# SyncBoard1.net
KiCad netlist of a schematic drawn in Altium Designer
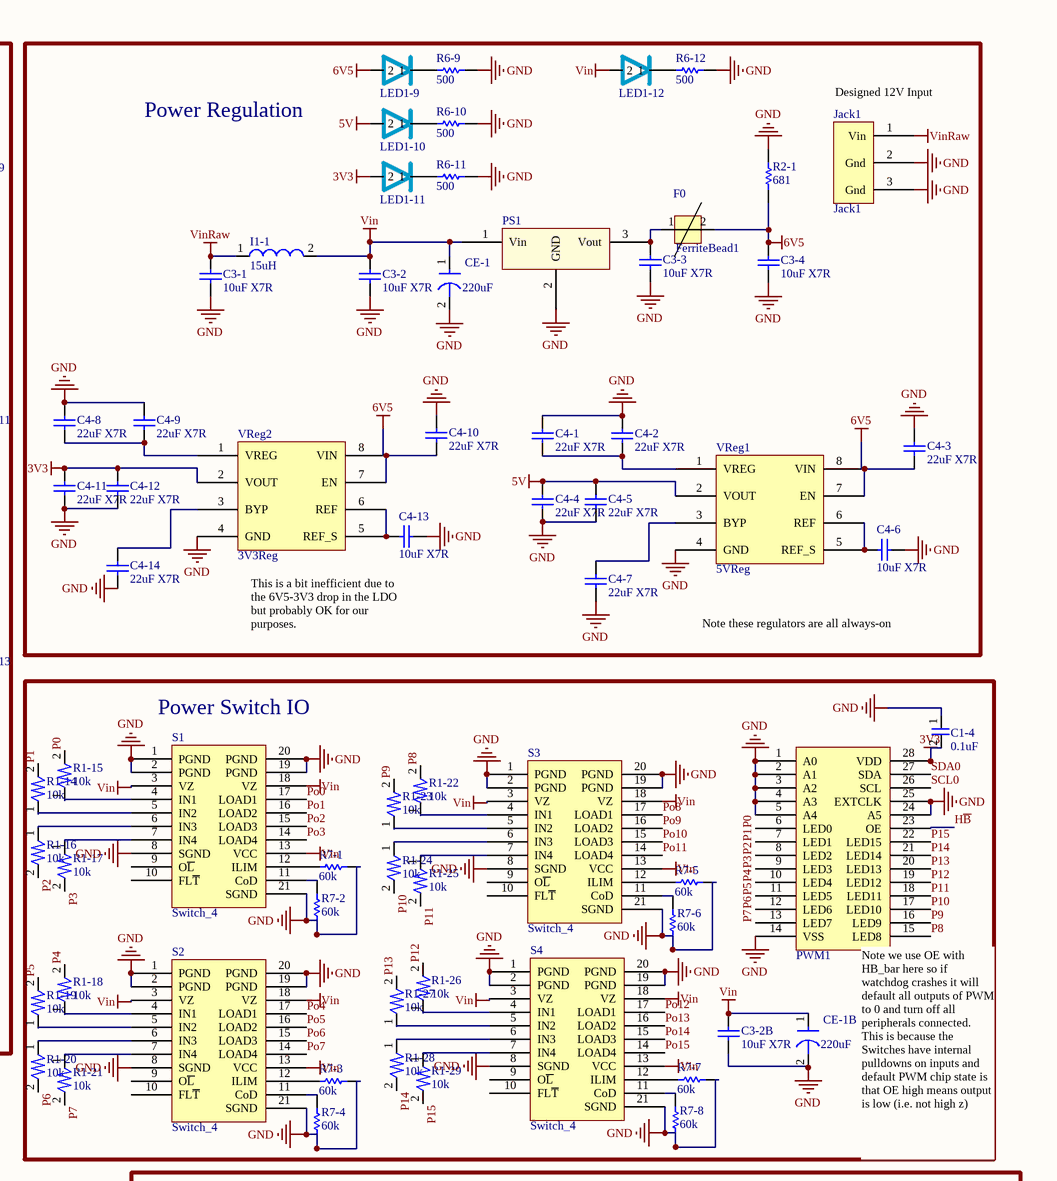
[diagram p0: SyncBoard1.SchDoc, top right]
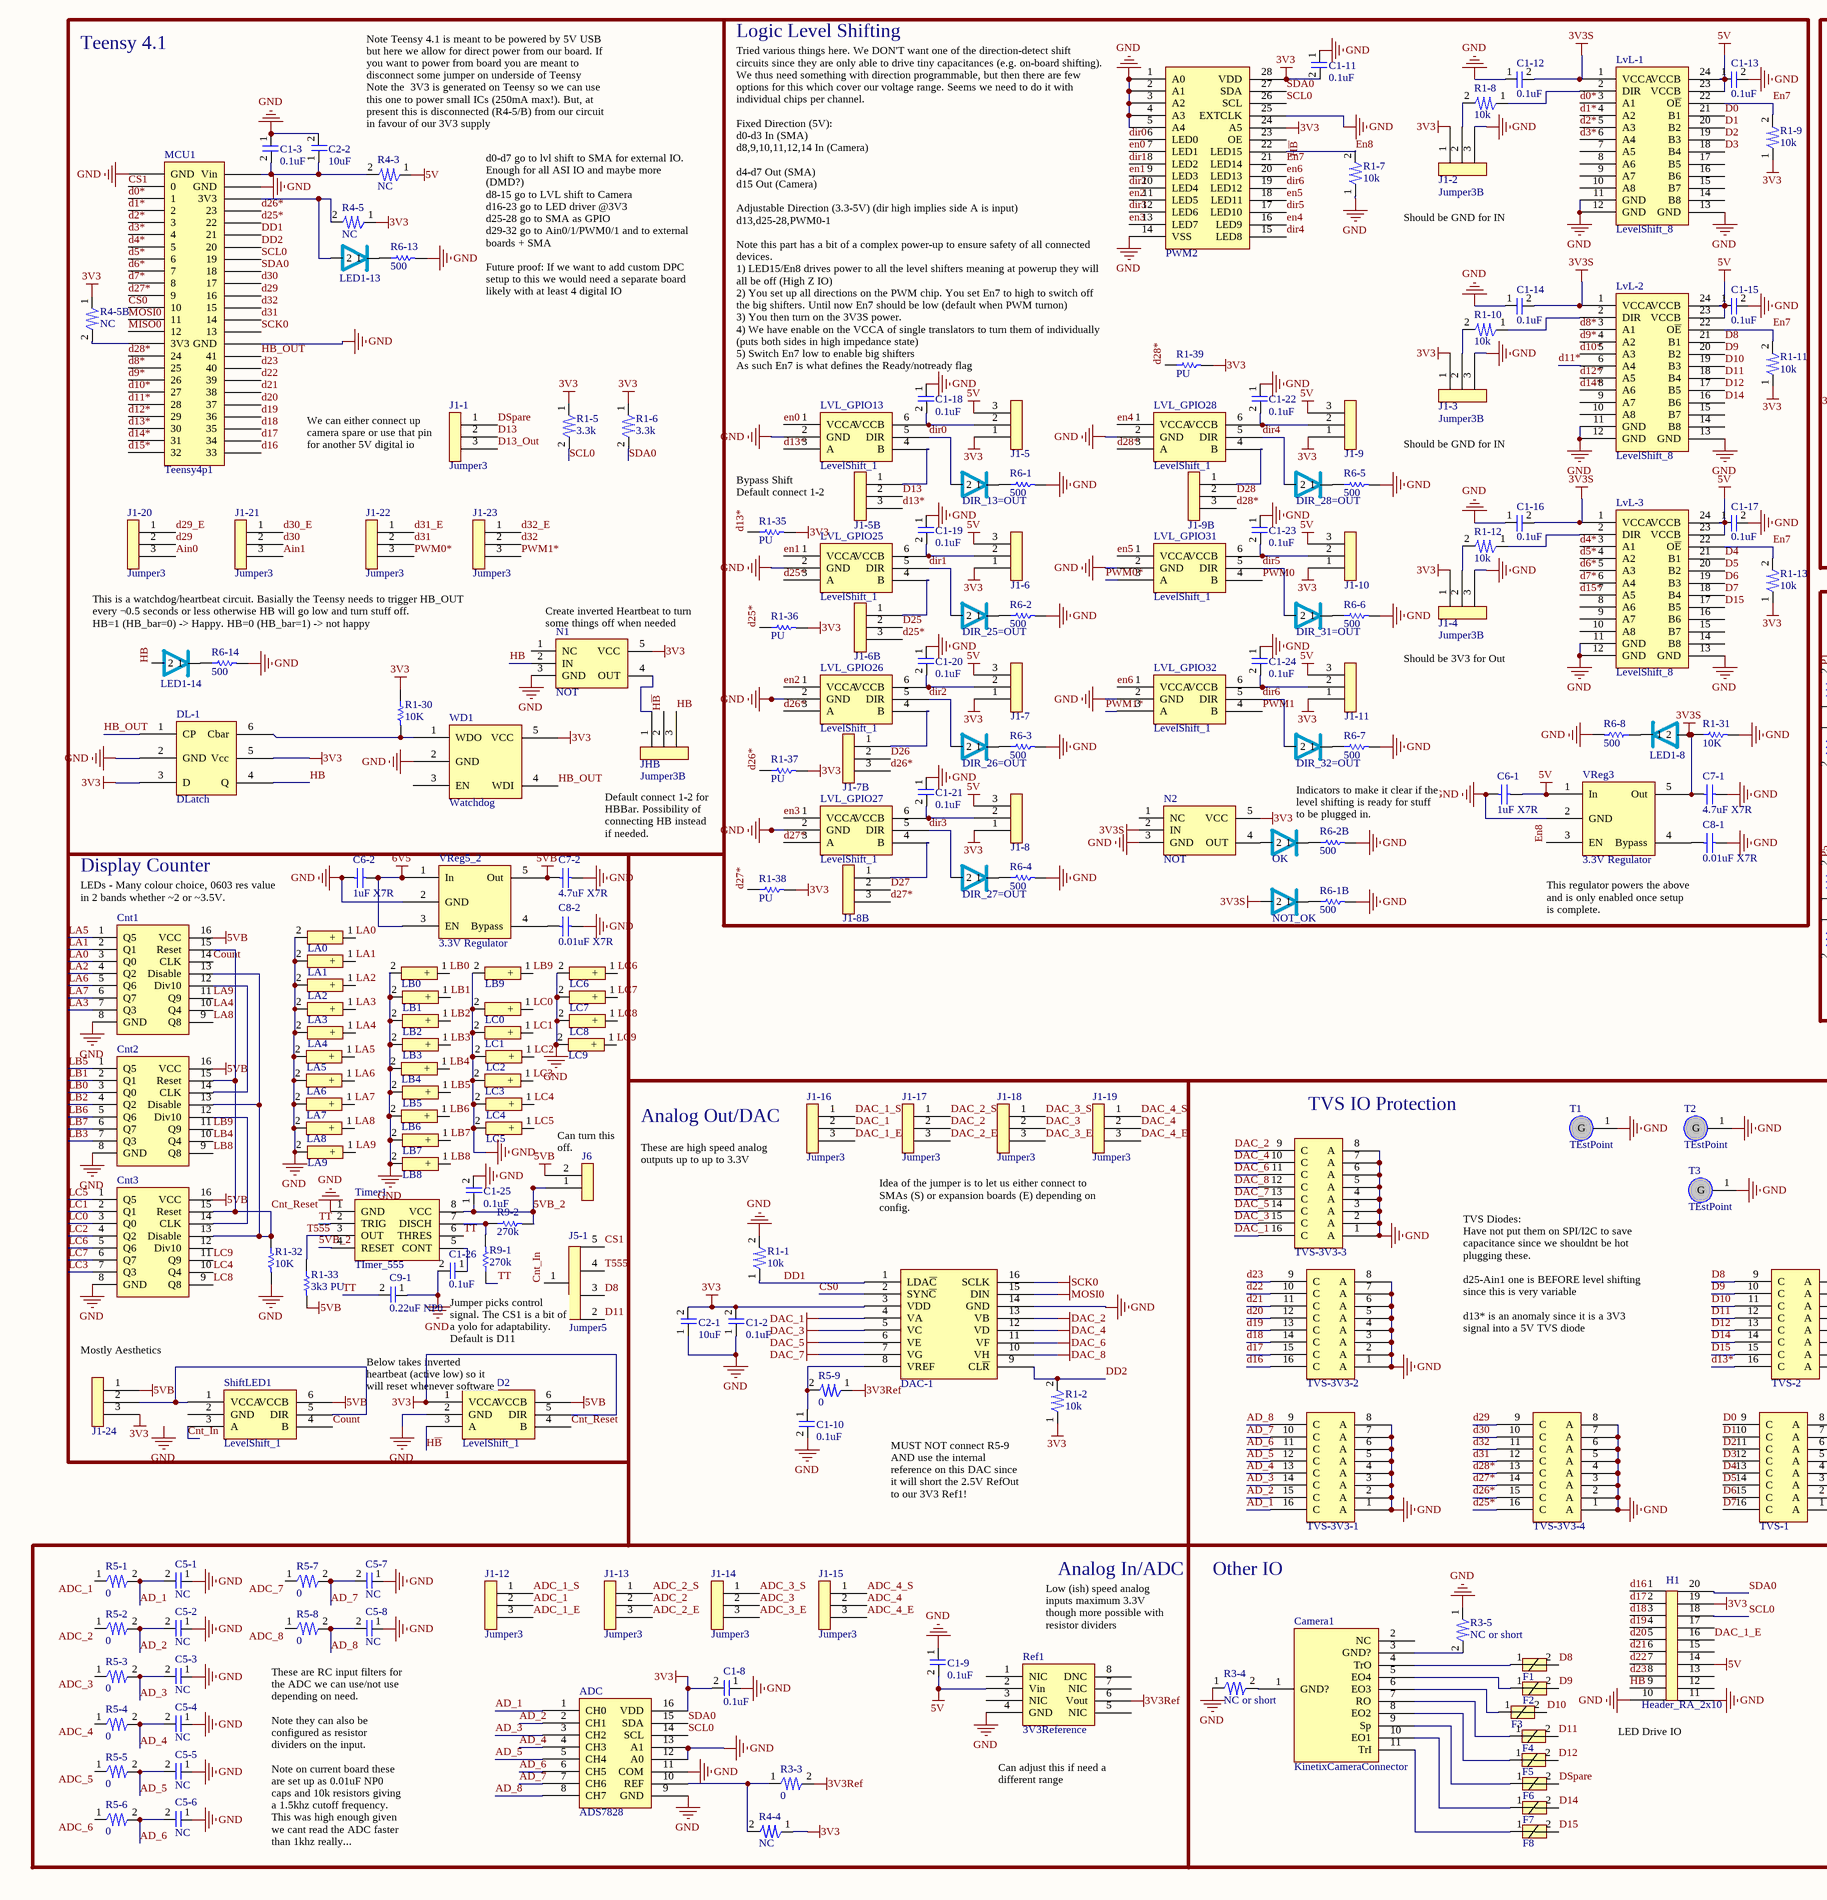
[diagram p1: SyncBoard1.SchDoc, bottom left]
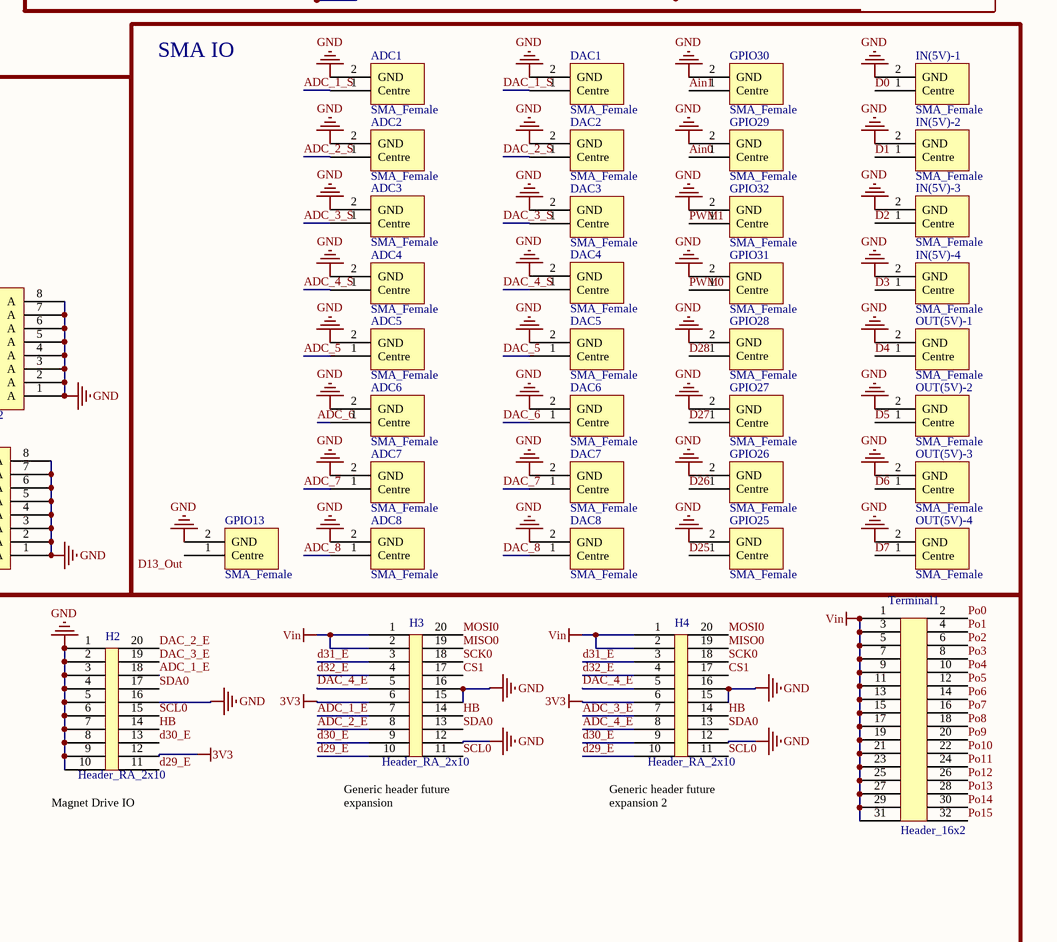
[diagram p2: SyncBoard1.SchDoc, bottom right]

(export (version "E")
  (design (tool "Eeschema 10.0.6"))
  (components
    (comp (ref "ADC")
      (value "ADS7828")
      (footprint "16-TSSOP")
      (libsource (lib "PCBSchematics") (part "ADS7828"))
    )
    (comp (ref "ADC1")
      (value "SMA_Female")
      (footprint "SMA_Ferrite")
      (libsource (lib "PCBSchematics") (part "SMA_Female"))
    )
    (comp (ref "ADC2")
      (value "SMA_Female")
      (footprint "SMA_Ferrite")
      (libsource (lib "PCBSchematics") (part "SMA_Female"))
    )
    (comp (ref "ADC3")
      (value "SMA_Female")
      (footprint "SMA_Ferrite")
      (libsource (lib "PCBSchematics") (part "SMA_Female"))
    )
    (comp (ref "ADC4")
      (value "SMA_Female")
      (footprint "SMA_Ferrite")
      (libsource (lib "PCBSchematics") (part "SMA_Female"))
    )
    (comp (ref "ADC5")
      (value "SMA_Female")
      (footprint "SMA_Ferrite")
      (libsource (lib "PCBSchematics") (part "SMA_Female"))
    )
    (comp (ref "ADC6")
      (value "SMA_Female")
      (footprint "SMA_Ferrite")
      (libsource (lib "PCBSchematics") (part "SMA_Female"))
    )
    (comp (ref "ADC7")
      (value "SMA_Female")
      (footprint "SMA_Ferrite")
      (libsource (lib "PCBSchematics") (part "SMA_Female"))
    )
    (comp (ref "ADC8")
      (value "SMA_Female")
      (footprint "SMA_Ferrite")
      (libsource (lib "PCBSchematics") (part "SMA_Female"))
    )
    (comp (ref "C1-2")
      (value "0.1uF")
      (footprint "0805")
      (libsource (lib "PCBSchematics") (part "Capacitor1"))
    )
    (comp (ref "C1-3")
      (value "0.1uF")
      (footprint "0805")
      (libsource (lib "PCBSchematics") (part "Capacitor1"))
    )
    (comp (ref "C1-4")
      (value "0.1uF")
      (footprint "0805")
      (libsource (lib "PCBSchematics") (part "Capacitor1"))
    )
    (comp (ref "C1-8")
      (value "0.1uF")
      (footprint "0805")
      (libsource (lib "PCBSchematics") (part "Capacitor1"))
    )
    (comp (ref "C1-9")
      (value "0.1uF")
      (footprint "0805")
      (libsource (lib "PCBSchematics") (part "Capacitor1"))
    )
    (comp (ref "C1-10")
      (value "0.1uF")
      (footprint "0805")
      (libsource (lib "PCBSchematics") (part "Capacitor1"))
    )
    (comp (ref "C1-11")
      (value "0.1uF")
      (footprint "0805")
      (libsource (lib "PCBSchematics") (part "Capacitor1"))
    )
    (comp (ref "C1-12")
      (value "0.1uF")
      (footprint "0805")
      (libsource (lib "PCBSchematics") (part "Capacitor1"))
    )
    (comp (ref "C1-13")
      (value "0.1uF")
      (footprint "0805")
      (libsource (lib "PCBSchematics") (part "Capacitor1"))
    )
    (comp (ref "C1-14")
      (value "0.1uF")
      (footprint "0805")
      (libsource (lib "PCBSchematics") (part "Capacitor1"))
    )
    (comp (ref "C1-15")
      (value "0.1uF")
      (footprint "0805")
      (libsource (lib "PCBSchematics") (part "Capacitor1"))
    )
    (comp (ref "C1-16")
      (value "0.1uF")
      (footprint "0805")
      (libsource (lib "PCBSchematics") (part "Capacitor1"))
    )
    (comp (ref "C1-17")
      (value "0.1uF")
      (footprint "0805")
      (libsource (lib "PCBSchematics") (part "Capacitor1"))
    )
    (comp (ref "C1-18")
      (value "0.1uF")
      (footprint "0805")
      (libsource (lib "PCBSchematics") (part "Capacitor1"))
    )
    (comp (ref "C1-19")
      (value "0.1uF")
      (footprint "0805")
      (libsource (lib "PCBSchematics") (part "Capacitor1"))
    )
    (comp (ref "C1-20")
      (value "0.1uF")
      (footprint "0805")
      (libsource (lib "PCBSchematics") (part "Capacitor1"))
    )
    (comp (ref "C1-21")
      (value "0.1uF")
      (footprint "0805")
      (libsource (lib "PCBSchematics") (part "Capacitor1"))
    )
    (comp (ref "C1-22")
      (value "0.1uF")
      (footprint "0805")
      (libsource (lib "PCBSchematics") (part "Capacitor1"))
    )
    (comp (ref "C1-23")
      (value "0.1uF")
      (footprint "0805")
      (libsource (lib "PCBSchematics") (part "Capacitor1"))
    )
    (comp (ref "C1-24")
      (value "0.1uF")
      (footprint "0805")
      (libsource (lib "PCBSchematics") (part "Capacitor1"))
    )
    (comp (ref "C1-25")
      (value "0.1uF")
      (footprint "0805")
      (libsource (lib "PCBSchematics") (part "Capacitor1"))
    )
    (comp (ref "C1-26")
      (value "0.1uF")
      (footprint "0805")
      (libsource (lib "PCBSchematics") (part "Capacitor1"))
    )
    (comp (ref "C2-1")
      (value "10uF")
      (footprint "1206")
      (libsource (lib "PCBSchematics") (part "Capacitor1205"))
    )
    (comp (ref "C2-2")
      (value "10uF")
      (footprint "1206")
      (libsource (lib "PCBSchematics") (part "Capacitor1205"))
    )
    (comp (ref "C3-1")
      (value "10uF X7R")
      (footprint "1206")
      (description "Capacitor")
      (libsource (lib "Schlib1") (part "Cap 0805"))
    )
    (comp (ref "C3-2")
      (value "10uF X7R")
      (footprint "1206")
      (description "Capacitor")
      (libsource (lib "Schlib1") (part "Cap 0805"))
    )
    (comp (ref "C3-2B")
      (value "10uF X7R")
      (footprint "1206")
      (description "Capacitor")
      (libsource (lib "Schlib1") (part "Cap 0805"))
    )
    (comp (ref "C3-3")
      (value "10uF X7R")
      (footprint "1206")
      (description "Capacitor")
      (libsource (lib "Schlib1") (part "Cap 0805"))
    )
    (comp (ref "C3-4")
      (value "10uF X7R")
      (footprint "1206")
      (description "Capacitor")
      (libsource (lib "Schlib1") (part "Cap 0805"))
    )
    (comp (ref "C4-1")
      (value "22uF X7R")
      (footprint "1206")
      (description "Capacitor")
      (libsource (lib "Schlib1") (part "Cap 0805"))
    )
    (comp (ref "C4-2")
      (value "22uF X7R")
      (footprint "1206")
      (description "Capacitor")
      (libsource (lib "Schlib1") (part "Cap 0805"))
    )
    (comp (ref "C4-3")
      (value "22uF X7R")
      (footprint "1206")
      (description "Capacitor")
      (libsource (lib "Schlib1") (part "Cap 0805"))
    )
    (comp (ref "C4-4")
      (value "22uF X7R")
      (footprint "1206")
      (description "Capacitor")
      (libsource (lib "Schlib1") (part "Cap 0805"))
    )
    (comp (ref "C4-5")
      (value "22uF X7R")
      (footprint "1206")
      (description "Capacitor")
      (libsource (lib "Schlib1") (part "Cap 0805"))
    )
    (comp (ref "C4-6")
      (value "10uF X7R")
      (footprint "1206")
      (description "Capacitor")
      (libsource (lib "Schlib1") (part "Cap 0805"))
    )
    (comp (ref "C4-7")
      (value "22uF X7R")
      (footprint "1206")
      (description "Capacitor")
      (libsource (lib "Schlib1") (part "Cap 0805"))
    )
    (comp (ref "C4-8")
      (value "22uF X7R")
      (footprint "1206")
      (description "Capacitor")
      (libsource (lib "Schlib1") (part "Cap 0805"))
    )
    (comp (ref "C4-9")
      (value "22uF X7R")
      (footprint "1206")
      (description "Capacitor")
      (libsource (lib "Schlib1") (part "Cap 0805"))
    )
    (comp (ref "C4-10")
      (value "22uF X7R")
      (footprint "1206")
      (description "Capacitor")
      (libsource (lib "Schlib1") (part "Cap 0805"))
    )
    (comp (ref "C4-11")
      (value "22uF X7R")
      (footprint "1206")
      (description "Capacitor")
      (libsource (lib "Schlib1") (part "Cap 0805"))
    )
    (comp (ref "C4-12")
      (value "22uF X7R")
      (footprint "1206")
      (description "Capacitor")
      (libsource (lib "Schlib1") (part "Cap 0805"))
    )
    (comp (ref "C4-13")
      (value "10uF X7R")
      (footprint "1206")
      (description "Capacitor")
      (libsource (lib "Schlib1") (part "Cap 0805"))
    )
    (comp (ref "C4-14")
      (value "22uF X7R")
      (footprint "1206")
      (description "Capacitor")
      (libsource (lib "Schlib1") (part "Cap 0805"))
    )
    (comp (ref "C5-1") (value "NC") (footprint "0805") (libsource (lib "PCBSchematics") (part "Capacitor1")))
    (comp (ref "C5-2") (value "NC") (footprint "0805") (libsource (lib "PCBSchematics") (part "Capacitor1")))
    (comp (ref "C5-3") (value "NC") (footprint "0805") (libsource (lib "PCBSchematics") (part "Capacitor1")))
    (comp (ref "C5-4") (value "NC") (footprint "0805") (libsource (lib "PCBSchematics") (part "Capacitor1")))
    (comp (ref "C5-5") (value "NC") (footprint "0805") (libsource (lib "PCBSchematics") (part "Capacitor1")))
    (comp (ref "C5-6") (value "NC") (footprint "0805") (libsource (lib "PCBSchematics") (part "Capacitor1")))
    (comp (ref "C5-7") (value "NC") (footprint "0805") (libsource (lib "PCBSchematics") (part "Capacitor1")))
    (comp (ref "C5-8") (value "NC") (footprint "0805") (libsource (lib "PCBSchematics") (part "Capacitor1")))
    (comp (ref "C6-1")
      (value "1uF X7R")
      (footprint "0805")
      (description "Capacitor")
      (libsource (lib "Schlib1") (part "Cap"))
    )
    (comp (ref "C6-2")
      (value "1uF X7R")
      (footprint "0805")
      (description "Capacitor")
      (libsource (lib "Schlib1") (part "Cap"))
    )
    (comp (ref "C7-1")
      (value "4.7uF X7R")
      (footprint "0805")
      (description "Capacitor")
      (libsource (lib "Schlib1") (part "Cap"))
    )
    (comp (ref "C7-2")
      (value "4.7uF X7R")
      (footprint "0805")
      (description "Capacitor")
      (libsource (lib "Schlib1") (part "Cap"))
    )
    (comp (ref "C8-1")
      (value "0.01uF X7R")
      (footprint "0603")
      (description "Capacitor")
      (libsource (lib "Schlib1") (part "Cap"))
    )
    (comp (ref "C8-2")
      (value "0.01uF X7R")
      (footprint "0603")
      (description "Capacitor")
      (libsource (lib "Schlib1") (part "Cap"))
    )
    (comp (ref "C9-1")
      (value "0.22uF NP0")
      (footprint "1206")
      (libsource (lib "PCBSchematics") (part "Capacitor1"))
    )
    (comp (ref "Camera1")
      (value "KinetixCameraConnector")
      (footprint "Connector_HR212")
      (libsource (lib "PCBSchematics") (part "KinetixCameraConnector"))
    )
    (comp (ref "CE-1")
      (value "220uF")
      (footprint "ElectrolyticCapacitor")
      (description "ElectrolyticCap")
      (libsource (lib "Schlib1") (part "CapElectrolytic2"))
    )
    (comp (ref "CE-1B")
      (value "220uF")
      (footprint "ElectrolyticCapacitor")
      (description "ElectrolyticCap")
      (libsource (lib "Schlib1") (part "CapElectrolytic2"))
    )
    (comp (ref "Cnt1")
      (value "Counter_$017")
      (footprint "16-TSSOP")
      (libsource (lib "PCBSchematics") (part "Counter_$017"))
    )
    (comp (ref "Cnt2")
      (value "Counter_$017")
      (footprint "16-TSSOP")
      (libsource (lib "PCBSchematics") (part "Counter_$017"))
    )
    (comp (ref "Cnt3")
      (value "Counter_$017")
      (footprint "16-TSSOP")
      (libsource (lib "PCBSchematics") (part "Counter_$017"))
    )
    (comp (ref "DAC-1")
      (value "AD5668-2")
      (footprint "16-TSSOP")
      (libsource (lib "PCBSchematics") (part "AD5668-2"))
    )
    (comp (ref "DAC1")
      (value "SMA_Female")
      (footprint "SMA_Ferrite")
      (libsource (lib "PCBSchematics") (part "SMA_Female"))
    )
    (comp (ref "DAC2")
      (value "SMA_Female")
      (footprint "SMA_Ferrite")
      (libsource (lib "PCBSchematics") (part "SMA_Female"))
    )
    (comp (ref "DAC3")
      (value "SMA_Female")
      (footprint "SMA_Ferrite")
      (libsource (lib "PCBSchematics") (part "SMA_Female"))
    )
    (comp (ref "DAC4")
      (value "SMA_Female")
      (footprint "SMA_Ferrite")
      (libsource (lib "PCBSchematics") (part "SMA_Female"))
    )
    (comp (ref "DAC5")
      (value "SMA_Female")
      (footprint "SMA_Ferrite")
      (libsource (lib "PCBSchematics") (part "SMA_Female"))
    )
    (comp (ref "DAC6")
      (value "SMA_Female")
      (footprint "SMA_Ferrite")
      (libsource (lib "PCBSchematics") (part "SMA_Female"))
    )
    (comp (ref "DAC7")
      (value "SMA_Female")
      (footprint "SMA_Ferrite")
      (libsource (lib "PCBSchematics") (part "SMA_Female"))
    )
    (comp (ref "DAC8")
      (value "SMA_Female")
      (footprint "SMA_Ferrite")
      (libsource (lib "PCBSchematics") (part "SMA_Female"))
    )
    (comp (ref "DIR_13=OUT")
      (value "LEDindicator")
      (footprint "LEDindicator")
      (libsource (lib "Schlib1") (part "LEDindicator"))
    )
    (comp (ref "DIR_25=OUT")
      (value "LEDindicator")
      (footprint "LEDindicator")
      (libsource (lib "Schlib1") (part "LEDindicator"))
    )
    (comp (ref "DIR_26=OUT")
      (value "LEDindicator")
      (footprint "LEDindicator")
      (libsource (lib "Schlib1") (part "LEDindicator"))
    )
    (comp (ref "DIR_27=OUT")
      (value "LEDindicator")
      (footprint "LEDindicator")
      (libsource (lib "Schlib1") (part "LEDindicator"))
    )
    (comp (ref "DIR_28=OUT")
      (value "LEDindicator")
      (footprint "LEDindicator")
      (libsource (lib "Schlib1") (part "LEDindicator"))
    )
    (comp (ref "DIR_31=OUT")
      (value "LEDindicator")
      (footprint "LEDindicator")
      (libsource (lib "Schlib1") (part "LEDindicator"))
    )
    (comp (ref "DIR_32=OUT")
      (value "LEDindicator")
      (footprint "LEDindicator")
      (libsource (lib "Schlib1") (part "LEDindicator"))
    )
    (comp (ref "DL-1")
      (value "DLatch")
      (footprint "6-TSSOP / SC-70-6")
      (description "D-Latch")
      (libsource (lib "Schlib1") (part "DLatch"))
    )
    (comp (ref "F0")
      (value "FerriteBead1")
      (footprint "FerriteBead1")
      (libsource (lib "PCBSchematics") (part "FerriteBead1"))
    )
    (comp (ref "F1")
      (value "FerriteBead2")
      (footprint "0603")
      (libsource (lib "PCBSchematics") (part "FerriteBead2"))
    )
    (comp (ref "F2")
      (value "FerriteBead2")
      (footprint "0603")
      (libsource (lib "PCBSchematics") (part "FerriteBead2"))
    )
    (comp (ref "F3")
      (value "FerriteBead2")
      (footprint "0603")
      (libsource (lib "PCBSchematics") (part "FerriteBead2"))
    )
    (comp (ref "F4")
      (value "FerriteBead2")
      (footprint "0603")
      (libsource (lib "PCBSchematics") (part "FerriteBead2"))
    )
    (comp (ref "F5")
      (value "FerriteBead2")
      (footprint "0603")
      (libsource (lib "PCBSchematics") (part "FerriteBead2"))
    )
    (comp (ref "F6")
      (value "FerriteBead2")
      (footprint "0603")
      (libsource (lib "PCBSchematics") (part "FerriteBead2"))
    )
    (comp (ref "F7")
      (value "FerriteBead2")
      (footprint "0603")
      (libsource (lib "PCBSchematics") (part "FerriteBead2"))
    )
    (comp (ref "F8")
      (value "FerriteBead2")
      (footprint "0603")
      (libsource (lib "PCBSchematics") (part "FerriteBead2"))
    )
    (comp (ref "GPIO13")
      (value "SMA_Female")
      (footprint "SMA_Ferrite")
      (libsource (lib "PCBSchematics") (part "SMA_Female"))
    )
    (comp (ref "GPIO25")
      (value "SMA_Female")
      (footprint "SMA_Ferrite")
      (libsource (lib "PCBSchematics") (part "SMA_Female"))
    )
    (comp (ref "GPIO26")
      (value "SMA_Female")
      (footprint "SMA_Ferrite")
      (libsource (lib "PCBSchematics") (part "SMA_Female"))
    )
    (comp (ref "GPIO27")
      (value "SMA_Female")
      (footprint "SMA_Ferrite")
      (libsource (lib "PCBSchematics") (part "SMA_Female"))
    )
    (comp (ref "GPIO28")
      (value "SMA_Female")
      (footprint "SMA_Ferrite")
      (libsource (lib "PCBSchematics") (part "SMA_Female"))
    )
    (comp (ref "GPIO29")
      (value "SMA_Female")
      (footprint "SMA_Ferrite")
      (libsource (lib "PCBSchematics") (part "SMA_Female"))
    )
    (comp (ref "GPIO30")
      (value "SMA_Female")
      (footprint "SMA_Ferrite")
      (libsource (lib "PCBSchematics") (part "SMA_Female"))
    )
    (comp (ref "GPIO31")
      (value "SMA_Female")
      (footprint "SMA_Ferrite")
      (libsource (lib "PCBSchematics") (part "SMA_Female"))
    )
    (comp (ref "GPIO32")
      (value "SMA_Female")
      (footprint "SMA_Ferrite")
      (libsource (lib "PCBSchematics") (part "SMA_Female"))
    )
    (comp (ref "H1")
      (value "Header_RA_2x10")
      (footprint "HeaderRA 2x10")
      (libsource (lib "PCBSchematics") (part "Header_RA_2x10"))
    )
    (comp (ref "H2")
      (value "Header_RA_2x10")
      (footprint "HeaderRA 2x10")
      (libsource (lib "PCBSchematics") (part "Header_RA_2x10"))
    )
    (comp (ref "H3")
      (value "Header_RA_2x10")
      (footprint "HeaderRA 2x10")
      (libsource (lib "PCBSchematics") (part "Header_RA_2x10"))
    )
    (comp (ref "H4")
      (value "Header_RA_2x10")
      (footprint "HeaderRA 2x10")
      (libsource (lib "PCBSchematics") (part "Header_RA_2x10"))
    )
    (comp (ref "I1-1")
      (value "15uH")
      (footprint "Inductor1")
      (description "Inductor")
      (libsource (lib "Schlib1") (part "Inductor3"))
    )
    (comp (ref "IN(5V)-1")
      (value "SMA_Female")
      (footprint "SMA_Ferrite")
      (libsource (lib "PCBSchematics") (part "SMA_Female"))
    )
    (comp (ref "IN(5V)-2")
      (value "SMA_Female")
      (footprint "SMA_Ferrite")
      (libsource (lib "PCBSchematics") (part "SMA_Female"))
    )
    (comp (ref "IN(5V)-3")
      (value "SMA_Female")
      (footprint "SMA_Ferrite")
      (libsource (lib "PCBSchematics") (part "SMA_Female"))
    )
    (comp (ref "IN(5V)-4")
      (value "SMA_Female")
      (footprint "SMA_Ferrite")
      (libsource (lib "PCBSchematics") (part "SMA_Female"))
    )
    (comp (ref "J1-1")
      (value "Jumper3")
      (footprint "Jumper3B")
      (libsource (lib "PCBSchematics") (part "Jumper3"))
    )
    (comp (ref "J1-2") (value "Jumper3B") (footprint "Jumper3B") (libsource (lib "") (part "Jumper3B_1")))
    (comp (ref "J1-3") (value "Jumper3B") (footprint "Jumper3B") (libsource (lib "") (part "Jumper3B_1")))
    (comp (ref "J1-4") (value "Jumper3B") (footprint "Jumper3B") (libsource (lib "") (part "Jumper3B_1")))
    (comp (ref "J1-5") (value "Jumper3B") (footprint "Jumper3B") (libsource (lib "") (part "Jumper3B_2")))
    (comp (ref "J1-5B")
      (value "Jumper3B")
      (footprint "Jumper3B")
      (libsource (lib "PCBSchematics") (part "Jumper3B"))
    )
    (comp (ref "J1-6") (value "Jumper3B") (footprint "Jumper3B") (libsource (lib "") (part "Jumper3B_2")))
    (comp (ref "J1-6B")
      (value "Jumper3B")
      (footprint "Jumper3B")
      (libsource (lib "PCBSchematics") (part "Jumper3B"))
    )
    (comp (ref "J1-7") (value "Jumper3B") (footprint "Jumper3B") (libsource (lib "") (part "Jumper3B_2")))
    (comp (ref "J1-7B")
      (value "Jumper3B")
      (footprint "Jumper3B")
      (libsource (lib "PCBSchematics") (part "Jumper3B"))
    )
    (comp (ref "J1-8") (value "Jumper3B") (footprint "Jumper3B") (libsource (lib "") (part "Jumper3B_2")))
    (comp (ref "J1-8B")
      (value "Jumper3B")
      (footprint "Jumper3B")
      (libsource (lib "PCBSchematics") (part "Jumper3B"))
    )
    (comp (ref "J1-9") (value "Jumper3B") (footprint "Jumper3B") (libsource (lib "") (part "Jumper3B_2")))
    (comp (ref "J1-9B")
      (value "Jumper3B")
      (footprint "Jumper3B")
      (libsource (lib "PCBSchematics") (part "Jumper3B"))
    )
    (comp (ref "J1-10") (value "Jumper3B") (footprint "Jumper3B") (libsource (lib "") (part "Jumper3B_2")))
    (comp (ref "J1-11") (value "Jumper3B") (footprint "Jumper3B") (libsource (lib "") (part "Jumper3B_2")))
    (comp (ref "J1-12")
      (value "Jumper3")
      (footprint "Jumper")
      (libsource (lib "PCBSchematics") (part "Jumper3"))
    )
    (comp (ref "J1-13")
      (value "Jumper3")
      (footprint "Jumper")
      (libsource (lib "PCBSchematics") (part "Jumper3"))
    )
    (comp (ref "J1-14")
      (value "Jumper3")
      (footprint "Jumper")
      (libsource (lib "PCBSchematics") (part "Jumper3"))
    )
    (comp (ref "J1-15")
      (value "Jumper3")
      (footprint "Jumper")
      (libsource (lib "PCBSchematics") (part "Jumper3"))
    )
    (comp (ref "J1-16")
      (value "Jumper3")
      (footprint "Jumper")
      (libsource (lib "PCBSchematics") (part "Jumper3"))
    )
    (comp (ref "J1-17")
      (value "Jumper3")
      (footprint "Jumper")
      (libsource (lib "PCBSchematics") (part "Jumper3"))
    )
    (comp (ref "J1-18")
      (value "Jumper3")
      (footprint "Jumper")
      (libsource (lib "PCBSchematics") (part "Jumper3"))
    )
    (comp (ref "J1-19")
      (value "Jumper3")
      (footprint "Jumper")
      (libsource (lib "PCBSchematics") (part "Jumper3"))
    )
    (comp (ref "J1-20")
      (value "Jumper3")
      (footprint "Jumper")
      (libsource (lib "PCBSchematics") (part "Jumper3"))
    )
    (comp (ref "J1-21")
      (value "Jumper3")
      (footprint "Jumper")
      (libsource (lib "PCBSchematics") (part "Jumper3"))
    )
    (comp (ref "J1-22")
      (value "Jumper3")
      (footprint "Jumper")
      (libsource (lib "PCBSchematics") (part "Jumper3"))
    )
    (comp (ref "J1-23")
      (value "Jumper3")
      (footprint "Jumper")
      (libsource (lib "PCBSchematics") (part "Jumper3"))
    )
    (comp (ref "J1-24")
      (value "Jumper3B")
      (footprint "Jumper3B")
      (libsource (lib "PCBSchematics") (part "Jumper3B"))
    )
    (comp (ref "J5-1")
      (value "Jumper5")
      (footprint "Jumper5")
      (libsource (lib "PCBSchematics") (part "Jumper5"))
    )
    (comp (ref "J6")
      (value "Jumper2_Pins")
      (footprint "Jumper2_Pins")
      (libsource (lib "PCBSchematics") (part "Jumper2_Pins"))
    )
    (comp (ref "Jack1")
      (value "Jack1")
      (footprint "PowerJack")
      (libsource (lib "Schlib1") (part "PowerJack3"))
    )
    (comp (ref "JHB") (value "Jumper3B") (footprint "Jumper3B") (libsource (lib "") (part "Jumper3B_1")))
    (comp (ref "LA0")
      (value "LEDSINGLESIDE")
      (footprint "LedSingleSide")
      (libsource (lib "PCBSchematics") (part "LEDSINGLESIDE"))
    )
    (comp (ref "LA1")
      (value "LEDSINGLESIDE")
      (footprint "LedSingleSide")
      (libsource (lib "PCBSchematics") (part "LEDSINGLESIDE"))
    )
    (comp (ref "LA2")
      (value "LEDSINGLESIDE")
      (footprint "LedSingleSide")
      (libsource (lib "PCBSchematics") (part "LEDSINGLESIDE"))
    )
    (comp (ref "LA3")
      (value "LEDSINGLESIDE")
      (footprint "LedSingleSide")
      (libsource (lib "PCBSchematics") (part "LEDSINGLESIDE"))
    )
    (comp (ref "LA4")
      (value "LEDSINGLESIDE")
      (footprint "LedSingleSide")
      (libsource (lib "PCBSchematics") (part "LEDSINGLESIDE"))
    )
    (comp (ref "LA5")
      (value "LEDSINGLESIDE")
      (footprint "LedSingleSide")
      (libsource (lib "PCBSchematics") (part "LEDSINGLESIDE"))
    )
    (comp (ref "LA6")
      (value "LEDSINGLESIDE")
      (footprint "LedSingleSide")
      (libsource (lib "PCBSchematics") (part "LEDSINGLESIDE"))
    )
    (comp (ref "LA7")
      (value "LEDSINGLESIDE")
      (footprint "LedSingleSide")
      (libsource (lib "PCBSchematics") (part "LEDSINGLESIDE"))
    )
    (comp (ref "LA8")
      (value "LEDSINGLESIDE")
      (footprint "LedSingleSide")
      (libsource (lib "PCBSchematics") (part "LEDSINGLESIDE"))
    )
    (comp (ref "LA9")
      (value "LEDSINGLESIDE")
      (footprint "LedSingleSide")
      (libsource (lib "PCBSchematics") (part "LEDSINGLESIDE"))
    )
    (comp (ref "LB0")
      (value "LEDSINGLESIDE")
      (footprint "LedSingleSide")
      (libsource (lib "PCBSchematics") (part "LEDSINGLESIDE"))
    )
    (comp (ref "LB1")
      (value "LEDSINGLESIDE")
      (footprint "LedSingleSide")
      (libsource (lib "PCBSchematics") (part "LEDSINGLESIDE"))
    )
    (comp (ref "LB2")
      (value "LEDSINGLESIDE")
      (footprint "LedSingleSide")
      (libsource (lib "PCBSchematics") (part "LEDSINGLESIDE"))
    )
    (comp (ref "LB3")
      (value "LEDSINGLESIDE")
      (footprint "LedSingleSide")
      (libsource (lib "PCBSchematics") (part "LEDSINGLESIDE"))
    )
    (comp (ref "LB4")
      (value "LEDSINGLESIDE")
      (footprint "LedSingleSide")
      (libsource (lib "PCBSchematics") (part "LEDSINGLESIDE"))
    )
    (comp (ref "LB5")
      (value "LEDSINGLESIDE")
      (footprint "LedSingleSide")
      (libsource (lib "PCBSchematics") (part "LEDSINGLESIDE"))
    )
    (comp (ref "LB6")
      (value "LEDSINGLESIDE")
      (footprint "LedSingleSide")
      (libsource (lib "PCBSchematics") (part "LEDSINGLESIDE"))
    )
    (comp (ref "LB7")
      (value "LEDSINGLESIDE")
      (footprint "LedSingleSide")
      (libsource (lib "PCBSchematics") (part "LEDSINGLESIDE"))
    )
    (comp (ref "LB8")
      (value "LEDSINGLESIDE")
      (footprint "LedSingleSide")
      (libsource (lib "PCBSchematics") (part "LEDSINGLESIDE"))
    )
    (comp (ref "LB9")
      (value "LEDSINGLESIDE")
      (footprint "LedSingleSide")
      (libsource (lib "PCBSchematics") (part "LEDSINGLESIDE"))
    )
    (comp (ref "LC0")
      (value "LEDSINGLESIDE")
      (footprint "LedSingleSide")
      (libsource (lib "PCBSchematics") (part "LEDSINGLESIDE"))
    )
    (comp (ref "LC1")
      (value "LEDSINGLESIDE")
      (footprint "LedSingleSide")
      (libsource (lib "PCBSchematics") (part "LEDSINGLESIDE"))
    )
    (comp (ref "LC2")
      (value "LEDSINGLESIDE")
      (footprint "LedSingleSide")
      (libsource (lib "PCBSchematics") (part "LEDSINGLESIDE"))
    )
    (comp (ref "LC3")
      (value "LEDSINGLESIDE")
      (footprint "LedSingleSide")
      (libsource (lib "PCBSchematics") (part "LEDSINGLESIDE"))
    )
    (comp (ref "LC4")
      (value "LEDSINGLESIDE")
      (footprint "LedSingleSide")
      (libsource (lib "PCBSchematics") (part "LEDSINGLESIDE"))
    )
    (comp (ref "LC5")
      (value "LEDSINGLESIDE")
      (footprint "LedSingleSide")
      (libsource (lib "PCBSchematics") (part "LEDSINGLESIDE"))
    )
    (comp (ref "LC6")
      (value "LEDSINGLESIDE")
      (footprint "LedSingleSide")
      (libsource (lib "PCBSchematics") (part "LEDSINGLESIDE"))
    )
    (comp (ref "LC7")
      (value "LEDSINGLESIDE")
      (footprint "LedSingleSide")
      (libsource (lib "PCBSchematics") (part "LEDSINGLESIDE"))
    )
    (comp (ref "LC8")
      (value "LEDSINGLESIDE")
      (footprint "LedSingleSide")
      (libsource (lib "PCBSchematics") (part "LEDSINGLESIDE"))
    )
    (comp (ref "LC9")
      (value "LEDSINGLESIDE")
      (footprint "LedSingleSide")
      (libsource (lib "PCBSchematics") (part "LEDSINGLESIDE"))
    )
    (comp (ref "LED1-8")
      (value "LEDindicator")
      (footprint "LEDindicator")
      (libsource (lib "Schlib1") (part "LEDindicator"))
    )
    (comp (ref "LED1-9")
      (value "LEDindicator")
      (footprint "LEDindicator")
      (libsource (lib "Schlib1") (part "LEDindicator"))
    )
    (comp (ref "LED1-10")
      (value "LEDindicator")
      (footprint "LEDindicator")
      (libsource (lib "Schlib1") (part "LEDindicator"))
    )
    (comp (ref "LED1-11")
      (value "LEDindicator")
      (footprint "LEDIndicator")
      (libsource (lib "Schlib1") (part "LEDindicator"))
    )
    (comp (ref "LED1-12")
      (value "LEDindicator")
      (footprint "LEDindicator")
      (libsource (lib "Schlib1") (part "LEDindicator"))
    )
    (comp (ref "LED1-13")
      (value "LEDindicator")
      (footprint "LEDindicator")
      (libsource (lib "Schlib1") (part "LEDindicator"))
    )
    (comp (ref "LED1-14")
      (value "LEDindicator")
      (footprint "LEDindicator")
      (libsource (lib "Schlib1") (part "LEDindicator"))
    )
    (comp (ref "LvL-1")
      (value "LevelShift_8")
      (footprint "24-TSSOP")
      (libsource (lib "PCBSchematics") (part "LevelShift_8"))
    )
    (comp (ref "LvL-2")
      (value "LevelShift_8")
      (footprint "24-TSSOP")
      (libsource (lib "PCBSchematics") (part "LevelShift_8"))
    )
    (comp (ref "LvL-3")
      (value "LevelShift_8")
      (footprint "24-TSSOP")
      (libsource (lib "PCBSchematics") (part "LevelShift_8"))
    )
    (comp (ref "LVL_GPIO13")
      (value "LevelShift_1")
      (footprint "6-TSSOP / SC-70-6")
      (libsource (lib "PCBSchematics") (part "LevelShift_1"))
    )
    (comp (ref "LVL_GPIO25")
      (value "LevelShift_1")
      (footprint "6-TSSOP / SC-70-6")
      (libsource (lib "PCBSchematics") (part "LevelShift_1"))
    )
    (comp (ref "LVL_GPIO26")
      (value "LevelShift_1")
      (footprint "6-TSSOP / SC-70-6")
      (libsource (lib "PCBSchematics") (part "LevelShift_1"))
    )
    (comp (ref "LVL_GPIO27")
      (value "LevelShift_1")
      (footprint "6-TSSOP / SC-70-6")
      (libsource (lib "PCBSchematics") (part "LevelShift_1"))
    )
    (comp (ref "LVL_GPIO28")
      (value "LevelShift_1")
      (footprint "6-TSSOP / SC-70-6")
      (libsource (lib "PCBSchematics") (part "LevelShift_1"))
    )
    (comp (ref "LVL_GPIO31")
      (value "LevelShift_1")
      (footprint "6-TSSOP / SC-70-6")
      (libsource (lib "PCBSchematics") (part "LevelShift_1"))
    )
    (comp (ref "LVL_GPIO32")
      (value "LevelShift_1")
      (footprint "6-TSSOP / SC-70-6")
      (libsource (lib "PCBSchematics") (part "LevelShift_1"))
    )
    (comp (ref "MCU1")
      (value "Teensy4p1")
      (footprint "Teensy4p1")
      (libsource (lib "PCBSchematics") (part "Teensy4p1"))
    )
    (comp (ref "N1") (value "NOT") (footprint "SOT23-5") (libsource (lib "PCBSchematics") (part "NOT")))
    (comp (ref "N2") (value "NOT") (footprint "SOT23-5") (libsource (lib "PCBSchematics") (part "NOT")))
    (comp (ref "NOT_OK")
      (value "LEDindicator")
      (footprint "LEDindicator")
      (libsource (lib "Schlib1") (part "LEDindicator"))
    )
    (comp (ref "OK")
      (value "LEDindicator")
      (footprint "LEDindicator")
      (libsource (lib "Schlib1") (part "LEDindicator"))
    )
    (comp (ref "OUT(5V)-1")
      (value "SMA_Female")
      (footprint "SMA_Ferrite")
      (libsource (lib "PCBSchematics") (part "SMA_Female"))
    )
    (comp (ref "OUT(5V)-2")
      (value "SMA_Female")
      (footprint "SMA_Ferrite")
      (libsource (lib "PCBSchematics") (part "SMA_Female"))
    )
    (comp (ref "OUT(5V)-3")
      (value "SMA_Female")
      (footprint "SMA_Ferrite")
      (libsource (lib "PCBSchematics") (part "SMA_Female"))
    )
    (comp (ref "OUT(5V)-4")
      (value "SMA_Female")
      (footprint "SMA_Ferrite")
      (libsource (lib "PCBSchematics") (part "SMA_Female"))
    )
    (comp (ref "PS1")
      (value "PS1")
      (footprint "PowerSupplySwitch")
      (description "PowerSupplySwitching")
      (libsource (lib "Schlib1") (part "PowerSupplySwitching"))
    )
    (comp (ref "PWM1")
      (value "PWM28")
      (footprint "28-TSSOP")
      (description "PWM")
      (libsource (lib "Schlib1") (part "PWM28"))
    )
    (comp (ref "PWM2")
      (value "PWM28")
      (footprint "28-TSSOP")
      (description "PWM")
      (libsource (lib "Schlib1") (part "PWM28"))
    )
    (comp (ref "R1-1") (value "10k") (footprint "0805") (libsource (lib "PCBSchematics") (part "Res1")))
    (comp (ref "R1-2") (value "10k") (footprint "0805") (libsource (lib "PCBSchematics") (part "Res1")))
    (comp (ref "R1-5") (value "3.3k") (footprint "0805") (libsource (lib "PCBSchematics") (part "Res1")))
    (comp (ref "R1-6") (value "3.3k") (footprint "0805") (libsource (lib "PCBSchematics") (part "Res1")))
    (comp (ref "R1-7") (value "10k") (footprint "0805") (libsource (lib "PCBSchematics") (part "Res1")))
    (comp (ref "R1-8") (value "10k") (footprint "0805") (libsource (lib "PCBSchematics") (part "Res1")))
    (comp (ref "R1-9") (value "10k") (footprint "0805") (libsource (lib "PCBSchematics") (part "Res1")))
    (comp (ref "R1-10") (value "10k") (footprint "0805") (libsource (lib "PCBSchematics") (part "Res1")))
    (comp (ref "R1-11") (value "10k") (footprint "0805") (libsource (lib "PCBSchematics") (part "Res1")))
    (comp (ref "R1-12") (value "10k") (footprint "0805") (libsource (lib "PCBSchematics") (part "Res1")))
    (comp (ref "R1-13") (value "10k") (footprint "0805") (libsource (lib "PCBSchematics") (part "Res1")))
    (comp (ref "R1-14") (value "10k") (footprint "0805") (libsource (lib "PCBSchematics") (part "Res1")))
    (comp (ref "R1-15") (value "10k") (footprint "0805") (libsource (lib "PCBSchematics") (part "Res1")))
    (comp (ref "R1-16") (value "10k") (footprint "0805") (libsource (lib "PCBSchematics") (part "Res1")))
    (comp (ref "R1-17") (value "10k") (footprint "0805") (libsource (lib "PCBSchematics") (part "Res1")))
    (comp (ref "R1-18") (value "10k") (footprint "0805") (libsource (lib "PCBSchematics") (part "Res1")))
    (comp (ref "R1-19") (value "10k") (footprint "0805") (libsource (lib "PCBSchematics") (part "Res1")))
    (comp (ref "R1-20") (value "10k") (footprint "0805") (libsource (lib "PCBSchematics") (part "Res1")))
    (comp (ref "R1-21") (value "10k") (footprint "0805") (libsource (lib "PCBSchematics") (part "Res1")))
    (comp (ref "R1-22") (value "10k") (footprint "0805") (libsource (lib "PCBSchematics") (part "Res1")))
    (comp (ref "R1-23") (value "10k") (footprint "0805") (libsource (lib "PCBSchematics") (part "Res1")))
    (comp (ref "R1-24") (value "10k") (footprint "0805") (libsource (lib "PCBSchematics") (part "Res1")))
    (comp (ref "R1-25") (value "10k") (footprint "0805") (libsource (lib "PCBSchematics") (part "Res1")))
    (comp (ref "R1-26") (value "10k") (footprint "0805") (libsource (lib "PCBSchematics") (part "Res1")))
    (comp (ref "R1-27") (value "10k") (footprint "0805") (libsource (lib "PCBSchematics") (part "Res1")))
    (comp (ref "R1-28") (value "10k") (footprint "0805") (libsource (lib "PCBSchematics") (part "Res1")))
    (comp (ref "R1-29") (value "10k") (footprint "0805") (libsource (lib "PCBSchematics") (part "Res1")))
    (comp (ref "R1-30")
      (value "10K")
      (footprint "0805")
      (description "Resistor")
      (libsource (lib "Schlib1") (part "Res1"))
    )
    (comp (ref "R1-31")
      (value "10K")
      (footprint "0805")
      (description "Resistor")
      (libsource (lib "Schlib1") (part "Res1"))
    )
    (comp (ref "R1-32")
      (value "10K")
      (footprint "0805")
      (description "Resistor")
      (libsource (lib "Schlib1") (part "Res1"))
    )
    (comp (ref "R1-33")
      (value "3k3 PU")
      (footprint "0805")
      (description "Resistor")
      (libsource (lib "Schlib1") (part "Res1"))
    )
    (comp (ref "R1-35")
      (value "PU")
      (footprint "0603")
      (description "Resistor")
      (libsource (lib "Schlib1") (part "Res1"))
    )
    (comp (ref "R1-36")
      (value "PU")
      (footprint "0603")
      (description "Resistor")
      (libsource (lib "Schlib1") (part "Res1"))
    )
    (comp (ref "R1-37")
      (value "PU")
      (footprint "0603")
      (description "Resistor")
      (libsource (lib "Schlib1") (part "Res1"))
    )
    (comp (ref "R1-38")
      (value "PU")
      (footprint "0603")
      (description "Resistor")
      (libsource (lib "Schlib1") (part "Res1"))
    )
    (comp (ref "R1-39")
      (value "PU")
      (footprint "0603")
      (description "Resistor")
      (libsource (lib "Schlib1") (part "Res1"))
    )
    (comp (ref "R2-1")
      (value "681")
      (footprint "1206")
      (description "Resistor")
      (libsource (lib "Schlib1") (part "Res1"))
    )
    (comp (ref "R3-3") (value "0") (footprint "0805") (libsource (lib "PCBSchematics") (part "Res1")))
    (comp (ref "R3-4")
      (value "NC or short")
      (footprint "0805")
      (libsource (lib "PCBSchematics") (part "Res1"))
    )
    (comp (ref "R3-5")
      (value "NC or short")
      (footprint "0805")
      (libsource (lib "PCBSchematics") (part "Res1"))
    )
    (comp (ref "R4-3") (value "NC") (footprint "0805") (libsource (lib "PCBSchematics") (part "Res1")))
    (comp (ref "R4-4") (value "NC") (footprint "0805") (libsource (lib "PCBSchematics") (part "Res1")))
    (comp (ref "R4-5") (value "NC") (footprint "0805") (libsource (lib "PCBSchematics") (part "Res1")))
    (comp (ref "R4-5B") (value "NC") (footprint "0805") (libsource (lib "PCBSchematics") (part "Res1")))
    (comp (ref "R5-1") (value "0") (footprint "0805") (libsource (lib "PCBSchematics") (part "Res1")))
    (comp (ref "R5-2") (value "0") (footprint "0805") (libsource (lib "PCBSchematics") (part "Res1")))
    (comp (ref "R5-3") (value "0") (footprint "0805") (libsource (lib "PCBSchematics") (part "Res1")))
    (comp (ref "R5-4") (value "0") (footprint "0805") (libsource (lib "PCBSchematics") (part "Res1")))
    (comp (ref "R5-5") (value "0") (footprint "0805") (libsource (lib "PCBSchematics") (part "Res1")))
    (comp (ref "R5-6") (value "0") (footprint "0805") (libsource (lib "PCBSchematics") (part "Res1")))
    (comp (ref "R5-7") (value "0") (footprint "0805") (libsource (lib "PCBSchematics") (part "Res1")))
    (comp (ref "R5-8") (value "0") (footprint "0805") (libsource (lib "PCBSchematics") (part "Res1")))
    (comp (ref "R5-9") (value "0") (footprint "0805") (libsource (lib "PCBSchematics") (part "Res1")))
    (comp (ref "R6-1")
      (value "500")
      (footprint "0603")
      (description "Resistor")
      (libsource (lib "Schlib1") (part "Res1"))
    )
    (comp (ref "R6-1B")
      (value "500")
      (footprint "0603")
      (description "Resistor")
      (libsource (lib "Schlib1") (part "Res1"))
    )
    (comp (ref "R6-2")
      (value "500")
      (footprint "0603")
      (description "Resistor")
      (libsource (lib "Schlib1") (part "Res1"))
    )
    (comp (ref "R6-2B")
      (value "500")
      (footprint "0603")
      (description "Resistor")
      (libsource (lib "Schlib1") (part "Res1"))
    )
    (comp (ref "R6-3")
      (value "500")
      (footprint "0603")
      (description "Resistor")
      (libsource (lib "Schlib1") (part "Res1"))
    )
    (comp (ref "R6-4")
      (value "500")
      (footprint "0603")
      (description "Resistor")
      (libsource (lib "Schlib1") (part "Res1"))
    )
    (comp (ref "R6-5")
      (value "500")
      (footprint "0603")
      (description "Resistor")
      (libsource (lib "Schlib1") (part "Res1"))
    )
    (comp (ref "R6-6")
      (value "500")
      (footprint "0603")
      (description "Resistor")
      (libsource (lib "Schlib1") (part "Res1"))
    )
    (comp (ref "R6-7")
      (value "500")
      (footprint "0603")
      (description "Resistor")
      (libsource (lib "Schlib1") (part "Res1"))
    )
    (comp (ref "R6-8")
      (value "500")
      (footprint "0603")
      (description "Resistor")
      (libsource (lib "Schlib1") (part "Res1"))
    )
    (comp (ref "R6-9")
      (value "500")
      (footprint "0603")
      (description "Resistor")
      (libsource (lib "Schlib1") (part "Res1"))
    )
    (comp (ref "R6-10")
      (value "500")
      (footprint "0603")
      (description "Resistor")
      (libsource (lib "Schlib1") (part "Res1"))
    )
    (comp (ref "R6-11")
      (value "500")
      (footprint "0603")
      (description "Resistor")
      (libsource (lib "Schlib1") (part "Res1"))
    )
    (comp (ref "R6-12")
      (value "500")
      (footprint "0603")
      (description "Resistor")
      (libsource (lib "Schlib1") (part "Res1"))
    )
    (comp (ref "R6-13")
      (value "500")
      (footprint "0603")
      (description "Resistor")
      (libsource (lib "Schlib1") (part "Res1"))
    )
    (comp (ref "R6-14")
      (value "500")
      (footprint "0603")
      (description "Resistor")
      (libsource (lib "Schlib1") (part "Res1"))
    )
    (comp (ref "R7-1")
      (value "60k")
      (footprint "0603")
      (description "Resistor")
      (libsource (lib "Schlib1") (part "Res1"))
    )
    (comp (ref "R7-2")
      (value "60k")
      (footprint "0603")
      (description "Resistor")
      (libsource (lib "Schlib1") (part "Res1"))
    )
    (comp (ref "R7-3")
      (value "60k")
      (footprint "0603")
      (description "Resistor")
      (libsource (lib "Schlib1") (part "Res1"))
    )
    (comp (ref "R7-4")
      (value "60k")
      (footprint "0603")
      (description "Resistor")
      (libsource (lib "Schlib1") (part "Res1"))
    )
    (comp (ref "R7-5")
      (value "60k")
      (footprint "0603")
      (description "Resistor")
      (libsource (lib "Schlib1") (part "Res1"))
    )
    (comp (ref "R7-6")
      (value "60k")
      (footprint "0603")
      (description "Resistor")
      (libsource (lib "Schlib1") (part "Res1"))
    )
    (comp (ref "R7-7")
      (value "60k")
      (footprint "0603")
      (description "Resistor")
      (libsource (lib "Schlib1") (part "Res1"))
    )
    (comp (ref "R7-8")
      (value "60k")
      (footprint "0603")
      (description "Resistor")
      (libsource (lib "Schlib1") (part "Res1"))
    )
    (comp (ref "R9-1")
      (value "270k")
      (footprint "0603")
      (description "Resistor")
      (libsource (lib "Schlib1") (part "Res1"))
    )
    (comp (ref "R9-2")
      (value "270k")
      (footprint "0603")
      (description "Resistor")
      (libsource (lib "Schlib1") (part "Res1"))
    )
    (comp (ref "Ref1")
      (value "3V3Reference")
      (footprint "8-SOIC-NoHeatPad")
      (libsource (lib "Schlib1") (part "2V5Ref"))
    )
    (comp (ref "S1")
      (value "Switch_4")
      (footprint "20-HTSSOP")
      (libsource (lib "PCBSchematics") (part "Switch_4"))
    )
    (comp (ref "S2")
      (value "Switch_4")
      (footprint "20-HTSSOP")
      (libsource (lib "PCBSchematics") (part "Switch_4"))
    )
    (comp (ref "S3")
      (value "Switch_4")
      (footprint "20-HTSSOP")
      (libsource (lib "PCBSchematics") (part "Switch_4"))
    )
    (comp (ref "S4")
      (value "Switch_4")
      (footprint "20-HTSSOP")
      (libsource (lib "PCBSchematics") (part "Switch_4"))
    )
    (comp (ref "ShiftLED1")
      (value "LevelShift_1")
      (footprint "6-TSSOP / SC-70-6")
      (libsource (lib "PCBSchematics") (part "LevelShift_1"))
    )
    (comp (ref "ShiftLED2")
      (value "LevelShift_1")
      (footprint "6-TSSOP / SC-70-6")
      (libsource (lib "PCBSchematics") (part "LevelShift_1"))
    )
    (comp (ref "T1")
      (value "TEstPoint")
      (footprint "TestPoint")
      (libsource (lib "PCBSchematics") (part "TEstPoint"))
    )
    (comp (ref "T2")
      (value "TEstPoint")
      (footprint "TestPoint")
      (libsource (lib "PCBSchematics") (part "TEstPoint"))
    )
    (comp (ref "T3")
      (value "TEstPoint")
      (footprint "TestPoint")
      (libsource (lib "PCBSchematics") (part "TEstPoint"))
    )
    (comp (ref "Terminal1")
      (value "Header_16x2")
      (footprint "Header 2x16")
      (libsource (lib "PCBSchematics") (part "Header_16x2"))
    )
    (comp (ref "Timer1")
      (value "TImer_555")
      (footprint "8-SOIC-NoHeatPad")
      (libsource (lib "PCBSchematics") (part "TImer_555"))
    )
    (comp (ref "TVS-1")
      (value "TVS Diode Array")
      (footprint "16-SOIC")
      (libsource (lib "PCBSchematics") (part "TVS_Diode16"))
    )
    (comp (ref "TVS-2")
      (value "TVS Diode Array")
      (footprint "16-SOIC")
      (libsource (lib "PCBSchematics") (part "TVS_Diode16"))
    )
    (comp (ref "TVS-3V3-1")
      (value "TVS Diode Array")
      (footprint "16-SOIC")
      (libsource (lib "PCBSchematics") (part "TVS_Diode16"))
    )
    (comp (ref "TVS-3V3-2")
      (value "TVS Diode Array")
      (footprint "16-SOIC")
      (libsource (lib "PCBSchematics") (part "TVS_Diode16"))
    )
    (comp (ref "TVS-3V3-3")
      (value "TVS Diode Array")
      (footprint "16-SOIC")
      (libsource (lib "PCBSchematics") (part "TVS_Diode16"))
    )
    (comp (ref "TVS-3V3-4")
      (value "TVS Diode Array")
      (footprint "16-SOIC")
      (libsource (lib "PCBSchematics") (part "TVS_Diode16"))
    )
    (comp (ref "VReg1")
      (value "5VReg")
      (footprint "8-SOIC")
      (description "5V Regulator Low Noise")
      (libsource (lib "Schlib1") (part "5V Reg LowNoise"))
    )
    (comp (ref "VReg2")
      (value "3V3Reg")
      (footprint "8-SOIC")
      (description "3V3 Regulator Low Noise")
      (libsource (lib "Schlib1") (part "5V Reg LowNoise"))
    )
    (comp (ref "VReg3")
      (value "3.3V Regulator")
      (footprint "SOT23-5")
      (libsource (lib "Schlib1") (part "4V Regulator"))
    )
    (comp (ref "VReg5_2")
      (value "3.3V Regulator")
      (footprint "SOT23-5")
      (libsource (lib "Schlib1") (part "4V Regulator"))
    )
    (comp (ref "WD1") (value "Watchdog") (footprint "SOT23-5") (libsource (lib "Schlib1") (part "Watchdog")))
  )
  (nets
    (net (code "1") (name "/5VB_2") (class "Default")
      (node (ref "C1-25") (pin "1") (pinfunction "1_1") (pintype "passive"))
      (node (ref "J6") (pin "1") (pinfunction "1_1") (pintype "passive"))
      (node (ref "R9-2") (pin "2") (pinfunction "2_2") (pintype "passive"))
      (node (ref "Timer1") (pin "4") (pinfunction "RESET_4") (pintype "passive"))
      (node (ref "Timer1") (pin "8") (pinfunction "VCC_8") (pintype "passive"))
    )
    (net (code "2") (name "/ADC_1") (class "Default")
      (node (ref "J1-12") (pin "2") (pinfunction "2_2") (pintype "passive"))
      (node (ref "R5-1") (pin "1") (pinfunction "1_1") (pintype "passive"))
    )
    (net (code "3") (name "/ADC_1_E") (class "Default")
      (node (ref "H2") (pin "18") (pinfunction "18_18") (pintype "passive"))
      (node (ref "H3") (pin "7") (pinfunction "7_7") (pintype "passive"))
      (node (ref "J1-12") (pin "3") (pinfunction "3_3") (pintype "passive"))
    )
    (net (code "4") (name "/ADC_1_S") (class "Default")
      (node (ref "ADC1") (pin "1") (pinfunction "Centre_1") (pintype "passive"))
      (node (ref "J1-12") (pin "1") (pinfunction "1_1") (pintype "passive"))
    )
    (net (code "5") (name "/ADC_2") (class "Default")
      (node (ref "J1-13") (pin "2") (pinfunction "2_2") (pintype "passive"))
      (node (ref "R5-2") (pin "1") (pinfunction "1_1") (pintype "passive"))
    )
    (net (code "6") (name "/ADC_2_E") (class "Default")
      (node (ref "H3") (pin "8") (pinfunction "8_8") (pintype "passive"))
      (node (ref "J1-13") (pin "3") (pinfunction "3_3") (pintype "passive"))
    )
    (net (code "7") (name "/ADC_2_S") (class "Default")
      (node (ref "ADC2") (pin "1") (pinfunction "Centre_1") (pintype "passive"))
      (node (ref "J1-13") (pin "1") (pinfunction "1_1") (pintype "passive"))
    )
    (net (code "8") (name "/ADC_3") (class "Default")
      (node (ref "J1-14") (pin "2") (pinfunction "2_2") (pintype "passive"))
      (node (ref "R5-3") (pin "1") (pinfunction "1_1") (pintype "passive"))
    )
    (net (code "9") (name "/ADC_3_E") (class "Default")
      (node (ref "H4") (pin "7") (pinfunction "7_7") (pintype "passive"))
      (node (ref "J1-14") (pin "3") (pinfunction "3_3") (pintype "passive"))
    )
    (net (code "10") (name "/ADC_3_S") (class "Default")
      (node (ref "ADC3") (pin "1") (pinfunction "Centre_1") (pintype "passive"))
      (node (ref "J1-14") (pin "1") (pinfunction "1_1") (pintype "passive"))
    )
    (net (code "11") (name "/ADC_4") (class "Default")
      (node (ref "J1-15") (pin "2") (pinfunction "2_2") (pintype "passive"))
      (node (ref "R5-4") (pin "1") (pinfunction "1_1") (pintype "passive"))
    )
    (net (code "12") (name "/ADC_4_E") (class "Default")
      (node (ref "H4") (pin "8") (pinfunction "8_8") (pintype "passive"))
      (node (ref "J1-15") (pin "3") (pinfunction "3_3") (pintype "passive"))
    )
    (net (code "13") (name "/ADC_4_S") (class "Default")
      (node (ref "ADC4") (pin "1") (pinfunction "Centre_1") (pintype "passive"))
      (node (ref "J1-15") (pin "1") (pinfunction "1_1") (pintype "passive"))
    )
    (net (code "14") (name "/ADC_5") (class "Default")
      (node (ref "ADC5") (pin "1") (pinfunction "Centre_1") (pintype "passive"))
      (node (ref "R5-5") (pin "1") (pinfunction "1_1") (pintype "passive"))
    )
    (net (code "15") (name "/ADC_6") (class "Default")
      (node (ref "ADC6") (pin "1") (pinfunction "Centre_1") (pintype "passive"))
      (node (ref "R5-6") (pin "1") (pinfunction "1_1") (pintype "passive"))
    )
    (net (code "16") (name "/ADC_7") (class "Default")
      (node (ref "ADC7") (pin "1") (pinfunction "Centre_1") (pintype "passive"))
      (node (ref "R5-7") (pin "1") (pinfunction "1_1") (pintype "passive"))
    )
    (net (code "17") (name "/ADC_8") (class "Default")
      (node (ref "ADC8") (pin "1") (pinfunction "Centre_1") (pintype "passive"))
      (node (ref "R5-8") (pin "1") (pinfunction "1_1") (pintype "passive"))
    )
    (net (code "18") (name "/AD_1") (class "Default")
      (node (ref "ADC") (pin "1") (pinfunction "CH0_1") (pintype "passive"))
      (node (ref "C5-1") (pin "2") (pinfunction "2_2") (pintype "passive"))
      (node (ref "R5-1") (pin "2") (pinfunction "2_2") (pintype "passive"))
      (node (ref "TVS-3V3-1") (pin "16") (pinfunction "C_16") (pintype "passive"))
    )
    (net (code "19") (name "/AD_2") (class "Default")
      (node (ref "ADC") (pin "2") (pinfunction "CH1_2") (pintype "passive"))
      (node (ref "C5-2") (pin "2") (pinfunction "2_2") (pintype "passive"))
      (node (ref "R5-2") (pin "2") (pinfunction "2_2") (pintype "passive"))
      (node (ref "TVS-3V3-1") (pin "15") (pinfunction "C_15") (pintype "passive"))
    )
    (net (code "20") (name "/AD_3") (class "Default")
      (node (ref "ADC") (pin "3") (pinfunction "CH2_3") (pintype "passive"))
      (node (ref "C5-3") (pin "2") (pinfunction "2_2") (pintype "passive"))
      (node (ref "R5-3") (pin "2") (pinfunction "2_2") (pintype "passive"))
      (node (ref "TVS-3V3-1") (pin "14") (pinfunction "C_14") (pintype "passive"))
    )
    (net (code "21") (name "/AD_4") (class "Default")
      (node (ref "ADC") (pin "4") (pinfunction "CH3_4") (pintype "passive"))
      (node (ref "C5-4") (pin "2") (pinfunction "2_2") (pintype "passive"))
      (node (ref "R5-4") (pin "2") (pinfunction "2_2") (pintype "passive"))
      (node (ref "TVS-3V3-1") (pin "13") (pinfunction "C_13") (pintype "passive"))
    )
    (net (code "22") (name "/AD_5") (class "Default")
      (node (ref "ADC") (pin "5") (pinfunction "CH4_5") (pintype "passive"))
      (node (ref "C5-5") (pin "2") (pinfunction "2_2") (pintype "passive"))
      (node (ref "R5-5") (pin "2") (pinfunction "2_2") (pintype "passive"))
      (node (ref "TVS-3V3-1") (pin "12") (pinfunction "C_12") (pintype "passive"))
    )
    (net (code "23") (name "/AD_6") (class "Default")
      (node (ref "ADC") (pin "6") (pinfunction "CH5_6") (pintype "passive"))
      (node (ref "C5-6") (pin "2") (pinfunction "2_2") (pintype "passive"))
      (node (ref "R5-6") (pin "2") (pinfunction "2_2") (pintype "passive"))
      (node (ref "TVS-3V3-1") (pin "11") (pinfunction "C_11") (pintype "passive"))
    )
    (net (code "24") (name "/AD_7") (class "Default")
      (node (ref "ADC") (pin "7") (pinfunction "CH6_7") (pintype "passive"))
      (node (ref "C5-7") (pin "2") (pinfunction "2_2") (pintype "passive"))
      (node (ref "R5-7") (pin "2") (pinfunction "2_2") (pintype "passive"))
      (node (ref "TVS-3V3-1") (pin "10") (pinfunction "C_10") (pintype "passive"))
    )
    (net (code "25") (name "/AD_8") (class "Default")
      (node (ref "ADC") (pin "8") (pinfunction "CH7_8") (pintype "passive"))
      (node (ref "C5-8") (pin "2") (pinfunction "2_2") (pintype "passive"))
      (node (ref "R5-8") (pin "2") (pinfunction "2_2") (pintype "passive"))
      (node (ref "TVS-3V3-1") (pin "9") (pinfunction "C_9") (pintype "passive"))
    )
    (net (code "26") (name "/Ain0") (class "Default")
      (node (ref "GPIO29") (pin "1") (pinfunction "Centre_1") (pintype "passive"))
      (node (ref "J1-20") (pin "3") (pinfunction "3_3") (pintype "passive"))
    )
    (net (code "27") (name "/Ain1") (class "Default")
      (node (ref "GPIO30") (pin "1") (pinfunction "Centre_1") (pintype "passive"))
      (node (ref "J1-21") (pin "3") (pinfunction "3_3") (pintype "passive"))
    )
    (net (code "28") (name "/CS0") (class "Default")
      (node (ref "DAC-1") (pin "2") (pinfunction "SYN~{C}_2") (pintype "passive"))
      (node (ref "MCU1") (pin "11") (pinfunction "10_11") (pintype "passive"))
    )
    (net (code "29") (name "/CS1") (class "Default")
      (node (ref "H3") (pin "17") (pinfunction "17_17") (pintype "passive"))
      (node (ref "H4") (pin "17") (pinfunction "17_17") (pintype "passive"))
      (node (ref "J5-1") (pin "5") (pinfunction "5_5") (pintype "passive"))
      (node (ref "MCU1") (pin "1") (pinfunction "0_1") (pintype "passive"))
    )
    (net (code "30") (name "/Cnt_In") (class "Default")
      (node (ref "J5-1") (pin "1") (pinfunction "1_1") (pintype "passive"))
      (node (ref "ShiftLED1") (pin "3") (pinfunction "A_3") (pintype "passive"))
    )
    (net (code "31") (name "/Cnt_Reset") (class "Default")
      (node (ref "Cnt1") (pin "13") (pinfunction "Disable_13") (pintype "passive"))
      (node (ref "Cnt1") (pin "15") (pinfunction "Reset_15") (pintype "passive"))
      (node (ref "Cnt2") (pin "13") (pinfunction "Disable_13") (pintype "passive"))
      (node (ref "Cnt2") (pin "15") (pinfunction "Reset_15") (pintype "passive"))
      (node (ref "Cnt3") (pin "13") (pinfunction "Disable_13") (pintype "passive"))
      (node (ref "Cnt3") (pin "15") (pinfunction "Reset_15") (pintype "passive"))
      (node (ref "R1-32") (pin "1") (pinfunction "1_1") (pintype "passive"))
      (node (ref "ShiftLED2") (pin "4") (pinfunction "B_4") (pintype "passive"))
    )
    (net (code "32") (name "/Count") (class "Default")
      (node (ref "Cnt1") (pin "14") (pinfunction "CLK_14") (pintype "passive"))
      (node (ref "ShiftLED1") (pin "4") (pinfunction "B_4") (pintype "passive"))
    )
    (net (code "33") (name "/D0") (class "Default")
      (node (ref "IN(5V)-1") (pin "1") (pinfunction "Centre_1") (pintype "passive"))
      (node (ref "LvL-1") (pin "21") (pinfunction "B1_21") (pintype "passive"))
      (node (ref "TVS-1") (pin "9") (pinfunction "C_9") (pintype "passive"))
    )
    (net (code "34") (name "/D1") (class "Default")
      (node (ref "IN(5V)-2") (pin "1") (pinfunction "Centre_1") (pintype "passive"))
      (node (ref "LvL-1") (pin "20") (pinfunction "B2_20") (pintype "passive"))
      (node (ref "TVS-1") (pin "10") (pinfunction "C_10") (pintype "passive"))
    )
    (net (code "35") (name "/D2") (class "Default")
      (node (ref "IN(5V)-3") (pin "1") (pinfunction "Centre_1") (pintype "passive"))
      (node (ref "LvL-1") (pin "19") (pinfunction "B3_19") (pintype "passive"))
      (node (ref "TVS-1") (pin "11") (pinfunction "C_11") (pintype "passive"))
    )
    (net (code "36") (name "/D3") (class "Default")
      (node (ref "IN(5V)-4") (pin "1") (pinfunction "Centre_1") (pintype "passive"))
      (node (ref "LvL-1") (pin "18") (pinfunction "B4_18") (pintype "passive"))
      (node (ref "TVS-1") (pin "12") (pinfunction "C_12") (pintype "passive"))
    )
    (net (code "37") (name "/D4") (class "Default")
      (node (ref "LvL-3") (pin "21") (pinfunction "B1_21") (pintype "passive"))
      (node (ref "OUT(5V)-1") (pin "1") (pinfunction "Centre_1") (pintype "passive"))
      (node (ref "TVS-1") (pin "13") (pinfunction "C_13") (pintype "passive"))
    )
    (net (code "38") (name "/D5") (class "Default")
      (node (ref "LvL-3") (pin "20") (pinfunction "B2_20") (pintype "passive"))
      (node (ref "OUT(5V)-2") (pin "1") (pinfunction "Centre_1") (pintype "passive"))
      (node (ref "TVS-1") (pin "14") (pinfunction "C_14") (pintype "passive"))
    )
    (net (code "39") (name "/D6") (class "Default")
      (node (ref "LvL-3") (pin "19") (pinfunction "B3_19") (pintype "passive"))
      (node (ref "OUT(5V)-3") (pin "1") (pinfunction "Centre_1") (pintype "passive"))
      (node (ref "TVS-1") (pin "15") (pinfunction "C_15") (pintype "passive"))
    )
    (net (code "40") (name "/D7") (class "Default")
      (node (ref "LvL-3") (pin "18") (pinfunction "B4_18") (pintype "passive"))
      (node (ref "OUT(5V)-4") (pin "1") (pinfunction "Centre_1") (pintype "passive"))
      (node (ref "TVS-1") (pin "16") (pinfunction "C_16") (pintype "passive"))
    )
    (net (code "41") (name "/D8") (class "Default")
      (node (ref "F1") (pin "2") (pinfunction "2_2") (pintype "passive"))
      (node (ref "J5-1") (pin "3") (pinfunction "3_3") (pintype "passive"))
      (node (ref "LvL-2") (pin "21") (pinfunction "B1_21") (pintype "passive"))
      (node (ref "TVS-2") (pin "9") (pinfunction "C_9") (pintype "passive"))
    )
    (net (code "42") (name "/D9") (class "Default")
      (node (ref "F2") (pin "2") (pinfunction "2_2") (pintype "passive"))
      (node (ref "LvL-2") (pin "20") (pinfunction "B2_20") (pintype "passive"))
      (node (ref "TVS-2") (pin "10") (pinfunction "C_10") (pintype "passive"))
    )
    (net (code "43") (name "/D10") (class "Default")
      (node (ref "F3") (pin "2") (pinfunction "2_2") (pintype "passive"))
      (node (ref "LvL-2") (pin "19") (pinfunction "B3_19") (pintype "passive"))
      (node (ref "TVS-2") (pin "11") (pinfunction "C_11") (pintype "passive"))
    )
    (net (code "44") (name "/D11") (class "Default")
      (node (ref "F4") (pin "2") (pinfunction "2_2") (pintype "passive"))
      (node (ref "J5-1") (pin "2") (pinfunction "2_2") (pintype "passive"))
      (node (ref "LvL-2") (pin "18") (pinfunction "B4_18") (pintype "passive"))
      (node (ref "TVS-2") (pin "12") (pinfunction "C_12") (pintype "passive"))
    )
    (net (code "45") (name "/D12") (class "Default")
      (node (ref "F5") (pin "2") (pinfunction "2_2") (pintype "passive"))
      (node (ref "LvL-2") (pin "17") (pinfunction "B5_17") (pintype "passive"))
      (node (ref "TVS-2") (pin "13") (pinfunction "C_13") (pintype "passive"))
    )
    (net (code "46") (name "/D13") (class "Default")
      (node (ref "J1-1") (pin "2") (pinfunction "2_2") (pintype "passive"))
      (node (ref "J1-5B") (pin "2") (pinfunction "2_2") (pintype "passive"))
    )
    (net (code "47") (name "/D13_Out") (class "Default")
      (node (ref "GPIO13") (pin "1") (pinfunction "Centre_1") (pintype "passive"))
      (node (ref "J1-1") (pin "3") (pinfunction "3_3") (pintype "passive"))
    )
    (net (code "48") (name "/D14") (class "Default")
      (node (ref "F7") (pin "2") (pinfunction "2_2") (pintype "passive"))
      (node (ref "LvL-2") (pin "16") (pinfunction "B6_16") (pintype "passive"))
      (node (ref "TVS-2") (pin "14") (pinfunction "C_14") (pintype "passive"))
    )
    (net (code "49") (name "/D15") (class "Default")
      (node (ref "F8") (pin "2") (pinfunction "2_2") (pintype "passive"))
      (node (ref "LvL-3") (pin "17") (pinfunction "B5_17") (pintype "passive"))
      (node (ref "TVS-2") (pin "15") (pinfunction "C_15") (pintype "passive"))
    )
    (net (code "50") (name "/D25") (class "Default")
      (node (ref "GPIO25") (pin "1") (pinfunction "Centre_1") (pintype "passive"))
      (node (ref "J1-6B") (pin "2") (pinfunction "2_2") (pintype "passive"))
    )
    (net (code "51") (name "/D26") (class "Default")
      (node (ref "GPIO26") (pin "1") (pinfunction "Centre_1") (pintype "passive"))
      (node (ref "J1-7B") (pin "2") (pinfunction "2_2") (pintype "passive"))
    )
    (net (code "52") (name "/D27") (class "Default")
      (node (ref "GPIO27") (pin "1") (pinfunction "Centre_1") (pintype "passive"))
      (node (ref "J1-8B") (pin "2") (pinfunction "2_2") (pintype "passive"))
    )
    (net (code "53") (name "/D28") (class "Default")
      (node (ref "GPIO28") (pin "1") (pinfunction "Centre_1") (pintype "passive"))
      (node (ref "J1-9B") (pin "2") (pinfunction "2_2") (pintype "passive"))
    )
    (net (code "54") (name "/DAC_1_E") (class "Default")
      (node (ref "H1") (pin "16") (pinfunction "16_16") (pintype "passive"))
      (node (ref "J1-16") (pin "3") (pinfunction "3_3") (pintype "passive"))
    )
    (net (code "55") (name "/DAC_1_S") (class "Default")
      (node (ref "DAC1") (pin "1") (pinfunction "Centre_1") (pintype "passive"))
      (node (ref "J1-16") (pin "1") (pinfunction "1_1") (pintype "passive"))
    )
    (net (code "56") (name "/DAC_2_E") (class "Default")
      (node (ref "H2") (pin "20") (pinfunction "20_20") (pintype "passive"))
      (node (ref "J1-17") (pin "3") (pinfunction "3_3") (pintype "passive"))
    )
    (net (code "57") (name "/DAC_2_S") (class "Default")
      (node (ref "DAC2") (pin "1") (pinfunction "Centre_1") (pintype "passive"))
      (node (ref "J1-17") (pin "1") (pinfunction "1_1") (pintype "passive"))
    )
    (net (code "58") (name "/DAC_3_E") (class "Default")
      (node (ref "H2") (pin "19") (pinfunction "19_19") (pintype "passive"))
      (node (ref "J1-18") (pin "3") (pinfunction "3_3") (pintype "passive"))
    )
    (net (code "59") (name "/DAC_3_S") (class "Default")
      (node (ref "DAC3") (pin "1") (pinfunction "Centre_1") (pintype "passive"))
      (node (ref "J1-18") (pin "1") (pinfunction "1_1") (pintype "passive"))
    )
    (net (code "60") (name "/DAC_4_E") (class "Default")
      (node (ref "H3") (pin "5") (pinfunction "5_5") (pintype "passive"))
      (node (ref "H4") (pin "5") (pinfunction "5_5") (pintype "passive"))
      (node (ref "J1-19") (pin "3") (pinfunction "3_3") (pintype "passive"))
    )
    (net (code "61") (name "/DAC_4_S") (class "Default")
      (node (ref "DAC4") (pin "1") (pinfunction "Centre_1") (pintype "passive"))
      (node (ref "J1-19") (pin "1") (pinfunction "1_1") (pintype "passive"))
    )
    (net (code "62") (name "/DD1") (class "Default")
      (node (ref "DAC-1") (pin "1") (pinfunction "LDA~{C}_1") (pintype "passive"))
      (node (ref "MCU1") (pin "42") (pinfunction "21_42") (pintype "passive"))
      (node (ref "R1-1") (pin "1") (pinfunction "1_1") (pintype "passive"))
    )
    (net (code "63") (name "/DD2") (class "Default")
      (node (ref "DAC-1") (pin "9") (pinfunction "CL~{R}_9") (pintype "passive"))
      (node (ref "MCU1") (pin "41") (pinfunction "20_41") (pintype "passive"))
      (node (ref "R1-2") (pin "2") (pinfunction "2_2") (pintype "passive"))
    )
    (net (code "64") (name "/DSpare") (class "Default")
      (node (ref "F6") (pin "2") (pinfunction "2_2") (pintype "passive"))
      (node (ref "J1-1") (pin "1") (pinfunction "1_1") (pintype "passive"))
    )
    (net (code "65") (name "/En7") (class "Default")
      (node (ref "LvL-1") (pin "22") (pinfunction "O~{E}_22") (pintype "passive"))
      (node (ref "LvL-2") (pin "22") (pinfunction "O~{E}_22") (pintype "passive"))
      (node (ref "LvL-3") (pin "22") (pinfunction "O~{E}_22") (pintype "passive"))
      (node (ref "PWM2") (pin "21") (pinfunction "LED14_21") (pintype "passive"))
      (node (ref "R1-11") (pin "2") (pinfunction "2_2") (pintype "passive"))
      (node (ref "R1-13") (pin "2") (pinfunction "2_2") (pintype "passive"))
      (node (ref "R1-9") (pin "2") (pinfunction "2_2") (pintype "passive"))
    )
    (net (code "66") (name "/En8") (class "Default")
      (node (ref "PWM2") (pin "22") (pinfunction "LED15_22") (pintype "passive"))
      (node (ref "R1-7") (pin "2") (pinfunction "2_2") (pintype "passive"))
      (node (ref "VReg3") (pin "3") (pinfunction "EN_3") (pintype "passive"))
    )
    (net (code "67") (name "/HB") (class "Default")
      (node (ref "DL-1") (pin "4") (pinfunction "Q_4") (pintype "passive"))
      (node (ref "H1") (pin "9") (pinfunction "9_9") (pintype "passive"))
      (node (ref "H2") (pin "14") (pinfunction "14_14") (pintype "passive"))
      (node (ref "H3") (pin "14") (pinfunction "14_14") (pintype "passive"))
      (node (ref "H4") (pin "14") (pinfunction "14_14") (pintype "passive"))
      (node (ref "JHB") (pin "3") (pinfunction "3_3") (pintype "passive"))
      (node (ref "LED1-14") (pin "2") (pinfunction "2_2") (pintype "passive"))
      (node (ref "N1") (pin "2") (pinfunction "IN_2") (pintype "passive"))
    )
    (net (code "68") (name "/HB_OUT") (class "Default")
      (node (ref "DL-1") (pin "1") (pinfunction "CP_1") (pintype "passive"))
      (node (ref "MCU1") (pin "32") (pinfunction "41_32") (pintype "passive"))
      (node (ref "WD1") (pin "4") (pinfunction "WDI_4") (pintype "passive"))
    )
    (net (code "69") (name "/H~{B}") (class "Default")
      (node (ref "JHB") (pin "2") (pinfunction "2_2") (pintype "passive"))
      (node (ref "PWM1") (pin "23") (pinfunction "OE_23") (pintype "passive"))
      (node (ref "PWM2") (pin "23") (pinfunction "OE_23") (pintype "passive"))
      (node (ref "ShiftLED2") (pin "3") (pinfunction "A_3") (pintype "passive"))
    )
    (net (code "70") (name "/LA0") (class "Default")
      (node (ref "Cnt1") (pin "3") (pinfunction "Q0_3") (pintype "passive"))
      (node (ref "LA0") (pin "1") (pinfunction "+_1") (pintype "passive"))
    )
    (net (code "71") (name "/LA1") (class "Default")
      (node (ref "Cnt1") (pin "2") (pinfunction "Q1_2") (pintype "passive"))
      (node (ref "LA1") (pin "1") (pinfunction "+_1") (pintype "passive"))
    )
    (net (code "72") (name "/LA2") (class "Default")
      (node (ref "Cnt1") (pin "4") (pinfunction "Q2_4") (pintype "passive"))
      (node (ref "LA2") (pin "1") (pinfunction "+_1") (pintype "passive"))
    )
    (net (code "73") (name "/LA3") (class "Default")
      (node (ref "Cnt1") (pin "7") (pinfunction "Q3_7") (pintype "passive"))
      (node (ref "LA3") (pin "1") (pinfunction "+_1") (pintype "passive"))
    )
    (net (code "74") (name "/LA4") (class "Default")
      (node (ref "Cnt1") (pin "10") (pinfunction "Q4_10") (pintype "passive"))
      (node (ref "LA4") (pin "1") (pinfunction "+_1") (pintype "passive"))
    )
    (net (code "75") (name "/LA5") (class "Default")
      (node (ref "Cnt1") (pin "1") (pinfunction "Q5_1") (pintype "passive"))
      (node (ref "LA5") (pin "1") (pinfunction "+_1") (pintype "passive"))
    )
    (net (code "76") (name "/LA6") (class "Default")
      (node (ref "Cnt1") (pin "5") (pinfunction "Q6_5") (pintype "passive"))
      (node (ref "LA6") (pin "1") (pinfunction "+_1") (pintype "passive"))
    )
    (net (code "77") (name "/LA7") (class "Default")
      (node (ref "Cnt1") (pin "6") (pinfunction "Q7_6") (pintype "passive"))
      (node (ref "LA7") (pin "1") (pinfunction "+_1") (pintype "passive"))
    )
    (net (code "78") (name "/LA8") (class "Default")
      (node (ref "Cnt1") (pin "9") (pinfunction "Q8_9") (pintype "passive"))
      (node (ref "LA8") (pin "1") (pinfunction "+_1") (pintype "passive"))
    )
    (net (code "79") (name "/LA9") (class "Default")
      (node (ref "Cnt1") (pin "11") (pinfunction "Q9_11") (pintype "passive"))
      (node (ref "LA9") (pin "1") (pinfunction "+_1") (pintype "passive"))
    )
    (net (code "80") (name "/LB0") (class "Default")
      (node (ref "Cnt2") (pin "3") (pinfunction "Q0_3") (pintype "passive"))
      (node (ref "LB0") (pin "1") (pinfunction "+_1") (pintype "passive"))
    )
    (net (code "81") (name "/LB1") (class "Default")
      (node (ref "Cnt2") (pin "2") (pinfunction "Q1_2") (pintype "passive"))
      (node (ref "LB1") (pin "1") (pinfunction "+_1") (pintype "passive"))
    )
    (net (code "82") (name "/LB2") (class "Default")
      (node (ref "Cnt2") (pin "4") (pinfunction "Q2_4") (pintype "passive"))
      (node (ref "LB2") (pin "1") (pinfunction "+_1") (pintype "passive"))
    )
    (net (code "83") (name "/LB3") (class "Default")
      (node (ref "Cnt2") (pin "7") (pinfunction "Q3_7") (pintype "passive"))
      (node (ref "LB3") (pin "1") (pinfunction "+_1") (pintype "passive"))
    )
    (net (code "84") (name "/LB4") (class "Default")
      (node (ref "Cnt2") (pin "10") (pinfunction "Q4_10") (pintype "passive"))
      (node (ref "LB4") (pin "1") (pinfunction "+_1") (pintype "passive"))
    )
    (net (code "85") (name "/LB5") (class "Default")
      (node (ref "Cnt2") (pin "1") (pinfunction "Q5_1") (pintype "passive"))
      (node (ref "LB5") (pin "1") (pinfunction "+_1") (pintype "passive"))
    )
    (net (code "86") (name "/LB6") (class "Default")
      (node (ref "Cnt2") (pin "5") (pinfunction "Q6_5") (pintype "passive"))
      (node (ref "LB6") (pin "1") (pinfunction "+_1") (pintype "passive"))
    )
    (net (code "87") (name "/LB7") (class "Default")
      (node (ref "Cnt2") (pin "6") (pinfunction "Q7_6") (pintype "passive"))
      (node (ref "LB7") (pin "1") (pinfunction "+_1") (pintype "passive"))
    )
    (net (code "88") (name "/LB8") (class "Default")
      (node (ref "Cnt2") (pin "9") (pinfunction "Q8_9") (pintype "passive"))
      (node (ref "LB8") (pin "1") (pinfunction "+_1") (pintype "passive"))
    )
    (net (code "89") (name "/LB9") (class "Default")
      (node (ref "Cnt2") (pin "11") (pinfunction "Q9_11") (pintype "passive"))
      (node (ref "LB9") (pin "1") (pinfunction "+_1") (pintype "passive"))
    )
    (net (code "90") (name "/LC0") (class "Default")
      (node (ref "Cnt3") (pin "3") (pinfunction "Q0_3") (pintype "passive"))
      (node (ref "LC0") (pin "1") (pinfunction "+_1") (pintype "passive"))
    )
    (net (code "91") (name "/LC1") (class "Default")
      (node (ref "Cnt3") (pin "2") (pinfunction "Q1_2") (pintype "passive"))
      (node (ref "LC1") (pin "1") (pinfunction "+_1") (pintype "passive"))
    )
    (net (code "92") (name "/LC2") (class "Default")
      (node (ref "Cnt3") (pin "4") (pinfunction "Q2_4") (pintype "passive"))
      (node (ref "LC2") (pin "1") (pinfunction "+_1") (pintype "passive"))
    )
    (net (code "93") (name "/LC3") (class "Default")
      (node (ref "Cnt3") (pin "7") (pinfunction "Q3_7") (pintype "passive"))
      (node (ref "LC3") (pin "1") (pinfunction "+_1") (pintype "passive"))
    )
    (net (code "94") (name "/LC4") (class "Default")
      (node (ref "Cnt3") (pin "10") (pinfunction "Q4_10") (pintype "passive"))
      (node (ref "LC4") (pin "1") (pinfunction "+_1") (pintype "passive"))
    )
    (net (code "95") (name "/LC5") (class "Default")
      (node (ref "Cnt3") (pin "1") (pinfunction "Q5_1") (pintype "passive"))
      (node (ref "LC5") (pin "1") (pinfunction "+_1") (pintype "passive"))
    )
    (net (code "96") (name "/LC6") (class "Default")
      (node (ref "Cnt3") (pin "5") (pinfunction "Q6_5") (pintype "passive"))
      (node (ref "LC6") (pin "1") (pinfunction "+_1") (pintype "passive"))
    )
    (net (code "97") (name "/LC7") (class "Default")
      (node (ref "Cnt3") (pin "6") (pinfunction "Q7_6") (pintype "passive"))
      (node (ref "LC7") (pin "1") (pinfunction "+_1") (pintype "passive"))
    )
    (net (code "98") (name "/LC8") (class "Default")
      (node (ref "Cnt3") (pin "9") (pinfunction "Q8_9") (pintype "passive"))
      (node (ref "LC8") (pin "1") (pinfunction "+_1") (pintype "passive"))
    )
    (net (code "99") (name "/LC9") (class "Default")
      (node (ref "Cnt3") (pin "11") (pinfunction "Q9_11") (pintype "passive"))
      (node (ref "LC9") (pin "1") (pinfunction "+_1") (pintype "passive"))
    )
    (net (code "100") (name "/MISO0") (class "Default")
      (node (ref "H3") (pin "19") (pinfunction "19_19") (pintype "passive"))
      (node (ref "H4") (pin "19") (pinfunction "19_19") (pintype "passive"))
      (node (ref "MCU1") (pin "13") (pinfunction "12_13") (pintype "passive"))
    )
    (net (code "101") (name "/P0") (class "Default")
      (node (ref "PWM1") (pin "6") (pinfunction "LED0_6") (pintype "passive"))
      (node (ref "R1-15") (pin "2") (pinfunction "2_2") (pintype "passive"))
    )
    (net (code "102") (name "/P1") (class "Default")
      (node (ref "PWM1") (pin "7") (pinfunction "LED1_7") (pintype "passive"))
      (node (ref "R1-14") (pin "2") (pinfunction "2_2") (pintype "passive"))
    )
    (net (code "103") (name "/P2") (class "Default")
      (node (ref "PWM1") (pin "8") (pinfunction "LED2_8") (pintype "passive"))
      (node (ref "R1-16") (pin "2") (pinfunction "2_2") (pintype "passive"))
    )
    (net (code "104") (name "/P3") (class "Default")
      (node (ref "PWM1") (pin "9") (pinfunction "LED3_9") (pintype "passive"))
      (node (ref "R1-17") (pin "2") (pinfunction "2_2") (pintype "passive"))
    )
    (net (code "105") (name "/P4") (class "Default")
      (node (ref "PWM1") (pin "10") (pinfunction "LED4_10") (pintype "passive"))
      (node (ref "R1-18") (pin "2") (pinfunction "2_2") (pintype "passive"))
    )
    (net (code "106") (name "/P5") (class "Default")
      (node (ref "PWM1") (pin "11") (pinfunction "LED5_11") (pintype "passive"))
      (node (ref "R1-19") (pin "2") (pinfunction "2_2") (pintype "passive"))
    )
    (net (code "107") (name "/P6") (class "Default")
      (node (ref "PWM1") (pin "12") (pinfunction "LED6_12") (pintype "passive"))
      (node (ref "R1-20") (pin "2") (pinfunction "2_2") (pintype "passive"))
    )
    (net (code "108") (name "/P7") (class "Default")
      (node (ref "PWM1") (pin "13") (pinfunction "LED7_13") (pintype "passive"))
      (node (ref "R1-21") (pin "2") (pinfunction "2_2") (pintype "passive"))
    )
    (net (code "109") (name "/P8") (class "Default")
      (node (ref "PWM1") (pin "15") (pinfunction "LED8_15") (pintype "passive"))
      (node (ref "R1-22") (pin "2") (pinfunction "2_2") (pintype "passive"))
    )
    (net (code "110") (name "/P9") (class "Default")
      (node (ref "PWM1") (pin "16") (pinfunction "LED9_16") (pintype "passive"))
      (node (ref "R1-23") (pin "2") (pinfunction "2_2") (pintype "passive"))
    )
    (net (code "111") (name "/P10") (class "Default")
      (node (ref "PWM1") (pin "17") (pinfunction "LED10_17") (pintype "passive"))
      (node (ref "R1-24") (pin "2") (pinfunction "2_2") (pintype "passive"))
    )
    (net (code "112") (name "/P11") (class "Default")
      (node (ref "PWM1") (pin "18") (pinfunction "LED11_18") (pintype "passive"))
      (node (ref "R1-25") (pin "2") (pinfunction "2_2") (pintype "passive"))
    )
    (net (code "113") (name "/P12") (class "Default")
      (node (ref "PWM1") (pin "19") (pinfunction "LED12_19") (pintype "passive"))
      (node (ref "R1-26") (pin "2") (pinfunction "2_2") (pintype "passive"))
    )
    (net (code "114") (name "/P13") (class "Default")
      (node (ref "PWM1") (pin "20") (pinfunction "LED13_20") (pintype "passive"))
      (node (ref "R1-27") (pin "2") (pinfunction "2_2") (pintype "passive"))
    )
    (net (code "115") (name "/P14") (class "Default")
      (node (ref "PWM1") (pin "21") (pinfunction "LED14_21") (pintype "passive"))
      (node (ref "R1-28") (pin "2") (pinfunction "2_2") (pintype "passive"))
    )
    (net (code "116") (name "/P15") (class "Default")
      (node (ref "PWM1") (pin "22") (pinfunction "LED15_22") (pintype "passive"))
      (node (ref "R1-29") (pin "2") (pinfunction "2_2") (pintype "passive"))
    )
    (net (code "117") (name "/PWM0") (class "Default")
      (node (ref "GPIO31") (pin "1") (pinfunction "Centre_1") (pintype "passive"))
      (node (ref "LVL_GPIO31") (pin "4") (pinfunction "B_4") (pintype "passive"))
    )
    (net (code "118") (name "/PWM0*") (class "Default")
      (node (ref "J1-22") (pin "3") (pinfunction "3_3") (pintype "passive"))
      (node (ref "LVL_GPIO31") (pin "3") (pinfunction "A_3") (pintype "passive"))
    )
    (net (code "119") (name "/PWM1") (class "Default")
      (node (ref "GPIO32") (pin "1") (pinfunction "Centre_1") (pintype "passive"))
      (node (ref "LVL_GPIO32") (pin "4") (pinfunction "B_4") (pintype "passive"))
    )
    (net (code "120") (name "/PWM1*") (class "Default")
      (node (ref "J1-23") (pin "3") (pinfunction "3_3") (pintype "passive"))
      (node (ref "LVL_GPIO32") (pin "3") (pinfunction "A_3") (pintype "passive"))
    )
    (net (code "121") (name "/Po0") (class "Default")
      (node (ref "S1") (pin "17") (pinfunction "LOAD1_17") (pintype "passive"))
      (node (ref "Terminal1") (pin "2") (pinfunction "2_2") (pintype "passive"))
    )
    (net (code "122") (name "/Po1") (class "Default")
      (node (ref "S1") (pin "16") (pinfunction "LOAD2_16") (pintype "passive"))
      (node (ref "Terminal1") (pin "4") (pinfunction "4_4") (pintype "passive"))
    )
    (net (code "123") (name "/Po2") (class "Default")
      (node (ref "S1") (pin "15") (pinfunction "LOAD3_15") (pintype "passive"))
      (node (ref "Terminal1") (pin "6") (pinfunction "6_6") (pintype "passive"))
    )
    (net (code "124") (name "/Po3") (class "Default")
      (node (ref "S1") (pin "14") (pinfunction "LOAD4_14") (pintype "passive"))
      (node (ref "Terminal1") (pin "8") (pinfunction "8_8") (pintype "passive"))
    )
    (net (code "125") (name "/Po4") (class "Default")
      (node (ref "S2") (pin "17") (pinfunction "LOAD1_17") (pintype "passive"))
      (node (ref "Terminal1") (pin "10") (pinfunction "10_10") (pintype "passive"))
    )
    (net (code "126") (name "/Po5") (class "Default")
      (node (ref "S2") (pin "16") (pinfunction "LOAD2_16") (pintype "passive"))
      (node (ref "Terminal1") (pin "12") (pinfunction "12_12") (pintype "passive"))
    )
    (net (code "127") (name "/Po6") (class "Default")
      (node (ref "S2") (pin "15") (pinfunction "LOAD3_15") (pintype "passive"))
      (node (ref "Terminal1") (pin "14") (pinfunction "14_14") (pintype "passive"))
    )
    (net (code "128") (name "/Po7") (class "Default")
      (node (ref "S2") (pin "14") (pinfunction "LOAD4_14") (pintype "passive"))
      (node (ref "Terminal1") (pin "16") (pinfunction "16_16") (pintype "passive"))
    )
    (net (code "129") (name "/Po8") (class "Default")
      (node (ref "S3") (pin "17") (pinfunction "LOAD1_17") (pintype "passive"))
      (node (ref "Terminal1") (pin "18") (pinfunction "18_18") (pintype "passive"))
    )
    (net (code "130") (name "/Po9") (class "Default")
      (node (ref "S3") (pin "16") (pinfunction "LOAD2_16") (pintype "passive"))
      (node (ref "Terminal1") (pin "20") (pinfunction "20_20") (pintype "passive"))
    )
    (net (code "131") (name "/Po10") (class "Default")
      (node (ref "S3") (pin "15") (pinfunction "LOAD3_15") (pintype "passive"))
      (node (ref "Terminal1") (pin "22") (pinfunction "22_22") (pintype "passive"))
    )
    (net (code "132") (name "/Po11") (class "Default")
      (node (ref "S3") (pin "14") (pinfunction "LOAD4_14") (pintype "passive"))
      (node (ref "Terminal1") (pin "24") (pinfunction "24_24") (pintype "passive"))
    )
    (net (code "133") (name "/Po12") (class "Default")
      (node (ref "S4") (pin "17") (pinfunction "LOAD1_17") (pintype "passive"))
      (node (ref "Terminal1") (pin "26") (pinfunction "26_26") (pintype "passive"))
    )
    (net (code "134") (name "/Po13") (class "Default")
      (node (ref "S4") (pin "16") (pinfunction "LOAD2_16") (pintype "passive"))
      (node (ref "Terminal1") (pin "28") (pinfunction "28_28") (pintype "passive"))
    )
    (net (code "135") (name "/Po14") (class "Default")
      (node (ref "S4") (pin "15") (pinfunction "LOAD3_15") (pintype "passive"))
      (node (ref "Terminal1") (pin "30") (pinfunction "30_30") (pintype "passive"))
    )
    (net (code "136") (name "/Po15") (class "Default")
      (node (ref "S4") (pin "14") (pinfunction "LOAD4_14") (pintype "passive"))
      (node (ref "Terminal1") (pin "32") (pinfunction "32_32") (pintype "passive"))
    )
    (net (code "137") (name "/SCL0") (class "Default")
      (node (ref "ADC") (pin "14") (pinfunction "SCL_14") (pintype "passive"))
      (node (ref "H1") (pin "18") (pinfunction "18_18") (pintype "passive"))
      (node (ref "H2") (pin "15") (pinfunction "15_15") (pintype "passive"))
      (node (ref "H3") (pin "11") (pinfunction "11_11") (pintype "passive"))
      (node (ref "H4") (pin "11") (pinfunction "11_11") (pintype "passive"))
      (node (ref "MCU1") (pin "40") (pinfunction "19_40") (pintype "passive"))
      (node (ref "PWM1") (pin "26") (pinfunction "SCL_26") (pintype "passive"))
      (node (ref "PWM2") (pin "26") (pinfunction "SCL_26") (pintype "passive"))
      (node (ref "R1-5") (pin "2") (pinfunction "2_2") (pintype "passive"))
    )
    (net (code "138") (name "/SDA0") (class "Default")
      (node (ref "ADC") (pin "15") (pinfunction "SDA_15") (pintype "passive"))
      (node (ref "H1") (pin "20") (pinfunction "20_20") (pintype "passive"))
      (node (ref "H2") (pin "17") (pinfunction "17_17") (pintype "passive"))
      (node (ref "H3") (pin "13") (pinfunction "13_13") (pintype "passive"))
      (node (ref "H4") (pin "13") (pinfunction "13_13") (pintype "passive"))
      (node (ref "MCU1") (pin "39") (pinfunction "18_39") (pintype "passive"))
      (node (ref "PWM1") (pin "27") (pinfunction "SDA_27") (pintype "passive"))
      (node (ref "PWM2") (pin "27") (pinfunction "SDA_27") (pintype "passive"))
      (node (ref "R1-6") (pin "2") (pinfunction "2_2") (pintype "passive"))
    )
    (net (code "139") (name "/T555") (class "Default")
      (node (ref "J5-1") (pin "4") (pinfunction "4_4") (pintype "passive"))
      (node (ref "R1-33") (pin "1") (pinfunction "1_1") (pintype "passive"))
      (node (ref "Timer1") (pin "3") (pinfunction "OUT_3") (pintype "passive"))
    )
    (net (code "140") (name "/TT") (class "Default")
      (node (ref "C9-1") (pin "2") (pinfunction "2_2") (pintype "passive"))
      (node (ref "R9-1") (pin "1") (pinfunction "1_1") (pintype "passive"))
      (node (ref "Timer1") (pin "2") (pinfunction "TRIG_2") (pintype "passive"))
      (node (ref "Timer1") (pin "6") (pinfunction "THRES_6") (pintype "passive"))
    )
    (net (code "141") (name "/d0*") (class "Default")
      (node (ref "LvL-1") (pin "3") (pinfunction "A1_3") (pintype "passive"))
      (node (ref "MCU1") (pin "2") (pinfunction "1_2") (pintype "passive"))
    )
    (net (code "142") (name "/d1*") (class "Default")
      (node (ref "LvL-1") (pin "4") (pinfunction "A2_4") (pintype "passive"))
      (node (ref "MCU1") (pin "3") (pinfunction "2_3") (pintype "passive"))
    )
    (net (code "143") (name "/d2*") (class "Default")
      (node (ref "LvL-1") (pin "5") (pinfunction "A3_5") (pintype "passive"))
      (node (ref "MCU1") (pin "4") (pinfunction "3_4") (pintype "passive"))
    )
    (net (code "144") (name "/d3*") (class "Default")
      (node (ref "LvL-1") (pin "6") (pinfunction "A4_6") (pintype "passive"))
      (node (ref "MCU1") (pin "5") (pinfunction "4_5") (pintype "passive"))
    )
    (net (code "145") (name "/d4*") (class "Default")
      (node (ref "LvL-3") (pin "3") (pinfunction "A1_3") (pintype "passive"))
      (node (ref "MCU1") (pin "6") (pinfunction "5_6") (pintype "passive"))
    )
    (net (code "146") (name "/d5*") (class "Default")
      (node (ref "LvL-3") (pin "4") (pinfunction "A2_4") (pintype "passive"))
      (node (ref "MCU1") (pin "7") (pinfunction "6_7") (pintype "passive"))
    )
    (net (code "147") (name "/d6*") (class "Default")
      (node (ref "LvL-3") (pin "5") (pinfunction "A3_5") (pintype "passive"))
      (node (ref "MCU1") (pin "8") (pinfunction "7_8") (pintype "passive"))
    )
    (net (code "148") (name "/d7*") (class "Default")
      (node (ref "LvL-3") (pin "6") (pinfunction "A4_6") (pintype "passive"))
      (node (ref "MCU1") (pin "9") (pinfunction "8_9") (pintype "passive"))
    )
    (net (code "149") (name "/d8*") (class "Default")
      (node (ref "LvL-2") (pin "3") (pinfunction "A1_3") (pintype "passive"))
      (node (ref "MCU1") (pin "16") (pinfunction "25_16") (pintype "passive"))
    )
    (net (code "150") (name "/d9*") (class "Default")
      (node (ref "LvL-2") (pin "4") (pinfunction "A2_4") (pintype "passive"))
      (node (ref "MCU1") (pin "17") (pinfunction "26_17") (pintype "passive"))
    )
    (net (code "151") (name "/d10*") (class "Default")
      (node (ref "LvL-2") (pin "5") (pinfunction "A3_5") (pintype "passive"))
      (node (ref "MCU1") (pin "18") (pinfunction "27_18") (pintype "passive"))
    )
    (net (code "152") (name "/d11*") (class "Default")
      (node (ref "LvL-2") (pin "6") (pinfunction "A4_6") (pintype "passive"))
      (node (ref "MCU1") (pin "19") (pinfunction "28_19") (pintype "passive"))
    )
    (net (code "153") (name "/d12*") (class "Default")
      (node (ref "LvL-2") (pin "7") (pinfunction "A5_7") (pintype "passive"))
      (node (ref "MCU1") (pin "20") (pinfunction "29_20") (pintype "passive"))
    )
    (net (code "154") (name "/d13*") (class "Default")
      (node (ref "J1-5B") (pin "3") (pinfunction "3_3") (pintype "passive"))
      (node (ref "LVL_GPIO13") (pin "3") (pinfunction "A_3") (pintype "passive"))
      (node (ref "MCU1") (pin "21") (pinfunction "30_21") (pintype "passive"))
      (node (ref "R1-35") (pin "1") (pinfunction "1_1") (pintype "passive"))
      (node (ref "TVS-2") (pin "16") (pinfunction "C_16") (pintype "passive"))
    )
    (net (code "155") (name "/d14*") (class "Default")
      (node (ref "LvL-2") (pin "8") (pinfunction "A6_8") (pintype "passive"))
      (node (ref "MCU1") (pin "22") (pinfunction "31_22") (pintype "passive"))
    )
    (net (code "156") (name "/d15*") (class "Default")
      (node (ref "LvL-3") (pin "7") (pinfunction "A5_7") (pintype "passive"))
      (node (ref "MCU1") (pin "23") (pinfunction "32_23") (pintype "passive"))
    )
    (net (code "157") (name "/d16") (class "Default")
      (node (ref "H1") (pin "1") (pinfunction "1_1") (pintype "passive"))
      (node (ref "MCU1") (pin "24") (pinfunction "33_24") (pintype "passive"))
      (node (ref "TVS-3V3-2") (pin "16") (pinfunction "C_16") (pintype "passive"))
    )
    (net (code "158") (name "/d17") (class "Default")
      (node (ref "H1") (pin "2") (pinfunction "2_2") (pintype "passive"))
      (node (ref "MCU1") (pin "25") (pinfunction "34_25") (pintype "passive"))
      (node (ref "TVS-3V3-2") (pin "15") (pinfunction "C_15") (pintype "passive"))
    )
    (net (code "159") (name "/d18") (class "Default")
      (node (ref "H1") (pin "3") (pinfunction "3_3") (pintype "passive"))
      (node (ref "MCU1") (pin "26") (pinfunction "35_26") (pintype "passive"))
      (node (ref "TVS-3V3-2") (pin "14") (pinfunction "C_14") (pintype "passive"))
    )
    (net (code "160") (name "/d19") (class "Default")
      (node (ref "H1") (pin "4") (pinfunction "4_4") (pintype "passive"))
      (node (ref "MCU1") (pin "27") (pinfunction "36_27") (pintype "passive"))
      (node (ref "TVS-3V3-2") (pin "13") (pinfunction "C_13") (pintype "passive"))
    )
    (net (code "161") (name "/d20") (class "Default")
      (node (ref "H1") (pin "5") (pinfunction "5_5") (pintype "passive"))
      (node (ref "MCU1") (pin "28") (pinfunction "37_28") (pintype "passive"))
      (node (ref "TVS-3V3-2") (pin "12") (pinfunction "C_12") (pintype "passive"))
    )
    (net (code "162") (name "/d21") (class "Default")
      (node (ref "H1") (pin "6") (pinfunction "6_6") (pintype "passive"))
      (node (ref "MCU1") (pin "29") (pinfunction "38_29") (pintype "passive"))
      (node (ref "TVS-3V3-2") (pin "11") (pinfunction "C_11") (pintype "passive"))
    )
    (net (code "163") (name "/d22") (class "Default")
      (node (ref "H1") (pin "7") (pinfunction "7_7") (pintype "passive"))
      (node (ref "MCU1") (pin "30") (pinfunction "39_30") (pintype "passive"))
      (node (ref "TVS-3V3-2") (pin "10") (pinfunction "C_10") (pintype "passive"))
    )
    (net (code "164") (name "/d23") (class "Default")
      (node (ref "H1") (pin "8") (pinfunction "8_8") (pintype "passive"))
      (node (ref "MCU1") (pin "31") (pinfunction "40_31") (pintype "passive"))
      (node (ref "TVS-3V3-2") (pin "9") (pinfunction "C_9") (pintype "passive"))
    )
    (net (code "165") (name "/d25*") (class "Default")
      (node (ref "J1-6B") (pin "3") (pinfunction "3_3") (pintype "passive"))
      (node (ref "LVL_GPIO25") (pin "3") (pinfunction "A_3") (pintype "passive"))
      (node (ref "MCU1") (pin "43") (pinfunction "22_43") (pintype "passive"))
      (node (ref "R1-36") (pin "1") (pinfunction "1_1") (pintype "passive"))
      (node (ref "TVS-3V3-4") (pin "16") (pinfunction "C_16") (pintype "passive"))
    )
    (net (code "166") (name "/d26*") (class "Default")
      (node (ref "J1-7B") (pin "3") (pinfunction "3_3") (pintype "passive"))
      (node (ref "LVL_GPIO26") (pin "3") (pinfunction "A_3") (pintype "passive"))
      (node (ref "MCU1") (pin "44") (pinfunction "23_44") (pintype "passive"))
      (node (ref "R1-37") (pin "1") (pinfunction "1_1") (pintype "passive"))
      (node (ref "TVS-3V3-4") (pin "15") (pinfunction "C_15") (pintype "passive"))
    )
    (net (code "167") (name "/d27*") (class "Default")
      (node (ref "J1-8B") (pin "3") (pinfunction "3_3") (pintype "passive"))
      (node (ref "LVL_GPIO27") (pin "3") (pinfunction "A_3") (pintype "passive"))
      (node (ref "MCU1") (pin "10") (pinfunction "9_10") (pintype "passive"))
      (node (ref "R1-38") (pin "1") (pinfunction "1_1") (pintype "passive"))
      (node (ref "TVS-3V3-4") (pin "14") (pinfunction "C_14") (pintype "passive"))
    )
    (net (code "168") (name "/d28*") (class "Default")
      (node (ref "J1-9B") (pin "3") (pinfunction "3_3") (pintype "passive"))
      (node (ref "LVL_GPIO28") (pin "3") (pinfunction "A_3") (pintype "passive"))
      (node (ref "MCU1") (pin "15") (pinfunction "24_15") (pintype "passive"))
      (node (ref "R1-39") (pin "1") (pinfunction "1_1") (pintype "passive"))
      (node (ref "TVS-3V3-4") (pin "13") (pinfunction "C_13") (pintype "passive"))
    )
    (net (code "169") (name "/d29") (class "Default")
      (node (ref "J1-20") (pin "2") (pinfunction "2_2") (pintype "passive"))
      (node (ref "MCU1") (pin "37") (pinfunction "16_37") (pintype "passive"))
      (node (ref "TVS-3V3-4") (pin "9") (pinfunction "C_9") (pintype "passive"))
    )
    (net (code "170") (name "/d29_E") (class "Default")
      (node (ref "H2") (pin "11") (pinfunction "11_11") (pintype "passive"))
      (node (ref "H3") (pin "10") (pinfunction "10_10") (pintype "passive"))
      (node (ref "H4") (pin "10") (pinfunction "10_10") (pintype "passive"))
      (node (ref "J1-20") (pin "1") (pinfunction "1_1") (pintype "passive"))
    )
    (net (code "171") (name "/d30") (class "Default")
      (node (ref "J1-21") (pin "2") (pinfunction "2_2") (pintype "passive"))
      (node (ref "MCU1") (pin "38") (pinfunction "17_38") (pintype "passive"))
      (node (ref "TVS-3V3-4") (pin "10") (pinfunction "C_10") (pintype "passive"))
    )
    (net (code "172") (name "/d30_E") (class "Default")
      (node (ref "H2") (pin "13") (pinfunction "13_13") (pintype "passive"))
      (node (ref "H3") (pin "9") (pinfunction "9_9") (pintype "passive"))
      (node (ref "H4") (pin "9") (pinfunction "9_9") (pintype "passive"))
      (node (ref "J1-21") (pin "1") (pinfunction "1_1") (pintype "passive"))
    )
    (net (code "173") (name "/d31") (class "Default")
      (node (ref "J1-22") (pin "2") (pinfunction "2_2") (pintype "passive"))
      (node (ref "MCU1") (pin "35") (pinfunction "14_35") (pintype "passive"))
      (node (ref "TVS-3V3-4") (pin "12") (pinfunction "C_12") (pintype "passive"))
    )
    (net (code "174") (name "/d31_E") (class "Default")
      (node (ref "H3") (pin "3") (pinfunction "3_3") (pintype "passive"))
      (node (ref "H4") (pin "3") (pinfunction "3_3") (pintype "passive"))
      (node (ref "J1-22") (pin "1") (pinfunction "1_1") (pintype "passive"))
    )
    (net (code "175") (name "/d32") (class "Default")
      (node (ref "J1-23") (pin "2") (pinfunction "2_2") (pintype "passive"))
      (node (ref "MCU1") (pin "36") (pinfunction "15_36") (pintype "passive"))
      (node (ref "TVS-3V3-4") (pin "11") (pinfunction "C_11") (pintype "passive"))
    )
    (net (code "176") (name "/d32_E") (class "Default")
      (node (ref "H3") (pin "4") (pinfunction "4_4") (pintype "passive"))
      (node (ref "H4") (pin "4") (pinfunction "4_4") (pintype "passive"))
      (node (ref "J1-23") (pin "1") (pinfunction "1_1") (pintype "passive"))
    )
    (net (code "177") (name "/dir0") (class "Default")
      (node (ref "DIR_13=OUT") (pin "2") (pinfunction "2_2") (pintype "passive"))
      (node (ref "LVL_GPIO13") (pin "5") (pinfunction "DIR_5") (pintype "passive"))
      (node (ref "PWM2") (pin "6") (pinfunction "LED0_6") (pintype "passive"))
    )
    (net (code "178") (name "/dir1") (class "Default")
      (node (ref "DIR_25=OUT") (pin "2") (pinfunction "2_2") (pintype "passive"))
      (node (ref "LVL_GPIO25") (pin "5") (pinfunction "DIR_5") (pintype "passive"))
      (node (ref "PWM2") (pin "8") (pinfunction "LED2_8") (pintype "passive"))
    )
    (net (code "179") (name "/dir2") (class "Default")
      (node (ref "DIR_26=OUT") (pin "2") (pinfunction "2_2") (pintype "passive"))
      (node (ref "LVL_GPIO26") (pin "5") (pinfunction "DIR_5") (pintype "passive"))
      (node (ref "PWM2") (pin "10") (pinfunction "LED4_10") (pintype "passive"))
    )
    (net (code "180") (name "/dir3") (class "Default")
      (node (ref "DIR_27=OUT") (pin "2") (pinfunction "2_2") (pintype "passive"))
      (node (ref "LVL_GPIO27") (pin "5") (pinfunction "DIR_5") (pintype "passive"))
      (node (ref "PWM2") (pin "12") (pinfunction "LED6_12") (pintype "passive"))
    )
    (net (code "181") (name "/dir4") (class "Default")
      (node (ref "DIR_28=OUT") (pin "2") (pinfunction "2_2") (pintype "passive"))
      (node (ref "LVL_GPIO28") (pin "5") (pinfunction "DIR_5") (pintype "passive"))
      (node (ref "PWM2") (pin "15") (pinfunction "LED8_15") (pintype "passive"))
    )
    (net (code "182") (name "/dir5") (class "Default")
      (node (ref "DIR_31=OUT") (pin "2") (pinfunction "2_2") (pintype "passive"))
      (node (ref "LVL_GPIO31") (pin "5") (pinfunction "DIR_5") (pintype "passive"))
      (node (ref "PWM2") (pin "17") (pinfunction "LED10_17") (pintype "passive"))
    )
    (net (code "183") (name "/dir6") (class "Default")
      (node (ref "DIR_32=OUT") (pin "2") (pinfunction "2_2") (pintype "passive"))
      (node (ref "LVL_GPIO32") (pin "5") (pinfunction "DIR_5") (pintype "passive"))
      (node (ref "PWM2") (pin "19") (pinfunction "LED12_19") (pintype "passive"))
    )
    (net (code "184") (name "/en0") (class "Default")
      (node (ref "LVL_GPIO13") (pin "1") (pinfunction "VCCA_1") (pintype "passive"))
      (node (ref "PWM2") (pin "7") (pinfunction "LED1_7") (pintype "passive"))
    )
    (net (code "185") (name "/en1") (class "Default")
      (node (ref "LVL_GPIO25") (pin "1") (pinfunction "VCCA_1") (pintype "passive"))
      (node (ref "PWM2") (pin "9") (pinfunction "LED3_9") (pintype "passive"))
    )
    (net (code "186") (name "/en2") (class "Default")
      (node (ref "LVL_GPIO26") (pin "1") (pinfunction "VCCA_1") (pintype "passive"))
      (node (ref "PWM2") (pin "11") (pinfunction "LED5_11") (pintype "passive"))
    )
    (net (code "187") (name "/en3") (class "Default")
      (node (ref "LVL_GPIO27") (pin "1") (pinfunction "VCCA_1") (pintype "passive"))
      (node (ref "PWM2") (pin "13") (pinfunction "LED7_13") (pintype "passive"))
    )
    (net (code "188") (name "/en4") (class "Default")
      (node (ref "LVL_GPIO28") (pin "1") (pinfunction "VCCA_1") (pintype "passive"))
      (node (ref "PWM2") (pin "16") (pinfunction "LED9_16") (pintype "passive"))
    )
    (net (code "189") (name "/en5") (class "Default")
      (node (ref "LVL_GPIO31") (pin "1") (pinfunction "VCCA_1") (pintype "passive"))
      (node (ref "PWM2") (pin "18") (pinfunction "LED11_18") (pintype "passive"))
    )
    (net (code "190") (name "/en6") (class "Default")
      (node (ref "LVL_GPIO32") (pin "1") (pinfunction "VCCA_1") (pintype "passive"))
      (node (ref "PWM2") (pin "20") (pinfunction "LED13_20") (pintype "passive"))
    )
    (net (code "191") (name "3V3") (class "Default")
      (node (ref "ADC") (pin "16") (pinfunction "VDD_16") (pintype "passive"))
      (node (ref "C1-11") (pin "2") (pinfunction "2_2") (pintype "passive"))
      (node (ref "C1-2") (pin "2") (pinfunction "2_2") (pintype "passive"))
      (node (ref "C1-4") (pin "2") (pinfunction "2_2") (pintype "passive"))
      (node (ref "C1-8") (pin "2") (pinfunction "2_2") (pintype "passive"))
      (node (ref "C2-1") (pin "2") (pinfunction "2_2") (pintype "passive"))
      (node (ref "C4-11") (pin "2") (pinfunction "2_2") (pintype "passive"))
      (node (ref "C4-12") (pin "2") (pinfunction "2_2") (pintype "passive"))
      (node (ref "DAC-1") (pin "3") (pinfunction "VDD_3") (pintype "passive"))
      (node (ref "DL-1") (pin "3") (pinfunction "D_3") (pintype "passive"))
      (node (ref "DL-1") (pin "5") (pinfunction "Vcc_5") (pintype "passive"))
      (node (ref "H1") (pin "19") (pinfunction "19_19") (pintype "passive"))
      (node (ref "H2") (pin "12") (pinfunction "12_12") (pintype "passive"))
      (node (ref "H3") (pin "6") (pinfunction "6_6") (pintype "passive"))
      (node (ref "H4") (pin "6") (pinfunction "6_6") (pintype "passive"))
      (node (ref "J1-10") (pin "1") (pinfunction "1_1") (pintype "passive"))
      (node (ref "J1-11") (pin "1") (pinfunction "1_1") (pintype "passive"))
      (node (ref "J1-2") (pin "1") (pinfunction "1_1") (pintype "passive"))
      (node (ref "J1-24") (pin "3") (pinfunction "3_3") (pintype "passive"))
      (node (ref "J1-3") (pin "1") (pinfunction "1_1") (pintype "passive"))
      (node (ref "J1-4") (pin "1") (pinfunction "1_1") (pintype "passive"))
      (node (ref "J1-5") (pin "1") (pinfunction "1_1") (pintype "passive"))
      (node (ref "J1-6") (pin "1") (pinfunction "1_1") (pintype "passive"))
      (node (ref "J1-7") (pin "1") (pinfunction "1_1") (pintype "passive"))
      (node (ref "J1-8") (pin "1") (pinfunction "1_1") (pintype "passive"))
      (node (ref "J1-9") (pin "1") (pinfunction "1_1") (pintype "passive"))
      (node (ref "LED1-11") (pin "2") (pinfunction "2_2") (pintype "passive"))
      (node (ref "N1") (pin "5") (pinfunction "VCC_5") (pintype "passive"))
      (node (ref "N2") (pin "5") (pinfunction "VCC_5") (pintype "passive"))
      (node (ref "PWM1") (pin "28") (pinfunction "VDD_28") (pintype "passive"))
      (node (ref "PWM2") (pin "24") (pinfunction "A5_24") (pintype "passive"))
      (node (ref "PWM2") (pin "28") (pinfunction "VDD_28") (pintype "passive"))
      (node (ref "R1-11") (pin "1") (pinfunction "1_1") (pintype "passive"))
      (node (ref "R1-13") (pin "1") (pinfunction "1_1") (pintype "passive"))
      (node (ref "R1-2") (pin "1") (pinfunction "1_1") (pintype "passive"))
      (node (ref "R1-30") (pin "1") (pinfunction "1_1") (pintype "passive"))
      (node (ref "R1-35") (pin "2") (pinfunction "2_2") (pintype "passive"))
      (node (ref "R1-36") (pin "2") (pinfunction "2_2") (pintype "passive"))
      (node (ref "R1-37") (pin "2") (pinfunction "2_2") (pintype "passive"))
      (node (ref "R1-38") (pin "2") (pinfunction "2_2") (pintype "passive"))
      (node (ref "R1-39") (pin "2") (pinfunction "2_2") (pintype "passive"))
      (node (ref "R1-5") (pin "1") (pinfunction "1_1") (pintype "passive"))
      (node (ref "R1-6") (pin "1") (pinfunction "1_1") (pintype "passive"))
      (node (ref "R1-9") (pin "1") (pinfunction "1_1") (pintype "passive"))
      (node (ref "R4-4") (pin "1") (pinfunction "1_1") (pintype "passive"))
      (node (ref "R4-5") (pin "1") (pinfunction "1_1") (pintype "passive"))
      (node (ref "R4-5B") (pin "1") (pinfunction "1_1") (pintype "passive"))
      (node (ref "ShiftLED2") (pin "1") (pinfunction "VCCA_1") (pintype "passive"))
      (node (ref "ShiftLED2") (pin "5") (pinfunction "DIR_5") (pintype "passive"))
      (node (ref "VReg2") (pin "2") (pinfunction "VOUT_2") (pintype "passive"))
      (node (ref "WD1") (pin "5") (pinfunction "VCC_5") (pintype "passive"))
    )
    (net (code "192") (name "3V3Ref") (class "Default")
      (node (ref "R3-3") (pin "2") (pinfunction "2_2") (pintype "passive"))
      (node (ref "R5-9") (pin "1") (pinfunction "1_1") (pintype "passive"))
      (node (ref "Ref1") (pin "6") (pinfunction "Vout_6") (pintype "passive"))
    )
    (net (code "193") (name "3V3S") (class "Default")
      (node (ref "C1-12") (pin "2") (pinfunction "2_2") (pintype "passive"))
      (node (ref "C1-14") (pin "2") (pinfunction "2_2") (pintype "passive"))
      (node (ref "C1-16") (pin "2") (pinfunction "2_2") (pintype "passive"))
      (node (ref "C7-1") (pin "1") (pinfunction "1_1") (pintype "passive"))
      (node (ref "LED1-8") (pin "2") (pinfunction "2_2") (pintype "passive"))
      (node (ref "LvL-1") (pin "1") (pinfunction "VCCA_1") (pintype "passive"))
      (node (ref "LvL-2") (pin "1") (pinfunction "VCCA_1") (pintype "passive"))
      (node (ref "LvL-3") (pin "1") (pinfunction "VCCA_1") (pintype "passive"))
      (node (ref "N2") (pin "2") (pinfunction "IN_2") (pintype "passive"))
      (node (ref "NOT_OK") (pin "2") (pinfunction "2_2") (pintype "passive"))
      (node (ref "R1-31") (pin "1") (pinfunction "1_1") (pintype "passive"))
      (node (ref "VReg3") (pin "5") (pinfunction "Out_5") (pintype "passive"))
    )
    (net (code "194") (name "5V") (class "Default")
      (node (ref "C1-13") (pin "1") (pinfunction "1_1") (pintype "passive"))
      (node (ref "C1-15") (pin "1") (pinfunction "1_1") (pintype "passive"))
      (node (ref "C1-17") (pin "1") (pinfunction "1_1") (pintype "passive"))
      (node (ref "C1-9") (pin "2") (pinfunction "2_2") (pintype "passive"))
      (node (ref "C4-4") (pin "2") (pinfunction "2_2") (pintype "passive"))
      (node (ref "C4-5") (pin "2") (pinfunction "2_2") (pintype "passive"))
      (node (ref "C6-1") (pin "1") (pinfunction "1_1") (pintype "passive"))
      (node (ref "H1") (pin "14") (pinfunction "14_14") (pintype "passive"))
      (node (ref "J1-10") (pin "3") (pinfunction "3_3") (pintype "passive"))
      (node (ref "J1-11") (pin "3") (pinfunction "3_3") (pintype "passive"))
      (node (ref "J1-5") (pin "3") (pinfunction "3_3") (pintype "passive"))
      (node (ref "J1-6") (pin "3") (pinfunction "3_3") (pintype "passive"))
      (node (ref "J1-7") (pin "3") (pinfunction "3_3") (pintype "passive"))
      (node (ref "J1-8") (pin "3") (pinfunction "3_3") (pintype "passive"))
      (node (ref "J1-9") (pin "3") (pinfunction "3_3") (pintype "passive"))
      (node (ref "LED1-10") (pin "2") (pinfunction "2_2") (pintype "passive"))
      (node (ref "LvL-1") (pin "23") (pinfunction "VCCB_23") (pintype "passive"))
      (node (ref "LvL-1") (pin "24") (pinfunction "VCCB_24") (pintype "passive"))
      (node (ref "LvL-2") (pin "23") (pinfunction "VCCB_23") (pintype "passive"))
      (node (ref "LvL-2") (pin "24") (pinfunction "VCCB_24") (pintype "passive"))
      (node (ref "LvL-3") (pin "23") (pinfunction "VCCB_23") (pintype "passive"))
      (node (ref "LvL-3") (pin "24") (pinfunction "VCCB_24") (pintype "passive"))
      (node (ref "R4-3") (pin "1") (pinfunction "1_1") (pintype "passive"))
      (node (ref "Ref1") (pin "2") (pinfunction "Vin_2") (pintype "passive"))
      (node (ref "VReg1") (pin "2") (pinfunction "VOUT_2") (pintype "passive"))
      (node (ref "VReg3") (pin "1") (pinfunction "In_1") (pintype "passive"))
    )
    (net (code "195") (name "5VB") (class "Default")
      (node (ref "C7-2") (pin "1") (pinfunction "1_1") (pintype "passive"))
      (node (ref "Cnt1") (pin "16") (pinfunction "VCC_16") (pintype "passive"))
      (node (ref "Cnt2") (pin "16") (pinfunction "VCC_16") (pintype "passive"))
      (node (ref "Cnt3") (pin "16") (pinfunction "VCC_16") (pintype "passive"))
      (node (ref "J1-24") (pin "1") (pinfunction "1_1") (pintype "passive"))
      (node (ref "J6") (pin "2") (pinfunction "2_2") (pintype "passive"))
      (node (ref "R1-33") (pin "2") (pinfunction "2_2") (pintype "passive"))
      (node (ref "ShiftLED1") (pin "6") (pinfunction "VCCB_6") (pintype "passive"))
      (node (ref "ShiftLED2") (pin "6") (pinfunction "VCCB_6") (pintype "passive"))
      (node (ref "VReg5_2") (pin "5") (pinfunction "Out_5") (pintype "passive"))
    )
    (net (code "196") (name "6V5") (class "Default")
      (node (ref "C3-4") (pin "1") (pinfunction "1_1") (pintype "passive"))
      (node (ref "C4-10") (pin "1") (pinfunction "1_1") (pintype "passive"))
      (node (ref "C4-3") (pin "1") (pinfunction "1_1") (pintype "passive"))
      (node (ref "C6-2") (pin "1") (pinfunction "1_1") (pintype "passive"))
      (node (ref "F0") (pin "2") (pinfunction "2_2") (pintype "passive"))
      (node (ref "LED1-9") (pin "2") (pinfunction "2_2") (pintype "passive"))
      (node (ref "R2-1") (pin "2") (pinfunction "2_2") (pintype "passive"))
      (node (ref "VReg1") (pin "7") (pinfunction "EN_7") (pintype "passive"))
      (node (ref "VReg1") (pin "8") (pinfunction "VIN_8") (pintype "passive"))
      (node (ref "VReg2") (pin "7") (pinfunction "EN_7") (pintype "passive"))
      (node (ref "VReg2") (pin "8") (pinfunction "VIN_8") (pintype "passive"))
      (node (ref "VReg5_2") (pin "1") (pinfunction "In_1") (pintype "passive"))
      (node (ref "VReg5_2") (pin "3") (pinfunction "EN_3") (pintype "passive"))
    )
    (net (code "197") (name "DAC_1") (class "Default")
      (node (ref "DAC-1") (pin "4") (pinfunction "VA_4") (pintype "passive"))
      (node (ref "J1-16") (pin "2") (pinfunction "2_2") (pintype "passive"))
      (node (ref "TVS-3V3-3") (pin "16") (pinfunction "C_16") (pintype "passive"))
    )
    (net (code "198") (name "DAC_2") (class "Default")
      (node (ref "DAC-1") (pin "13") (pinfunction "VB_13") (pintype "passive"))
      (node (ref "J1-17") (pin "2") (pinfunction "2_2") (pintype "passive"))
      (node (ref "TVS-3V3-3") (pin "9") (pinfunction "C_9") (pintype "passive"))
    )
    (net (code "199") (name "DAC_3") (class "Default")
      (node (ref "DAC-1") (pin "5") (pinfunction "VC_5") (pintype "passive"))
      (node (ref "J1-18") (pin "2") (pinfunction "2_2") (pintype "passive"))
      (node (ref "TVS-3V3-3") (pin "15") (pinfunction "C_15") (pintype "passive"))
    )
    (net (code "200") (name "DAC_4") (class "Default")
      (node (ref "DAC-1") (pin "12") (pinfunction "VD_12") (pintype "passive"))
      (node (ref "J1-19") (pin "2") (pinfunction "2_2") (pintype "passive"))
      (node (ref "TVS-3V3-3") (pin "10") (pinfunction "C_10") (pintype "passive"))
    )
    (net (code "201") (name "DAC_5") (class "Default")
      (node (ref "DAC-1") (pin "6") (pinfunction "VE_6") (pintype "passive"))
      (node (ref "DAC5") (pin "1") (pinfunction "Centre_1") (pintype "passive"))
      (node (ref "TVS-3V3-3") (pin "14") (pinfunction "C_14") (pintype "passive"))
    )
    (net (code "202") (name "DAC_6") (class "Default")
      (node (ref "DAC-1") (pin "11") (pinfunction "VF_11") (pintype "passive"))
      (node (ref "DAC6") (pin "1") (pinfunction "Centre_1") (pintype "passive"))
      (node (ref "TVS-3V3-3") (pin "11") (pinfunction "C_11") (pintype "passive"))
    )
    (net (code "203") (name "DAC_7") (class "Default")
      (node (ref "DAC-1") (pin "7") (pinfunction "VG_7") (pintype "passive"))
      (node (ref "DAC7") (pin "1") (pinfunction "Centre_1") (pintype "passive"))
      (node (ref "TVS-3V3-3") (pin "13") (pinfunction "C_13") (pintype "passive"))
    )
    (net (code "204") (name "DAC_8") (class "Default")
      (node (ref "DAC-1") (pin "10") (pinfunction "VH_10") (pintype "passive"))
      (node (ref "DAC8") (pin "1") (pinfunction "Centre_1") (pintype "passive"))
      (node (ref "TVS-3V3-3") (pin "12") (pinfunction "C_12") (pintype "passive"))
    )
    (net (code "205") (name "GND") (class "Default")
      (node (ref "ADC") (pin "11") (pinfunction "COM_11") (pintype "passive"))
      (node (ref "ADC") (pin "12") (pinfunction "A0_12") (pintype "passive"))
      (node (ref "ADC") (pin "13") (pinfunction "A1_13") (pintype "passive"))
      (node (ref "ADC") (pin "9") (pinfunction "GND_9") (pintype "passive"))
      (node (ref "ADC1") (pin "2") (pinfunction "GND_2") (pintype "passive"))
      (node (ref "ADC2") (pin "2") (pinfunction "GND_2") (pintype "passive"))
      (node (ref "ADC3") (pin "2") (pinfunction "GND_2") (pintype "passive"))
      (node (ref "ADC4") (pin "2") (pinfunction "GND_2") (pintype "passive"))
      (node (ref "ADC5") (pin "2") (pinfunction "GND_2") (pintype "passive"))
      (node (ref "ADC6") (pin "2") (pinfunction "GND_2") (pintype "passive"))
      (node (ref "ADC7") (pin "2") (pinfunction "GND_2") (pintype "passive"))
      (node (ref "ADC8") (pin "2") (pinfunction "GND_2") (pintype "passive"))
      (node (ref "C1-10") (pin "2") (pinfunction "2_2") (pintype "passive"))
      (node (ref "C1-11") (pin "1") (pinfunction "1_1") (pintype "passive"))
      (node (ref "C1-12") (pin "1") (pinfunction "1_1") (pintype "passive"))
      (node (ref "C1-13") (pin "2") (pinfunction "2_2") (pintype "passive"))
      (node (ref "C1-14") (pin "1") (pinfunction "1_1") (pintype "passive"))
      (node (ref "C1-15") (pin "2") (pinfunction "2_2") (pintype "passive"))
      (node (ref "C1-16") (pin "1") (pinfunction "1_1") (pintype "passive"))
      (node (ref "C1-17") (pin "2") (pinfunction "2_2") (pintype "passive"))
      (node (ref "C1-18") (pin "1") (pinfunction "1_1") (pintype "passive"))
      (node (ref "C1-19") (pin "1") (pinfunction "1_1") (pintype "passive"))
      (node (ref "C1-2") (pin "1") (pinfunction "1_1") (pintype "passive"))
      (node (ref "C1-20") (pin "1") (pinfunction "1_1") (pintype "passive"))
      (node (ref "C1-21") (pin "1") (pinfunction "1_1") (pintype "passive"))
      (node (ref "C1-22") (pin "1") (pinfunction "1_1") (pintype "passive"))
      (node (ref "C1-23") (pin "1") (pinfunction "1_1") (pintype "passive"))
      (node (ref "C1-24") (pin "1") (pinfunction "1_1") (pintype "passive"))
      (node (ref "C1-25") (pin "2") (pinfunction "2_2") (pintype "passive"))
      (node (ref "C1-26") (pin "2") (pinfunction "2_2") (pintype "passive"))
      (node (ref "C1-3") (pin "1") (pinfunction "1_1") (pintype "passive"))
      (node (ref "C1-4") (pin "1") (pinfunction "1_1") (pintype "passive"))
      (node (ref "C1-8") (pin "1") (pinfunction "1_1") (pintype "passive"))
      (node (ref "C1-9") (pin "1") (pinfunction "1_1") (pintype "passive"))
      (node (ref "C2-1") (pin "1") (pinfunction "1_1") (pintype "passive"))
      (node (ref "C2-2") (pin "2") (pinfunction "2_2") (pintype "passive"))
      (node (ref "C3-1") (pin "2") (pinfunction "2_2") (pintype "passive"))
      (node (ref "C3-2") (pin "2") (pinfunction "2_2") (pintype "passive"))
      (node (ref "C3-2B") (pin "2") (pinfunction "2_2") (pintype "passive"))
      (node (ref "C3-3") (pin "2") (pinfunction "2_2") (pintype "passive"))
      (node (ref "C3-4") (pin "2") (pinfunction "2_2") (pintype "passive"))
      (node (ref "C4-1") (pin "2") (pinfunction "2_2") (pintype "passive"))
      (node (ref "C4-10") (pin "2") (pinfunction "2_2") (pintype "passive"))
      (node (ref "C4-11") (pin "1") (pinfunction "1_1") (pintype "passive"))
      (node (ref "C4-12") (pin "1") (pinfunction "1_1") (pintype "passive"))
      (node (ref "C4-13") (pin "1") (pinfunction "1_1") (pintype "passive"))
      (node (ref "C4-14") (pin "1") (pinfunction "1_1") (pintype "passive"))
      (node (ref "C4-2") (pin "2") (pinfunction "2_2") (pintype "passive"))
      (node (ref "C4-3") (pin "2") (pinfunction "2_2") (pintype "passive"))
      (node (ref "C4-4") (pin "1") (pinfunction "1_1") (pintype "passive"))
      (node (ref "C4-5") (pin "1") (pinfunction "1_1") (pintype "passive"))
      (node (ref "C4-6") (pin "1") (pinfunction "1_1") (pintype "passive"))
      (node (ref "C4-7") (pin "1") (pinfunction "1_1") (pintype "passive"))
      (node (ref "C4-8") (pin "2") (pinfunction "2_2") (pintype "passive"))
      (node (ref "C4-9") (pin "2") (pinfunction "2_2") (pintype "passive"))
      (node (ref "C5-1") (pin "1") (pinfunction "1_1") (pintype "passive"))
      (node (ref "C5-2") (pin "1") (pinfunction "1_1") (pintype "passive"))
      (node (ref "C5-3") (pin "1") (pinfunction "1_1") (pintype "passive"))
      (node (ref "C5-4") (pin "1") (pinfunction "1_1") (pintype "passive"))
      (node (ref "C5-5") (pin "1") (pinfunction "1_1") (pintype "passive"))
      (node (ref "C5-6") (pin "1") (pinfunction "1_1") (pintype "passive"))
      (node (ref "C5-7") (pin "1") (pinfunction "1_1") (pintype "passive"))
      (node (ref "C5-8") (pin "1") (pinfunction "1_1") (pintype "passive"))
      (node (ref "C6-1") (pin "2") (pinfunction "2_2") (pintype "passive"))
      (node (ref "C6-2") (pin "2") (pinfunction "2_2") (pintype "passive"))
      (node (ref "C7-1") (pin "2") (pinfunction "2_2") (pintype "passive"))
      (node (ref "C7-2") (pin "2") (pinfunction "2_2") (pintype "passive"))
      (node (ref "C8-1") (pin "1") (pinfunction "1_1") (pintype "passive"))
      (node (ref "C8-2") (pin "1") (pinfunction "1_1") (pintype "passive"))
      (node (ref "C9-1") (pin "1") (pinfunction "1_1") (pintype "passive"))
      (node (ref "CE-1") (pin "2") (pinfunction "2_2") (pintype "passive"))
      (node (ref "CE-1B") (pin "2") (pinfunction "2_2") (pintype "passive"))
      (node (ref "Cnt1") (pin "8") (pinfunction "GND_8") (pintype "passive"))
      (node (ref "Cnt2") (pin "8") (pinfunction "GND_8") (pintype "passive"))
      (node (ref "Cnt3") (pin "8") (pinfunction "GND_8") (pintype "passive"))
      (node (ref "DAC-1") (pin "14") (pinfunction "GND_14") (pintype "passive"))
      (node (ref "DAC1") (pin "2") (pinfunction "GND_2") (pintype "passive"))
      (node (ref "DAC2") (pin "2") (pinfunction "GND_2") (pintype "passive"))
      (node (ref "DAC3") (pin "2") (pinfunction "GND_2") (pintype "passive"))
      (node (ref "DAC4") (pin "2") (pinfunction "GND_2") (pintype "passive"))
      (node (ref "DAC5") (pin "2") (pinfunction "GND_2") (pintype "passive"))
      (node (ref "DAC6") (pin "2") (pinfunction "GND_2") (pintype "passive"))
      (node (ref "DAC7") (pin "2") (pinfunction "GND_2") (pintype "passive"))
      (node (ref "DAC8") (pin "2") (pinfunction "GND_2") (pintype "passive"))
      (node (ref "DL-1") (pin "2") (pinfunction "GND_2") (pintype "passive"))
      (node (ref "GPIO13") (pin "2") (pinfunction "GND_2") (pintype "passive"))
      (node (ref "GPIO25") (pin "2") (pinfunction "GND_2") (pintype "passive"))
      (node (ref "GPIO26") (pin "2") (pinfunction "GND_2") (pintype "passive"))
      (node (ref "GPIO27") (pin "2") (pinfunction "GND_2") (pintype "passive"))
      (node (ref "GPIO28") (pin "2") (pinfunction "GND_2") (pintype "passive"))
      (node (ref "GPIO29") (pin "2") (pinfunction "GND_2") (pintype "passive"))
      (node (ref "GPIO30") (pin "2") (pinfunction "GND_2") (pintype "passive"))
      (node (ref "GPIO31") (pin "2") (pinfunction "GND_2") (pintype "passive"))
      (node (ref "GPIO32") (pin "2") (pinfunction "GND_2") (pintype "passive"))
      (node (ref "H1") (pin "10") (pinfunction "10_10") (pintype "passive"))
      (node (ref "H1") (pin "11") (pinfunction "11_11") (pintype "passive"))
      (node (ref "H2") (pin "1") (pinfunction "1_1") (pintype "passive"))
      (node (ref "H2") (pin "10") (pinfunction "10_10") (pintype "passive"))
      (node (ref "H2") (pin "16") (pinfunction "16_16") (pintype "passive"))
      (node (ref "H2") (pin "2") (pinfunction "2_2") (pintype "passive"))
      (node (ref "H2") (pin "3") (pinfunction "3_3") (pintype "passive"))
      (node (ref "H2") (pin "4") (pinfunction "4_4") (pintype "passive"))
      (node (ref "H2") (pin "5") (pinfunction "5_5") (pintype "passive"))
      (node (ref "H2") (pin "6") (pinfunction "6_6") (pintype "passive"))
      (node (ref "H2") (pin "7") (pinfunction "7_7") (pintype "passive"))
      (node (ref "H2") (pin "8") (pinfunction "8_8") (pintype "passive"))
      (node (ref "H2") (pin "9") (pinfunction "9_9") (pintype "passive"))
      (node (ref "H3") (pin "12") (pinfunction "12_12") (pintype "passive"))
      (node (ref "H3") (pin "15") (pinfunction "15_15") (pintype "passive"))
      (node (ref "H3") (pin "16") (pinfunction "16_16") (pintype "passive"))
      (node (ref "H4") (pin "12") (pinfunction "12_12") (pintype "passive"))
      (node (ref "H4") (pin "15") (pinfunction "15_15") (pintype "passive"))
      (node (ref "H4") (pin "16") (pinfunction "16_16") (pintype "passive"))
      (node (ref "IN(5V)-1") (pin "2") (pinfunction "GND_2") (pintype "passive"))
      (node (ref "IN(5V)-2") (pin "2") (pinfunction "GND_2") (pintype "passive"))
      (node (ref "IN(5V)-3") (pin "2") (pinfunction "GND_2") (pintype "passive"))
      (node (ref "IN(5V)-4") (pin "2") (pinfunction "GND_2") (pintype "passive"))
      (node (ref "J1-2") (pin "3") (pinfunction "3_3") (pintype "passive"))
      (node (ref "J1-3") (pin "3") (pinfunction "3_3") (pintype "passive"))
      (node (ref "J1-4") (pin "3") (pinfunction "3_3") (pintype "passive"))
      (node (ref "Jack1") (pin "2") (pinfunction "Gnd_2") (pintype "passive"))
      (node (ref "Jack1") (pin "3") (pinfunction "Gnd_3") (pintype "passive"))
      (node (ref "LA0") (pin "2") (pinfunction "V-_2") (pintype "passive"))
      (node (ref "LA1") (pin "2") (pinfunction "V-_2") (pintype "passive"))
      (node (ref "LA2") (pin "2") (pinfunction "V-_2") (pintype "passive"))
      (node (ref "LA3") (pin "2") (pinfunction "V-_2") (pintype "passive"))
      (node (ref "LA4") (pin "2") (pinfunction "V-_2") (pintype "passive"))
      (node (ref "LA5") (pin "2") (pinfunction "V-_2") (pintype "passive"))
      (node (ref "LA6") (pin "2") (pinfunction "V-_2") (pintype "passive"))
      (node (ref "LA7") (pin "2") (pinfunction "V-_2") (pintype "passive"))
      (node (ref "LA8") (pin "2") (pinfunction "V-_2") (pintype "passive"))
      (node (ref "LA9") (pin "2") (pinfunction "V-_2") (pintype "passive"))
      (node (ref "LB0") (pin "2") (pinfunction "V-_2") (pintype "passive"))
      (node (ref "LB1") (pin "2") (pinfunction "V-_2") (pintype "passive"))
      (node (ref "LB2") (pin "2") (pinfunction "V-_2") (pintype "passive"))
      (node (ref "LB3") (pin "2") (pinfunction "V-_2") (pintype "passive"))
      (node (ref "LB4") (pin "2") (pinfunction "V-_2") (pintype "passive"))
      (node (ref "LB5") (pin "2") (pinfunction "V-_2") (pintype "passive"))
      (node (ref "LB6") (pin "2") (pinfunction "V-_2") (pintype "passive"))
      (node (ref "LB7") (pin "2") (pinfunction "V-_2") (pintype "passive"))
      (node (ref "LB8") (pin "2") (pinfunction "V-_2") (pintype "passive"))
      (node (ref "LB9") (pin "2") (pinfunction "V-_2") (pintype "passive"))
      (node (ref "LC0") (pin "2") (pinfunction "V-_2") (pintype "passive"))
      (node (ref "LC1") (pin "2") (pinfunction "V-_2") (pintype "passive"))
      (node (ref "LC2") (pin "2") (pinfunction "V-_2") (pintype "passive"))
      (node (ref "LC3") (pin "2") (pinfunction "V-_2") (pintype "passive"))
      (node (ref "LC4") (pin "2") (pinfunction "V-_2") (pintype "passive"))
      (node (ref "LC5") (pin "2") (pinfunction "V-_2") (pintype "passive"))
      (node (ref "LC6") (pin "2") (pinfunction "V-_2") (pintype "passive"))
      (node (ref "LC7") (pin "2") (pinfunction "V-_2") (pintype "passive"))
      (node (ref "LC8") (pin "2") (pinfunction "V-_2") (pintype "passive"))
      (node (ref "LC9") (pin "2") (pinfunction "V-_2") (pintype "passive"))
      (node (ref "LVL_GPIO13") (pin "2") (pinfunction "GND_2") (pintype "passive"))
      (node (ref "LVL_GPIO25") (pin "2") (pinfunction "GND_2") (pintype "passive"))
      (node (ref "LVL_GPIO26") (pin "2") (pinfunction "GND_2") (pintype "passive"))
      (node (ref "LVL_GPIO27") (pin "2") (pinfunction "GND_2") (pintype "passive"))
      (node (ref "LVL_GPIO28") (pin "2") (pinfunction "GND_2") (pintype "passive"))
      (node (ref "LVL_GPIO31") (pin "2") (pinfunction "GND_2") (pintype "passive"))
      (node (ref "LVL_GPIO32") (pin "2") (pinfunction "GND_2") (pintype "passive"))
      (node (ref "LvL-1") (pin "11") (pinfunction "GND_11") (pintype "passive"))
      (node (ref "LvL-1") (pin "12") (pinfunction "GND_12") (pintype "passive"))
      (node (ref "LvL-1") (pin "13") (pinfunction "GND_13") (pintype "passive"))
      (node (ref "LvL-2") (pin "11") (pinfunction "GND_11") (pintype "passive"))
      (node (ref "LvL-2") (pin "12") (pinfunction "GND_12") (pintype "passive"))
      (node (ref "LvL-2") (pin "13") (pinfunction "GND_13") (pintype "passive"))
      (node (ref "LvL-3") (pin "11") (pinfunction "GND_11") (pintype "passive"))
      (node (ref "LvL-3") (pin "12") (pinfunction "GND_12") (pintype "passive"))
      (node (ref "LvL-3") (pin "13") (pinfunction "GND_13") (pintype "passive"))
      (node (ref "MCU1") (pin "0") (pinfunction "GND_0") (pintype "passive"))
      (node (ref "MCU1") (pin "33") (pinfunction "GND_33") (pintype "passive"))
      (node (ref "MCU1") (pin "46") (pinfunction "GND_46") (pintype "passive"))
      (node (ref "N1") (pin "3") (pinfunction "GND_3") (pintype "passive"))
      (node (ref "N2") (pin "3") (pinfunction "GND_3") (pintype "passive"))
      (node (ref "OUT(5V)-1") (pin "2") (pinfunction "GND_2") (pintype "passive"))
      (node (ref "OUT(5V)-2") (pin "2") (pinfunction "GND_2") (pintype "passive"))
      (node (ref "OUT(5V)-3") (pin "2") (pinfunction "GND_2") (pintype "passive"))
      (node (ref "OUT(5V)-4") (pin "2") (pinfunction "GND_2") (pintype "passive"))
      (node (ref "PS1") (pin "2") (pinfunction "GND_2") (pintype "passive"))
      (node (ref "PWM1") (pin "1") (pinfunction "A0_1") (pintype "passive"))
      (node (ref "PWM1") (pin "14") (pinfunction "VSS_14") (pintype "passive"))
      (node (ref "PWM1") (pin "2") (pinfunction "A1_2") (pintype "passive"))
      (node (ref "PWM1") (pin "24") (pinfunction "A5_24") (pintype "passive"))
      (node (ref "PWM1") (pin "25") (pinfunction "EXTCLK_25") (pintype "passive"))
      (node (ref "PWM1") (pin "3") (pinfunction "A2_3") (pintype "passive"))
      (node (ref "PWM1") (pin "4") (pinfunction "A3_4") (pintype "passive"))
      (node (ref "PWM1") (pin "5") (pinfunction "A4_5") (pintype "passive"))
      (node (ref "PWM2") (pin "1") (pinfunction "A0_1") (pintype "passive"))
      (node (ref "PWM2") (pin "14") (pinfunction "VSS_14") (pintype "passive"))
      (node (ref "PWM2") (pin "2") (pinfunction "A1_2") (pintype "passive"))
      (node (ref "PWM2") (pin "25") (pinfunction "EXTCLK_25") (pintype "passive"))
      (node (ref "PWM2") (pin "3") (pinfunction "A2_3") (pintype "passive"))
      (node (ref "PWM2") (pin "4") (pinfunction "A3_4") (pintype "passive"))
      (node (ref "PWM2") (pin "5") (pinfunction "A4_5") (pintype "passive"))
      (node (ref "R1-1") (pin "2") (pinfunction "2_2") (pintype "passive"))
      (node (ref "R1-31") (pin "2") (pinfunction "2_2") (pintype "passive"))
      (node (ref "R1-32") (pin "2") (pinfunction "2_2") (pintype "passive"))
      (node (ref "R1-7") (pin "1") (pinfunction "1_1") (pintype "passive"))
      (node (ref "R2-1") (pin "1") (pinfunction "1_1") (pintype "passive"))
      (node (ref "R3-4") (pin "1") (pinfunction "1_1") (pintype "passive"))
      (node (ref "R3-5") (pin "1") (pinfunction "1_1") (pintype "passive"))
      (node (ref "R6-1") (pin "2") (pinfunction "2_2") (pintype "passive"))
      (node (ref "R6-10") (pin "2") (pinfunction "2_2") (pintype "passive"))
      (node (ref "R6-11") (pin "2") (pinfunction "2_2") (pintype "passive"))
      (node (ref "R6-12") (pin "2") (pinfunction "2_2") (pintype "passive"))
      (node (ref "R6-13") (pin "2") (pinfunction "2_2") (pintype "passive"))
      (node (ref "R6-14") (pin "2") (pinfunction "2_2") (pintype "passive"))
      (node (ref "R6-1B") (pin "2") (pinfunction "2_2") (pintype "passive"))
      (node (ref "R6-2") (pin "2") (pinfunction "2_2") (pintype "passive"))
      (node (ref "R6-2B") (pin "2") (pinfunction "2_2") (pintype "passive"))
      (node (ref "R6-3") (pin "2") (pinfunction "2_2") (pintype "passive"))
      (node (ref "R6-4") (pin "2") (pinfunction "2_2") (pintype "passive"))
      (node (ref "R6-5") (pin "2") (pinfunction "2_2") (pintype "passive"))
      (node (ref "R6-6") (pin "2") (pinfunction "2_2") (pintype "passive"))
      (node (ref "R6-7") (pin "2") (pinfunction "2_2") (pintype "passive"))
      (node (ref "R6-8") (pin "2") (pinfunction "2_2") (pintype "passive"))
      (node (ref "R6-9") (pin "2") (pinfunction "2_2") (pintype "passive"))
      (node (ref "R7-1") (pin "2") (pinfunction "2_2") (pintype "passive"))
      (node (ref "R7-2") (pin "2") (pinfunction "2_2") (pintype "passive"))
      (node (ref "R7-3") (pin "2") (pinfunction "2_2") (pintype "passive"))
      (node (ref "R7-4") (pin "2") (pinfunction "2_2") (pintype "passive"))
      (node (ref "R7-5") (pin "2") (pinfunction "2_2") (pintype "passive"))
      (node (ref "R7-6") (pin "2") (pinfunction "2_2") (pintype "passive"))
      (node (ref "R7-7") (pin "2") (pinfunction "2_2") (pintype "passive"))
      (node (ref "R7-8") (pin "2") (pinfunction "2_2") (pintype "passive"))
      (node (ref "Ref1") (pin "4") (pinfunction "GND_4") (pintype "passive"))
      (node (ref "S1") (pin "1") (pinfunction "PGND_1") (pintype "passive"))
      (node (ref "S1") (pin "19") (pinfunction "PGND_19") (pintype "passive"))
      (node (ref "S1") (pin "2") (pinfunction "PGND_2") (pintype "passive"))
      (node (ref "S1") (pin "20") (pinfunction "PGND_20") (pintype "passive"))
      (node (ref "S1") (pin "21") (pinfunction "SGND_21") (pintype "passive"))
      (node (ref "S1") (pin "8") (pinfunction "SGND_8") (pintype "passive"))
      (node (ref "S2") (pin "1") (pinfunction "PGND_1") (pintype "passive"))
      (node (ref "S2") (pin "19") (pinfunction "PGND_19") (pintype "passive"))
      (node (ref "S2") (pin "2") (pinfunction "PGND_2") (pintype "passive"))
      (node (ref "S2") (pin "20") (pinfunction "PGND_20") (pintype "passive"))
      (node (ref "S2") (pin "21") (pinfunction "SGND_21") (pintype "passive"))
      (node (ref "S2") (pin "8") (pinfunction "SGND_8") (pintype "passive"))
      (node (ref "S3") (pin "1") (pinfunction "PGND_1") (pintype "passive"))
      (node (ref "S3") (pin "19") (pinfunction "PGND_19") (pintype "passive"))
      (node (ref "S3") (pin "2") (pinfunction "PGND_2") (pintype "passive"))
      (node (ref "S3") (pin "20") (pinfunction "PGND_20") (pintype "passive"))
      (node (ref "S3") (pin "21") (pinfunction "SGND_21") (pintype "passive"))
      (node (ref "S3") (pin "8") (pinfunction "SGND_8") (pintype "passive"))
      (node (ref "S4") (pin "1") (pinfunction "PGND_1") (pintype "passive"))
      (node (ref "S4") (pin "19") (pinfunction "PGND_19") (pintype "passive"))
      (node (ref "S4") (pin "2") (pinfunction "PGND_2") (pintype "passive"))
      (node (ref "S4") (pin "20") (pinfunction "PGND_20") (pintype "passive"))
      (node (ref "S4") (pin "21") (pinfunction "SGND_21") (pintype "passive"))
      (node (ref "S4") (pin "8") (pinfunction "SGND_8") (pintype "passive"))
      (node (ref "ShiftLED2") (pin "2") (pinfunction "GND_2") (pintype "passive"))
      (node (ref "T1") (pin "1") (pinfunction "G_1") (pintype "passive"))
      (node (ref "T2") (pin "1") (pinfunction "G_1") (pintype "passive"))
      (node (ref "T3") (pin "1") (pinfunction "G_1") (pintype "passive"))
      (node (ref "TVS-1") (pin "1") (pinfunction "A_1") (pintype "passive"))
      (node (ref "TVS-1") (pin "2") (pinfunction "A_2") (pintype "passive"))
      (node (ref "TVS-1") (pin "3") (pinfunction "A_3") (pintype "passive"))
      (node (ref "TVS-1") (pin "4") (pinfunction "A_4") (pintype "passive"))
      (node (ref "TVS-1") (pin "5") (pinfunction "A_5") (pintype "passive"))
      (node (ref "TVS-1") (pin "6") (pinfunction "A_6") (pintype "passive"))
      (node (ref "TVS-1") (pin "7") (pinfunction "A_7") (pintype "passive"))
      (node (ref "TVS-1") (pin "8") (pinfunction "A_8") (pintype "passive"))
      (node (ref "TVS-2") (pin "1") (pinfunction "A_1") (pintype "passive"))
      (node (ref "TVS-2") (pin "2") (pinfunction "A_2") (pintype "passive"))
      (node (ref "TVS-2") (pin "3") (pinfunction "A_3") (pintype "passive"))
      (node (ref "TVS-2") (pin "4") (pinfunction "A_4") (pintype "passive"))
      (node (ref "TVS-2") (pin "5") (pinfunction "A_5") (pintype "passive"))
      (node (ref "TVS-2") (pin "6") (pinfunction "A_6") (pintype "passive"))
      (node (ref "TVS-2") (pin "7") (pinfunction "A_7") (pintype "passive"))
      (node (ref "TVS-2") (pin "8") (pinfunction "A_8") (pintype "passive"))
      (node (ref "TVS-3V3-1") (pin "1") (pinfunction "A_1") (pintype "passive"))
      (node (ref "TVS-3V3-1") (pin "2") (pinfunction "A_2") (pintype "passive"))
      (node (ref "TVS-3V3-1") (pin "3") (pinfunction "A_3") (pintype "passive"))
      (node (ref "TVS-3V3-1") (pin "4") (pinfunction "A_4") (pintype "passive"))
      (node (ref "TVS-3V3-1") (pin "5") (pinfunction "A_5") (pintype "passive"))
      (node (ref "TVS-3V3-1") (pin "6") (pinfunction "A_6") (pintype "passive"))
      (node (ref "TVS-3V3-1") (pin "7") (pinfunction "A_7") (pintype "passive"))
      (node (ref "TVS-3V3-1") (pin "8") (pinfunction "A_8") (pintype "passive"))
      (node (ref "TVS-3V3-2") (pin "1") (pinfunction "A_1") (pintype "passive"))
      (node (ref "TVS-3V3-2") (pin "2") (pinfunction "A_2") (pintype "passive"))
      (node (ref "TVS-3V3-2") (pin "3") (pinfunction "A_3") (pintype "passive"))
      (node (ref "TVS-3V3-2") (pin "4") (pinfunction "A_4") (pintype "passive"))
      (node (ref "TVS-3V3-2") (pin "5") (pinfunction "A_5") (pintype "passive"))
      (node (ref "TVS-3V3-2") (pin "6") (pinfunction "A_6") (pintype "passive"))
      (node (ref "TVS-3V3-2") (pin "7") (pinfunction "A_7") (pintype "passive"))
      (node (ref "TVS-3V3-2") (pin "8") (pinfunction "A_8") (pintype "passive"))
      (node (ref "TVS-3V3-3") (pin "1") (pinfunction "A_1") (pintype "passive"))
      (node (ref "TVS-3V3-3") (pin "2") (pinfunction "A_2") (pintype "passive"))
      (node (ref "TVS-3V3-3") (pin "3") (pinfunction "A_3") (pintype "passive"))
      (node (ref "TVS-3V3-3") (pin "4") (pinfunction "A_4") (pintype "passive"))
      (node (ref "TVS-3V3-3") (pin "5") (pinfunction "A_5") (pintype "passive"))
      (node (ref "TVS-3V3-3") (pin "6") (pinfunction "A_6") (pintype "passive"))
      (node (ref "TVS-3V3-3") (pin "7") (pinfunction "A_7") (pintype "passive"))
      (node (ref "TVS-3V3-3") (pin "8") (pinfunction "A_8") (pintype "passive"))
      (node (ref "TVS-3V3-4") (pin "1") (pinfunction "A_1") (pintype "passive"))
      (node (ref "TVS-3V3-4") (pin "2") (pinfunction "A_2") (pintype "passive"))
      (node (ref "TVS-3V3-4") (pin "3") (pinfunction "A_3") (pintype "passive"))
      (node (ref "TVS-3V3-4") (pin "4") (pinfunction "A_4") (pintype "passive"))
      (node (ref "TVS-3V3-4") (pin "5") (pinfunction "A_5") (pintype "passive"))
      (node (ref "TVS-3V3-4") (pin "6") (pinfunction "A_6") (pintype "passive"))
      (node (ref "TVS-3V3-4") (pin "7") (pinfunction "A_7") (pintype "passive"))
      (node (ref "TVS-3V3-4") (pin "8") (pinfunction "A_8") (pintype "passive"))
      (node (ref "Timer1") (pin "1") (pinfunction "GND_1") (pintype "passive"))
      (node (ref "VReg1") (pin "4") (pinfunction "GND_4") (pintype "passive"))
      (node (ref "VReg2") (pin "4") (pinfunction "GND_4") (pintype "passive"))
      (node (ref "VReg3") (pin "2") (pinfunction "GND_2") (pintype "passive"))
      (node (ref "VReg5_2") (pin "2") (pinfunction "GND_2") (pintype "passive"))
      (node (ref "WD1") (pin "2") (pinfunction "GND_2") (pintype "passive"))
    )
    (net (code "206") (name "MOSI0") (class "Default")
      (node (ref "DAC-1") (pin "15") (pinfunction "DIN_15") (pintype "passive"))
      (node (ref "H3") (pin "20") (pinfunction "20_20") (pintype "passive"))
      (node (ref "H4") (pin "20") (pinfunction "20_20") (pintype "passive"))
      (node (ref "MCU1") (pin "12") (pinfunction "11_12") (pintype "passive"))
    )
    (net (code "207") (name "Net-(ADC-REF)") (class "Default")
      (node (ref "ADC") (pin "10") (pinfunction "REF_10") (pintype "passive"))
      (node (ref "R3-3") (pin "1") (pinfunction "1_1") (pintype "passive"))
      (node (ref "R4-4") (pin "2") (pinfunction "2_2") (pintype "passive"))
    )
    (net (code "208") (name "Net-(Camera1-EO1)") (class "Default")
      (node (ref "Camera1") (pin "10") (pinfunction "EO1_10") (pintype "passive"))
      (node (ref "F7") (pin "1") (pinfunction "1_1") (pintype "passive"))
    )
    (net (code "209") (name "Net-(Camera1-EO2)") (class "Default")
      (node (ref "Camera1") (pin "8") (pinfunction "EO2_8") (pintype "passive"))
      (node (ref "F5") (pin "1") (pinfunction "1_1") (pintype "passive"))
    )
    (net (code "210") (name "Net-(Camera1-EO3)") (class "Default")
      (node (ref "Camera1") (pin "6") (pinfunction "EO3_6") (pintype "passive"))
      (node (ref "F3") (pin "1") (pinfunction "1_1") (pintype "passive"))
    )
    (net (code "211") (name "Net-(Camera1-EO4)") (class "Default")
      (node (ref "Camera1") (pin "5") (pinfunction "EO4_5") (pintype "passive"))
      (node (ref "F2") (pin "1") (pinfunction "1_1") (pintype "passive"))
    )
    (net (code "212") (name "Net-(Camera1-GND?-Pad1)") (class "Default")
      (node (ref "Camera1") (pin "1") (pinfunction "GND?_1") (pintype "passive"))
      (node (ref "R3-4") (pin "2") (pinfunction "2_2") (pintype "passive"))
    )
    (net (code "213") (name "Net-(Camera1-GND?-Pad3)") (class "Default")
      (node (ref "Camera1") (pin "3") (pinfunction "GND?_3") (pintype "passive"))
      (node (ref "R3-5") (pin "2") (pinfunction "2_2") (pintype "passive"))
    )
    (net (code "214") (name "Net-(Camera1-RO)") (class "Default")
      (node (ref "Camera1") (pin "7") (pinfunction "RO_7") (pintype "passive"))
      (node (ref "F4") (pin "1") (pinfunction "1_1") (pintype "passive"))
    )
    (net (code "215") (name "Net-(Camera1-Sp)") (class "Default")
      (node (ref "Camera1") (pin "9") (pinfunction "Sp_9") (pintype "passive"))
      (node (ref "F6") (pin "1") (pinfunction "1_1") (pintype "passive"))
    )
    (net (code "216") (name "Net-(Camera1-TrI)") (class "Default")
      (node (ref "Camera1") (pin "11") (pinfunction "TrI_11") (pintype "passive"))
      (node (ref "F8") (pin "1") (pinfunction "1_1") (pintype "passive"))
    )
    (net (code "217") (name "Net-(Camera1-TrO)") (class "Default")
      (node (ref "Camera1") (pin "4") (pinfunction "TrO_4") (pintype "passive"))
      (node (ref "F1") (pin "1") (pinfunction "1_1") (pintype "passive"))
    )
    (net (code "218") (name "Net-(Cnt1-Div10)") (class "Default")
      (node (ref "Cnt1") (pin "12") (pinfunction "Div10_12") (pintype "passive"))
      (node (ref "Cnt2") (pin "14") (pinfunction "CLK_14") (pintype "passive"))
    )
    (net (code "219") (name "Net-(Cnt2-Div10)") (class "Default")
      (node (ref "Cnt2") (pin "12") (pinfunction "Div10_12") (pintype "passive"))
      (node (ref "Cnt3") (pin "14") (pinfunction "CLK_14") (pintype "passive"))
    )
    (net (code "220") (name "Net-(DAC-1-VREF)") (class "Default")
      (node (ref "C1-10") (pin "1") (pinfunction "1_1") (pintype "passive"))
      (node (ref "DAC-1") (pin "8") (pinfunction "VREF_8") (pintype "passive"))
      (node (ref "R5-9") (pin "2") (pinfunction "2_2") (pintype "passive"))
    )
    (net (code "221") (name "Net-(DIR_13=OUT-Pad1)") (class "Default")
      (node (ref "DIR_13=OUT") (pin "1") (pinfunction "1_1") (pintype "passive"))
      (node (ref "R6-1") (pin "1") (pinfunction "1_1") (pintype "passive"))
    )
    (net (code "222") (name "Net-(DIR_25=OUT-Pad1)") (class "Default")
      (node (ref "DIR_25=OUT") (pin "1") (pinfunction "1_1") (pintype "passive"))
      (node (ref "R6-2") (pin "1") (pinfunction "1_1") (pintype "passive"))
    )
    (net (code "223") (name "Net-(DIR_26=OUT-Pad1)") (class "Default")
      (node (ref "DIR_26=OUT") (pin "1") (pinfunction "1_1") (pintype "passive"))
      (node (ref "R6-3") (pin "1") (pinfunction "1_1") (pintype "passive"))
    )
    (net (code "224") (name "Net-(DIR_27=OUT-Pad1)") (class "Default")
      (node (ref "DIR_27=OUT") (pin "1") (pinfunction "1_1") (pintype "passive"))
      (node (ref "R6-4") (pin "1") (pinfunction "1_1") (pintype "passive"))
    )
    (net (code "225") (name "Net-(DIR_28=OUT-Pad1)") (class "Default")
      (node (ref "DIR_28=OUT") (pin "1") (pinfunction "1_1") (pintype "passive"))
      (node (ref "R6-5") (pin "1") (pinfunction "1_1") (pintype "passive"))
    )
    (net (code "226") (name "Net-(DIR_31=OUT-Pad1)") (class "Default")
      (node (ref "DIR_31=OUT") (pin "1") (pinfunction "1_1") (pintype "passive"))
      (node (ref "R6-6") (pin "1") (pinfunction "1_1") (pintype "passive"))
    )
    (net (code "227") (name "Net-(DIR_32=OUT-Pad1)") (class "Default")
      (node (ref "DIR_32=OUT") (pin "1") (pinfunction "1_1") (pintype "passive"))
      (node (ref "R6-7") (pin "1") (pinfunction "1_1") (pintype "passive"))
    )
    (net (code "228") (name "Net-(DL-1-Cbar)") (class "Default")
      (node (ref "DL-1") (pin "6") (pinfunction "Cbar_6") (pintype "passive"))
      (node (ref "R1-30") (pin "2") (pinfunction "2_2") (pintype "passive"))
      (node (ref "WD1") (pin "1") (pinfunction "WDO_1") (pintype "passive"))
    )
    (net (code "229") (name "Net-(J1-2-Pad2)") (class "Default")
      (node (ref "J1-2") (pin "2") (pinfunction "2_2") (pintype "passive"))
      (node (ref "R1-8") (pin "2") (pinfunction "2_2") (pintype "passive"))
    )
    (net (code "230") (name "Net-(J1-3-Pad2)") (class "Default")
      (node (ref "J1-3") (pin "2") (pinfunction "2_2") (pintype "passive"))
      (node (ref "R1-10") (pin "2") (pinfunction "2_2") (pintype "passive"))
    )
    (net (code "231") (name "Net-(J1-4-Pad2)") (class "Default")
      (node (ref "J1-4") (pin "2") (pinfunction "2_2") (pintype "passive"))
      (node (ref "R1-12") (pin "2") (pinfunction "2_2") (pintype "passive"))
    )
    (net (code "232") (name "Net-(LED1-8-Pad1)") (class "Default")
      (node (ref "LED1-8") (pin "1") (pinfunction "1_1") (pintype "passive"))
      (node (ref "R6-8") (pin "1") (pinfunction "1_1") (pintype "passive"))
    )
    (net (code "233") (name "Net-(LED1-9-Pad1)") (class "Default")
      (node (ref "LED1-9") (pin "1") (pinfunction "1_1") (pintype "passive"))
      (node (ref "R6-9") (pin "1") (pinfunction "1_1") (pintype "passive"))
    )
    (net (code "234") (name "Net-(LED1-10-Pad1)") (class "Default")
      (node (ref "LED1-10") (pin "1") (pinfunction "1_1") (pintype "passive"))
      (node (ref "R6-10") (pin "1") (pinfunction "1_1") (pintype "passive"))
    )
    (net (code "235") (name "Net-(LED1-11-Pad1)") (class "Default")
      (node (ref "LED1-11") (pin "1") (pinfunction "1_1") (pintype "passive"))
      (node (ref "R6-11") (pin "1") (pinfunction "1_1") (pintype "passive"))
    )
    (net (code "236") (name "Net-(LED1-12-Pad1)") (class "Default")
      (node (ref "LED1-12") (pin "1") (pinfunction "1_1") (pintype "passive"))
      (node (ref "R6-12") (pin "1") (pinfunction "1_1") (pintype "passive"))
    )
    (net (code "237") (name "Net-(LED1-13-Pad1)") (class "Default")
      (node (ref "LED1-13") (pin "1") (pinfunction "1_1") (pintype "passive"))
      (node (ref "R6-13") (pin "1") (pinfunction "1_1") (pintype "passive"))
    )
    (net (code "238") (name "Net-(LED1-13-Pad2)") (class "Default")
      (node (ref "LED1-13") (pin "2") (pinfunction "2_2") (pintype "passive"))
      (node (ref "MCU1") (pin "45") (pinfunction "3V3_45") (pintype "passive"))
      (node (ref "R4-5") (pin "2") (pinfunction "2_2") (pintype "passive"))
    )
    (net (code "239") (name "Net-(LED1-14-Pad1)") (class "Default")
      (node (ref "LED1-14") (pin "1") (pinfunction "1_1") (pintype "passive"))
      (node (ref "R6-14") (pin "1") (pinfunction "1_1") (pintype "passive"))
    )
    (net (code "240") (name "Net-(LVL_GPIO13-B)") (class "Default")
      (node (ref "J1-5B") (pin "1") (pinfunction "1_1") (pintype "passive"))
      (node (ref "LVL_GPIO13") (pin "4") (pinfunction "B_4") (pintype "passive"))
    )
    (net (code "241") (name "Net-(LVL_GPIO13-VCCB)") (class "Default")
      (node (ref "C1-18") (pin "2") (pinfunction "2_2") (pintype "passive"))
      (node (ref "J1-5") (pin "2") (pinfunction "2_2") (pintype "passive"))
      (node (ref "LVL_GPIO13") (pin "6") (pinfunction "VCCB_6") (pintype "passive"))
    )
    (net (code "242") (name "Net-(LVL_GPIO25-B)") (class "Default")
      (node (ref "J1-6B") (pin "1") (pinfunction "1_1") (pintype "passive"))
      (node (ref "LVL_GPIO25") (pin "4") (pinfunction "B_4") (pintype "passive"))
    )
    (net (code "243") (name "Net-(LVL_GPIO25-VCCB)") (class "Default")
      (node (ref "C1-19") (pin "2") (pinfunction "2_2") (pintype "passive"))
      (node (ref "J1-6") (pin "2") (pinfunction "2_2") (pintype "passive"))
      (node (ref "LVL_GPIO25") (pin "6") (pinfunction "VCCB_6") (pintype "passive"))
    )
    (net (code "244") (name "Net-(LVL_GPIO26-B)") (class "Default")
      (node (ref "J1-7B") (pin "1") (pinfunction "1_1") (pintype "passive"))
      (node (ref "LVL_GPIO26") (pin "4") (pinfunction "B_4") (pintype "passive"))
    )
    (net (code "245") (name "Net-(LVL_GPIO26-VCCB)") (class "Default")
      (node (ref "C1-20") (pin "2") (pinfunction "2_2") (pintype "passive"))
      (node (ref "J1-7") (pin "2") (pinfunction "2_2") (pintype "passive"))
      (node (ref "LVL_GPIO26") (pin "6") (pinfunction "VCCB_6") (pintype "passive"))
    )
    (net (code "246") (name "Net-(LVL_GPIO27-B)") (class "Default")
      (node (ref "J1-8B") (pin "1") (pinfunction "1_1") (pintype "passive"))
      (node (ref "LVL_GPIO27") (pin "4") (pinfunction "B_4") (pintype "passive"))
    )
    (net (code "247") (name "Net-(LVL_GPIO27-VCCB)") (class "Default")
      (node (ref "C1-21") (pin "2") (pinfunction "2_2") (pintype "passive"))
      (node (ref "J1-8") (pin "2") (pinfunction "2_2") (pintype "passive"))
      (node (ref "LVL_GPIO27") (pin "6") (pinfunction "VCCB_6") (pintype "passive"))
    )
    (net (code "248") (name "Net-(LVL_GPIO28-B)") (class "Default")
      (node (ref "J1-9B") (pin "1") (pinfunction "1_1") (pintype "passive"))
      (node (ref "LVL_GPIO28") (pin "4") (pinfunction "B_4") (pintype "passive"))
    )
    (net (code "249") (name "Net-(LVL_GPIO28-VCCB)") (class "Default")
      (node (ref "C1-22") (pin "2") (pinfunction "2_2") (pintype "passive"))
      (node (ref "J1-9") (pin "2") (pinfunction "2_2") (pintype "passive"))
      (node (ref "LVL_GPIO28") (pin "6") (pinfunction "VCCB_6") (pintype "passive"))
    )
    (net (code "250") (name "Net-(LVL_GPIO31-VCCB)") (class "Default")
      (node (ref "C1-23") (pin "2") (pinfunction "2_2") (pintype "passive"))
      (node (ref "J1-10") (pin "2") (pinfunction "2_2") (pintype "passive"))
      (node (ref "LVL_GPIO31") (pin "6") (pinfunction "VCCB_6") (pintype "passive"))
    )
    (net (code "251") (name "Net-(LVL_GPIO32-VCCB)") (class "Default")
      (node (ref "C1-24") (pin "2") (pinfunction "2_2") (pintype "passive"))
      (node (ref "J1-11") (pin "2") (pinfunction "2_2") (pintype "passive"))
      (node (ref "LVL_GPIO32") (pin "6") (pinfunction "VCCB_6") (pintype "passive"))
    )
    (net (code "252") (name "Net-(LvL-1-DIR)") (class "Default")
      (node (ref "LvL-1") (pin "2") (pinfunction "DIR_2") (pintype "passive"))
      (node (ref "R1-8") (pin "1") (pinfunction "1_1") (pintype "passive"))
    )
    (net (code "253") (name "Net-(LvL-2-DIR)") (class "Default")
      (node (ref "LvL-2") (pin "2") (pinfunction "DIR_2") (pintype "passive"))
      (node (ref "R1-10") (pin "1") (pinfunction "1_1") (pintype "passive"))
    )
    (net (code "254") (name "Net-(LvL-3-DIR)") (class "Default")
      (node (ref "LvL-3") (pin "2") (pinfunction "DIR_2") (pintype "passive"))
      (node (ref "R1-12") (pin "1") (pinfunction "1_1") (pintype "passive"))
    )
    (net (code "255") (name "Net-(MCU1-3V3-Pad14)") (class "Default")
      (node (ref "MCU1") (pin "14") (pinfunction "3V3_14") (pintype "passive"))
      (node (ref "R4-5B") (pin "2") (pinfunction "2_2") (pintype "passive"))
    )
    (net (code "256") (name "Net-(MCU1-Vin)") (class "Default")
      (node (ref "C1-3") (pin "2") (pinfunction "2_2") (pintype "passive"))
      (node (ref "C2-2") (pin "1") (pinfunction "1_1") (pintype "passive"))
      (node (ref "MCU1") (pin "47") (pinfunction "Vin_47") (pintype "passive"))
      (node (ref "R4-3") (pin "2") (pinfunction "2_2") (pintype "passive"))
    )
    (net (code "257") (name "Net-(N1-OUT)") (class "Default")
      (node (ref "JHB") (pin "1") (pinfunction "1_1") (pintype "passive"))
      (node (ref "N1") (pin "4") (pinfunction "OUT_4") (pintype "passive"))
    )
    (net (code "258") (name "Net-(N2-OUT)") (class "Default")
      (node (ref "N2") (pin "4") (pinfunction "OUT_4") (pintype "passive"))
      (node (ref "OK") (pin "2") (pinfunction "2_2") (pintype "passive"))
    )
    (net (code "259") (name "Net-(NOT_OK-Pad1)") (class "Default")
      (node (ref "NOT_OK") (pin "1") (pinfunction "1_1") (pintype "passive"))
      (node (ref "R6-1B") (pin "1") (pinfunction "1_1") (pintype "passive"))
    )
    (net (code "260") (name "Net-(OK-Pad1)") (class "Default")
      (node (ref "OK") (pin "1") (pinfunction "1_1") (pintype "passive"))
      (node (ref "R6-2B") (pin "1") (pinfunction "1_1") (pintype "passive"))
    )
    (net (code "261") (name "Net-(PS1-Vout)") (class "Default")
      (node (ref "C3-3") (pin "1") (pinfunction "1_1") (pintype "passive"))
      (node (ref "F0") (pin "1") (pinfunction "1_1") (pintype "passive"))
      (node (ref "PS1") (pin "3") (pinfunction "Vout_3") (pintype "passive"))
    )
    (net (code "262") (name "Net-(S1-CoD)") (class "Default")
      (node (ref "R7-2") (pin "1") (pinfunction "1_1") (pintype "passive"))
      (node (ref "S1") (pin "11") (pinfunction "CoD_11") (pintype "passive"))
    )
    (net (code "263") (name "Net-(S1-ILIM)") (class "Default")
      (node (ref "R7-1") (pin "1") (pinfunction "1_1") (pintype "passive"))
      (node (ref "S1") (pin "12") (pinfunction "ILIM_12") (pintype "passive"))
    )
    (net (code "264") (name "Net-(S1-IN1)") (class "Default")
      (node (ref "R1-15") (pin "1") (pinfunction "1_1") (pintype "passive"))
      (node (ref "S1") (pin "4") (pinfunction "IN1_4") (pintype "passive"))
    )
    (net (code "265") (name "Net-(S1-IN2)") (class "Default")
      (node (ref "R1-14") (pin "1") (pinfunction "1_1") (pintype "passive"))
      (node (ref "S1") (pin "5") (pinfunction "IN2_5") (pintype "passive"))
    )
    (net (code "266") (name "Net-(S1-IN3)") (class "Default")
      (node (ref "R1-16") (pin "1") (pinfunction "1_1") (pintype "passive"))
      (node (ref "S1") (pin "6") (pinfunction "IN3_6") (pintype "passive"))
    )
    (net (code "267") (name "Net-(S1-IN4)") (class "Default")
      (node (ref "R1-17") (pin "1") (pinfunction "1_1") (pintype "passive"))
      (node (ref "S1") (pin "7") (pinfunction "IN4_7") (pintype "passive"))
    )
    (net (code "268") (name "Net-(S2-CoD)") (class "Default")
      (node (ref "R7-4") (pin "1") (pinfunction "1_1") (pintype "passive"))
      (node (ref "S2") (pin "11") (pinfunction "CoD_11") (pintype "passive"))
    )
    (net (code "269") (name "Net-(S2-ILIM)") (class "Default")
      (node (ref "R7-3") (pin "1") (pinfunction "1_1") (pintype "passive"))
      (node (ref "S2") (pin "12") (pinfunction "ILIM_12") (pintype "passive"))
    )
    (net (code "270") (name "Net-(S2-IN1)") (class "Default")
      (node (ref "R1-18") (pin "1") (pinfunction "1_1") (pintype "passive"))
      (node (ref "S2") (pin "4") (pinfunction "IN1_4") (pintype "passive"))
    )
    (net (code "271") (name "Net-(S2-IN2)") (class "Default")
      (node (ref "R1-19") (pin "1") (pinfunction "1_1") (pintype "passive"))
      (node (ref "S2") (pin "5") (pinfunction "IN2_5") (pintype "passive"))
    )
    (net (code "272") (name "Net-(S2-IN3)") (class "Default")
      (node (ref "R1-20") (pin "1") (pinfunction "1_1") (pintype "passive"))
      (node (ref "S2") (pin "6") (pinfunction "IN3_6") (pintype "passive"))
    )
    (net (code "273") (name "Net-(S2-IN4)") (class "Default")
      (node (ref "R1-21") (pin "1") (pinfunction "1_1") (pintype "passive"))
      (node (ref "S2") (pin "7") (pinfunction "IN4_7") (pintype "passive"))
    )
    (net (code "274") (name "Net-(S3-CoD)") (class "Default")
      (node (ref "R7-6") (pin "1") (pinfunction "1_1") (pintype "passive"))
      (node (ref "S3") (pin "11") (pinfunction "CoD_11") (pintype "passive"))
    )
    (net (code "275") (name "Net-(S3-ILIM)") (class "Default")
      (node (ref "R7-5") (pin "1") (pinfunction "1_1") (pintype "passive"))
      (node (ref "S3") (pin "12") (pinfunction "ILIM_12") (pintype "passive"))
    )
    (net (code "276") (name "Net-(S3-IN1)") (class "Default")
      (node (ref "R1-22") (pin "1") (pinfunction "1_1") (pintype "passive"))
      (node (ref "S3") (pin "4") (pinfunction "IN1_4") (pintype "passive"))
    )
    (net (code "277") (name "Net-(S3-IN2)") (class "Default")
      (node (ref "R1-23") (pin "1") (pinfunction "1_1") (pintype "passive"))
      (node (ref "S3") (pin "5") (pinfunction "IN2_5") (pintype "passive"))
    )
    (net (code "278") (name "Net-(S3-IN3)") (class "Default")
      (node (ref "R1-24") (pin "1") (pinfunction "1_1") (pintype "passive"))
      (node (ref "S3") (pin "6") (pinfunction "IN3_6") (pintype "passive"))
    )
    (net (code "279") (name "Net-(S3-IN4)") (class "Default")
      (node (ref "R1-25") (pin "1") (pinfunction "1_1") (pintype "passive"))
      (node (ref "S3") (pin "7") (pinfunction "IN4_7") (pintype "passive"))
    )
    (net (code "280") (name "Net-(S4-CoD)") (class "Default")
      (node (ref "R7-8") (pin "1") (pinfunction "1_1") (pintype "passive"))
      (node (ref "S4") (pin "11") (pinfunction "CoD_11") (pintype "passive"))
    )
    (net (code "281") (name "Net-(S4-ILIM)") (class "Default")
      (node (ref "R7-7") (pin "1") (pinfunction "1_1") (pintype "passive"))
      (node (ref "S4") (pin "12") (pinfunction "ILIM_12") (pintype "passive"))
    )
    (net (code "282") (name "Net-(S4-IN1)") (class "Default")
      (node (ref "R1-26") (pin "1") (pinfunction "1_1") (pintype "passive"))
      (node (ref "S4") (pin "4") (pinfunction "IN1_4") (pintype "passive"))
    )
    (net (code "283") (name "Net-(S4-IN2)") (class "Default")
      (node (ref "R1-27") (pin "1") (pinfunction "1_1") (pintype "passive"))
      (node (ref "S4") (pin "5") (pinfunction "IN2_5") (pintype "passive"))
    )
    (net (code "284") (name "Net-(S4-IN3)") (class "Default")
      (node (ref "R1-28") (pin "1") (pinfunction "1_1") (pintype "passive"))
      (node (ref "S4") (pin "6") (pinfunction "IN3_6") (pintype "passive"))
    )
    (net (code "285") (name "Net-(S4-IN4)") (class "Default")
      (node (ref "R1-29") (pin "1") (pinfunction "1_1") (pintype "passive"))
      (node (ref "S4") (pin "7") (pinfunction "IN4_7") (pintype "passive"))
    )
    (net (code "286") (name "Net-(ShiftLED1-DIR)") (class "Default")
      (node (ref "J1-24") (pin "2") (pinfunction "2_2") (pintype "passive"))
      (node (ref "ShiftLED1") (pin "1") (pinfunction "VCCA_1") (pintype "passive"))
      (node (ref "ShiftLED1") (pin "5") (pinfunction "DIR_5") (pintype "passive"))
    )
    (net (code "287") (name "Net-(Timer1-CONT)") (class "Default")
      (node (ref "C1-26") (pin "1") (pinfunction "1_1") (pintype "passive"))
      (node (ref "Timer1") (pin "5") (pinfunction "CONT_5") (pintype "passive"))
    )
    (net (code "288") (name "Net-(Timer1-DISCH)") (class "Default")
      (node (ref "R9-1") (pin "2") (pinfunction "2_2") (pintype "passive"))
      (node (ref "R9-2") (pin "1") (pinfunction "1_1") (pintype "passive"))
      (node (ref "Timer1") (pin "7") (pinfunction "DISCH_7") (pintype "passive"))
    )
    (net (code "289") (name "Net-(VReg1-BYP)") (class "Default")
      (node (ref "C4-7") (pin "2") (pinfunction "2_2") (pintype "passive"))
      (node (ref "VReg1") (pin "3") (pinfunction "BYP_3") (pintype "passive"))
    )
    (net (code "290") (name "Net-(VReg1-REF)") (class "Default")
      (node (ref "C4-6") (pin "2") (pinfunction "2_2") (pintype "passive"))
      (node (ref "VReg1") (pin "5") (pinfunction "REF_S_5") (pintype "passive"))
      (node (ref "VReg1") (pin "6") (pinfunction "REF_6") (pintype "passive"))
    )
    (net (code "291") (name "Net-(VReg1-VREG)") (class "Default")
      (node (ref "C4-1") (pin "1") (pinfunction "1_1") (pintype "passive"))
      (node (ref "C4-2") (pin "1") (pinfunction "1_1") (pintype "passive"))
      (node (ref "VReg1") (pin "1") (pinfunction "VREG_1") (pintype "passive"))
    )
    (net (code "292") (name "Net-(VReg2-BYP)") (class "Default")
      (node (ref "C4-14") (pin "2") (pinfunction "2_2") (pintype "passive"))
      (node (ref "VReg2") (pin "3") (pinfunction "BYP_3") (pintype "passive"))
    )
    (net (code "293") (name "Net-(VReg2-REF)") (class "Default")
      (node (ref "C4-13") (pin "2") (pinfunction "2_2") (pintype "passive"))
      (node (ref "VReg2") (pin "5") (pinfunction "REF_S_5") (pintype "passive"))
      (node (ref "VReg2") (pin "6") (pinfunction "REF_6") (pintype "passive"))
    )
    (net (code "294") (name "Net-(VReg2-VREG)") (class "Default")
      (node (ref "C4-8") (pin "1") (pinfunction "1_1") (pintype "passive"))
      (node (ref "C4-9") (pin "1") (pinfunction "1_1") (pintype "passive"))
      (node (ref "VReg2") (pin "1") (pinfunction "VREG_1") (pintype "passive"))
    )
    (net (code "295") (name "Net-(VReg3-Bypass)") (class "Default")
      (node (ref "C8-1") (pin "2") (pinfunction "2_2") (pintype "passive"))
      (node (ref "VReg3") (pin "4") (pinfunction "Bypass_4") (pintype "passive"))
    )
    (net (code "296") (name "Net-(VReg5_2-Bypass)") (class "Default")
      (node (ref "C8-2") (pin "2") (pinfunction "2_2") (pintype "passive"))
      (node (ref "VReg5_2") (pin "4") (pinfunction "Bypass_4") (pintype "passive"))
    )
    (net (code "297") (name "SCK0") (class "Default")
      (node (ref "DAC-1") (pin "16") (pinfunction "SCLK_16") (pintype "passive"))
      (node (ref "H3") (pin "18") (pinfunction "18_18") (pintype "passive"))
      (node (ref "H4") (pin "18") (pinfunction "18_18") (pintype "passive"))
      (node (ref "MCU1") (pin "34") (pinfunction "13_34") (pintype "passive"))
    )
    (net (code "298") (name "Vin") (class "Default")
      (node (ref "C3-2") (pin "1") (pinfunction "1_1") (pintype "passive"))
      (node (ref "C3-2B") (pin "1") (pinfunction "1_1") (pintype "passive"))
      (node (ref "CE-1") (pin "1") (pinfunction "1_1") (pintype "passive"))
      (node (ref "CE-1B") (pin "1") (pinfunction "1_1") (pintype "passive"))
      (node (ref "H3") (pin "1") (pinfunction "1_1") (pintype "passive"))
      (node (ref "H3") (pin "2") (pinfunction "2_2") (pintype "passive"))
      (node (ref "H4") (pin "1") (pinfunction "1_1") (pintype "passive"))
      (node (ref "H4") (pin "2") (pinfunction "2_2") (pintype "passive"))
      (node (ref "I1-1") (pin "2") (pinfunction "2_2") (pintype "passive"))
      (node (ref "LED1-12") (pin "2") (pinfunction "2_2") (pintype "passive"))
      (node (ref "PS1") (pin "1") (pinfunction "Vin_1") (pintype "passive"))
      (node (ref "S1") (pin "13") (pinfunction "VCC_13") (pintype "passive"))
      (node (ref "S1") (pin "18") (pinfunction "VZ_18") (pintype "passive"))
      (node (ref "S1") (pin "3") (pinfunction "VZ_3") (pintype "passive"))
      (node (ref "S2") (pin "13") (pinfunction "VCC_13") (pintype "passive"))
      (node (ref "S2") (pin "18") (pinfunction "VZ_18") (pintype "passive"))
      (node (ref "S2") (pin "3") (pinfunction "VZ_3") (pintype "passive"))
      (node (ref "S3") (pin "13") (pinfunction "VCC_13") (pintype "passive"))
      (node (ref "S3") (pin "18") (pinfunction "VZ_18") (pintype "passive"))
      (node (ref "S3") (pin "3") (pinfunction "VZ_3") (pintype "passive"))
      (node (ref "S4") (pin "13") (pinfunction "VCC_13") (pintype "passive"))
      (node (ref "S4") (pin "18") (pinfunction "VZ_18") (pintype "passive"))
      (node (ref "S4") (pin "3") (pinfunction "VZ_3") (pintype "passive"))
      (node (ref "Terminal1") (pin "1") (pinfunction "1_1") (pintype "passive"))
      (node (ref "Terminal1") (pin "11") (pinfunction "11_11") (pintype "passive"))
      (node (ref "Terminal1") (pin "13") (pinfunction "13_13") (pintype "passive"))
      (node (ref "Terminal1") (pin "15") (pinfunction "15_15") (pintype "passive"))
      (node (ref "Terminal1") (pin "17") (pinfunction "17_17") (pintype "passive"))
      (node (ref "Terminal1") (pin "19") (pinfunction "19_19") (pintype "passive"))
      (node (ref "Terminal1") (pin "21") (pinfunction "21_21") (pintype "passive"))
      (node (ref "Terminal1") (pin "23") (pinfunction "23_23") (pintype "passive"))
      (node (ref "Terminal1") (pin "25") (pinfunction "25_25") (pintype "passive"))
      (node (ref "Terminal1") (pin "27") (pinfunction "27_27") (pintype "passive"))
      (node (ref "Terminal1") (pin "29") (pinfunction "29_29") (pintype "passive"))
      (node (ref "Terminal1") (pin "3") (pinfunction "3_3") (pintype "passive"))
      (node (ref "Terminal1") (pin "31") (pinfunction "31_31") (pintype "passive"))
      (node (ref "Terminal1") (pin "5") (pinfunction "5_5") (pintype "passive"))
      (node (ref "Terminal1") (pin "7") (pinfunction "7_7") (pintype "passive"))
      (node (ref "Terminal1") (pin "9") (pinfunction "9_9") (pintype "passive"))
    )
    (net (code "299") (name "VinRaw") (class "Default")
      (node (ref "C3-1") (pin "1") (pinfunction "1_1") (pintype "passive"))
      (node (ref "I1-1") (pin "1") (pinfunction "1_1") (pintype "passive"))
      (node (ref "Jack1") (pin "1") (pinfunction "Vin_1") (pintype "passive"))
    )
    (net (code "300") (name "unconnected-(Camera1-NC-Pad2)") (class "Default")
      (node (ref "Camera1") (pin "2") (pinfunction "NC_2") (pintype "passive"))
    )
    (net (code "301") (name "unconnected-(Cnt3-Div10-Pad12)") (class "Default")
      (node (ref "Cnt3") (pin "12") (pinfunction "Div10_12") (pintype "passive"))
    )
    (net (code "302") (name "unconnected-(H1-Pad12)") (class "Default")
      (node (ref "H1") (pin "12") (pinfunction "12_12") (pintype "passive"))
    )
    (net (code "303") (name "unconnected-(H1-Pad13)") (class "Default")
      (node (ref "H1") (pin "13") (pinfunction "13_13") (pintype "passive"))
    )
    (net (code "304") (name "unconnected-(H1-Pad15)") (class "Default")
      (node (ref "H1") (pin "15") (pinfunction "15_15") (pintype "passive"))
    )
    (net (code "305") (name "unconnected-(H1-Pad17)") (class "Default")
      (node (ref "H1") (pin "17") (pinfunction "17_17") (pintype "passive"))
    )
    (net (code "306") (name "unconnected-(LvL-1-A5-Pad7)") (class "Default")
      (node (ref "LvL-1") (pin "7") (pinfunction "A5_7") (pintype "passive"))
    )
    (net (code "307") (name "unconnected-(LvL-1-A6-Pad8)") (class "Default")
      (node (ref "LvL-1") (pin "8") (pinfunction "A6_8") (pintype "passive"))
    )
    (net (code "308") (name "unconnected-(LvL-1-A7-Pad9)") (class "Default")
      (node (ref "LvL-1") (pin "9") (pinfunction "A7_9") (pintype "passive"))
    )
    (net (code "309") (name "unconnected-(LvL-1-A8-Pad10)") (class "Default")
      (node (ref "LvL-1") (pin "10") (pinfunction "A8_10") (pintype "passive"))
    )
    (net (code "310") (name "unconnected-(LvL-1-B5-Pad17)") (class "Default")
      (node (ref "LvL-1") (pin "17") (pinfunction "B5_17") (pintype "passive"))
    )
    (net (code "311") (name "unconnected-(LvL-1-B6-Pad16)") (class "Default")
      (node (ref "LvL-1") (pin "16") (pinfunction "B6_16") (pintype "passive"))
    )
    (net (code "312") (name "unconnected-(LvL-1-B7-Pad15)") (class "Default")
      (node (ref "LvL-1") (pin "15") (pinfunction "B7_15") (pintype "passive"))
    )
    (net (code "313") (name "unconnected-(LvL-1-B8-Pad14)") (class "Default")
      (node (ref "LvL-1") (pin "14") (pinfunction "B8_14") (pintype "passive"))
    )
    (net (code "314") (name "unconnected-(LvL-2-A7-Pad9)") (class "Default")
      (node (ref "LvL-2") (pin "9") (pinfunction "A7_9") (pintype "passive"))
    )
    (net (code "315") (name "unconnected-(LvL-2-A8-Pad10)") (class "Default")
      (node (ref "LvL-2") (pin "10") (pinfunction "A8_10") (pintype "passive"))
    )
    (net (code "316") (name "unconnected-(LvL-2-B7-Pad15)") (class "Default")
      (node (ref "LvL-2") (pin "15") (pinfunction "B7_15") (pintype "passive"))
    )
    (net (code "317") (name "unconnected-(LvL-2-B8-Pad14)") (class "Default")
      (node (ref "LvL-2") (pin "14") (pinfunction "B8_14") (pintype "passive"))
    )
    (net (code "318") (name "unconnected-(LvL-3-A6-Pad8)") (class "Default")
      (node (ref "LvL-3") (pin "8") (pinfunction "A6_8") (pintype "passive"))
    )
    (net (code "319") (name "unconnected-(LvL-3-A7-Pad9)") (class "Default")
      (node (ref "LvL-3") (pin "9") (pinfunction "A7_9") (pintype "passive"))
    )
    (net (code "320") (name "unconnected-(LvL-3-A8-Pad10)") (class "Default")
      (node (ref "LvL-3") (pin "10") (pinfunction "A8_10") (pintype "passive"))
    )
    (net (code "321") (name "unconnected-(LvL-3-B6-Pad16)") (class "Default")
      (node (ref "LvL-3") (pin "16") (pinfunction "B6_16") (pintype "passive"))
    )
    (net (code "322") (name "unconnected-(LvL-3-B7-Pad15)") (class "Default")
      (node (ref "LvL-3") (pin "15") (pinfunction "B7_15") (pintype "passive"))
    )
    (net (code "323") (name "unconnected-(LvL-3-B8-Pad14)") (class "Default")
      (node (ref "LvL-3") (pin "14") (pinfunction "B8_14") (pintype "passive"))
    )
    (net (code "324") (name "unconnected-(N1-NC-Pad1)") (class "Default")
      (node (ref "N1") (pin "1") (pinfunction "NC_1") (pintype "passive"))
    )
    (net (code "325") (name "unconnected-(N2-NC-Pad1)") (class "Default")
      (node (ref "N2") (pin "1") (pinfunction "NC_1") (pintype "passive"))
    )
    (net (code "326") (name "unconnected-(Ref1-DNC-Pad8)") (class "Default")
      (node (ref "Ref1") (pin "8") (pinfunction "DNC_8") (pintype "passive"))
    )
    (net (code "327") (name "unconnected-(Ref1-NIC-Pad1)") (class "Default")
      (node (ref "Ref1") (pin "1") (pinfunction "NIC_1") (pintype "passive"))
    )
    (net (code "328") (name "unconnected-(Ref1-NIC-Pad3)") (class "Default")
      (node (ref "Ref1") (pin "3") (pinfunction "NIC_3") (pintype "passive"))
    )
    (net (code "329") (name "unconnected-(Ref1-NIC-Pad5)") (class "Default")
      (node (ref "Ref1") (pin "5") (pinfunction "NIC_5") (pintype "passive"))
    )
    (net (code "330") (name "unconnected-(Ref1-NIC-Pad7)") (class "Default")
      (node (ref "Ref1") (pin "7") (pinfunction "NIC_7") (pintype "passive"))
    )
    (net (code "331") (name "unconnected-(S1-FL~{T}-Pad10)") (class "Default")
      (node (ref "S1") (pin "10") (pinfunction "FL~{T}_10") (pintype "passive"))
    )
    (net (code "332") (name "unconnected-(S1-O~{L}-Pad9)") (class "Default")
      (node (ref "S1") (pin "9") (pinfunction "O~{L}_9") (pintype "passive"))
    )
    (net (code "333") (name "unconnected-(S2-FL~{T}-Pad10)") (class "Default")
      (node (ref "S2") (pin "10") (pinfunction "FL~{T}_10") (pintype "passive"))
    )
    (net (code "334") (name "unconnected-(S2-O~{L}-Pad9)") (class "Default")
      (node (ref "S2") (pin "9") (pinfunction "O~{L}_9") (pintype "passive"))
    )
    (net (code "335") (name "unconnected-(S3-FL~{T}-Pad10)") (class "Default")
      (node (ref "S3") (pin "10") (pinfunction "FL~{T}_10") (pintype "passive"))
    )
    (net (code "336") (name "unconnected-(S3-O~{L}-Pad9)") (class "Default")
      (node (ref "S3") (pin "9") (pinfunction "O~{L}_9") (pintype "passive"))
    )
    (net (code "337") (name "unconnected-(S4-FL~{T}-Pad10)") (class "Default")
      (node (ref "S4") (pin "10") (pinfunction "FL~{T}_10") (pintype "passive"))
    )
    (net (code "338") (name "unconnected-(S4-O~{L}-Pad9)") (class "Default")
      (node (ref "S4") (pin "9") (pinfunction "O~{L}_9") (pintype "passive"))
    )
    (net (code "339") (name "unconnected-(ShiftLED1-GND-Pad2)") (class "Default")
      (node (ref "ShiftLED1") (pin "2") (pinfunction "GND_2") (pintype "passive"))
    )
    (net (code "340") (name "unconnected-(WD1-EN-Pad3)") (class "Default")
      (node (ref "WD1") (pin "3") (pinfunction "EN_3") (pintype "passive"))
    )
  )
)
